# oresat-camera-card-v0.net
KiCad netlist of a schematic drawn in EAGLE
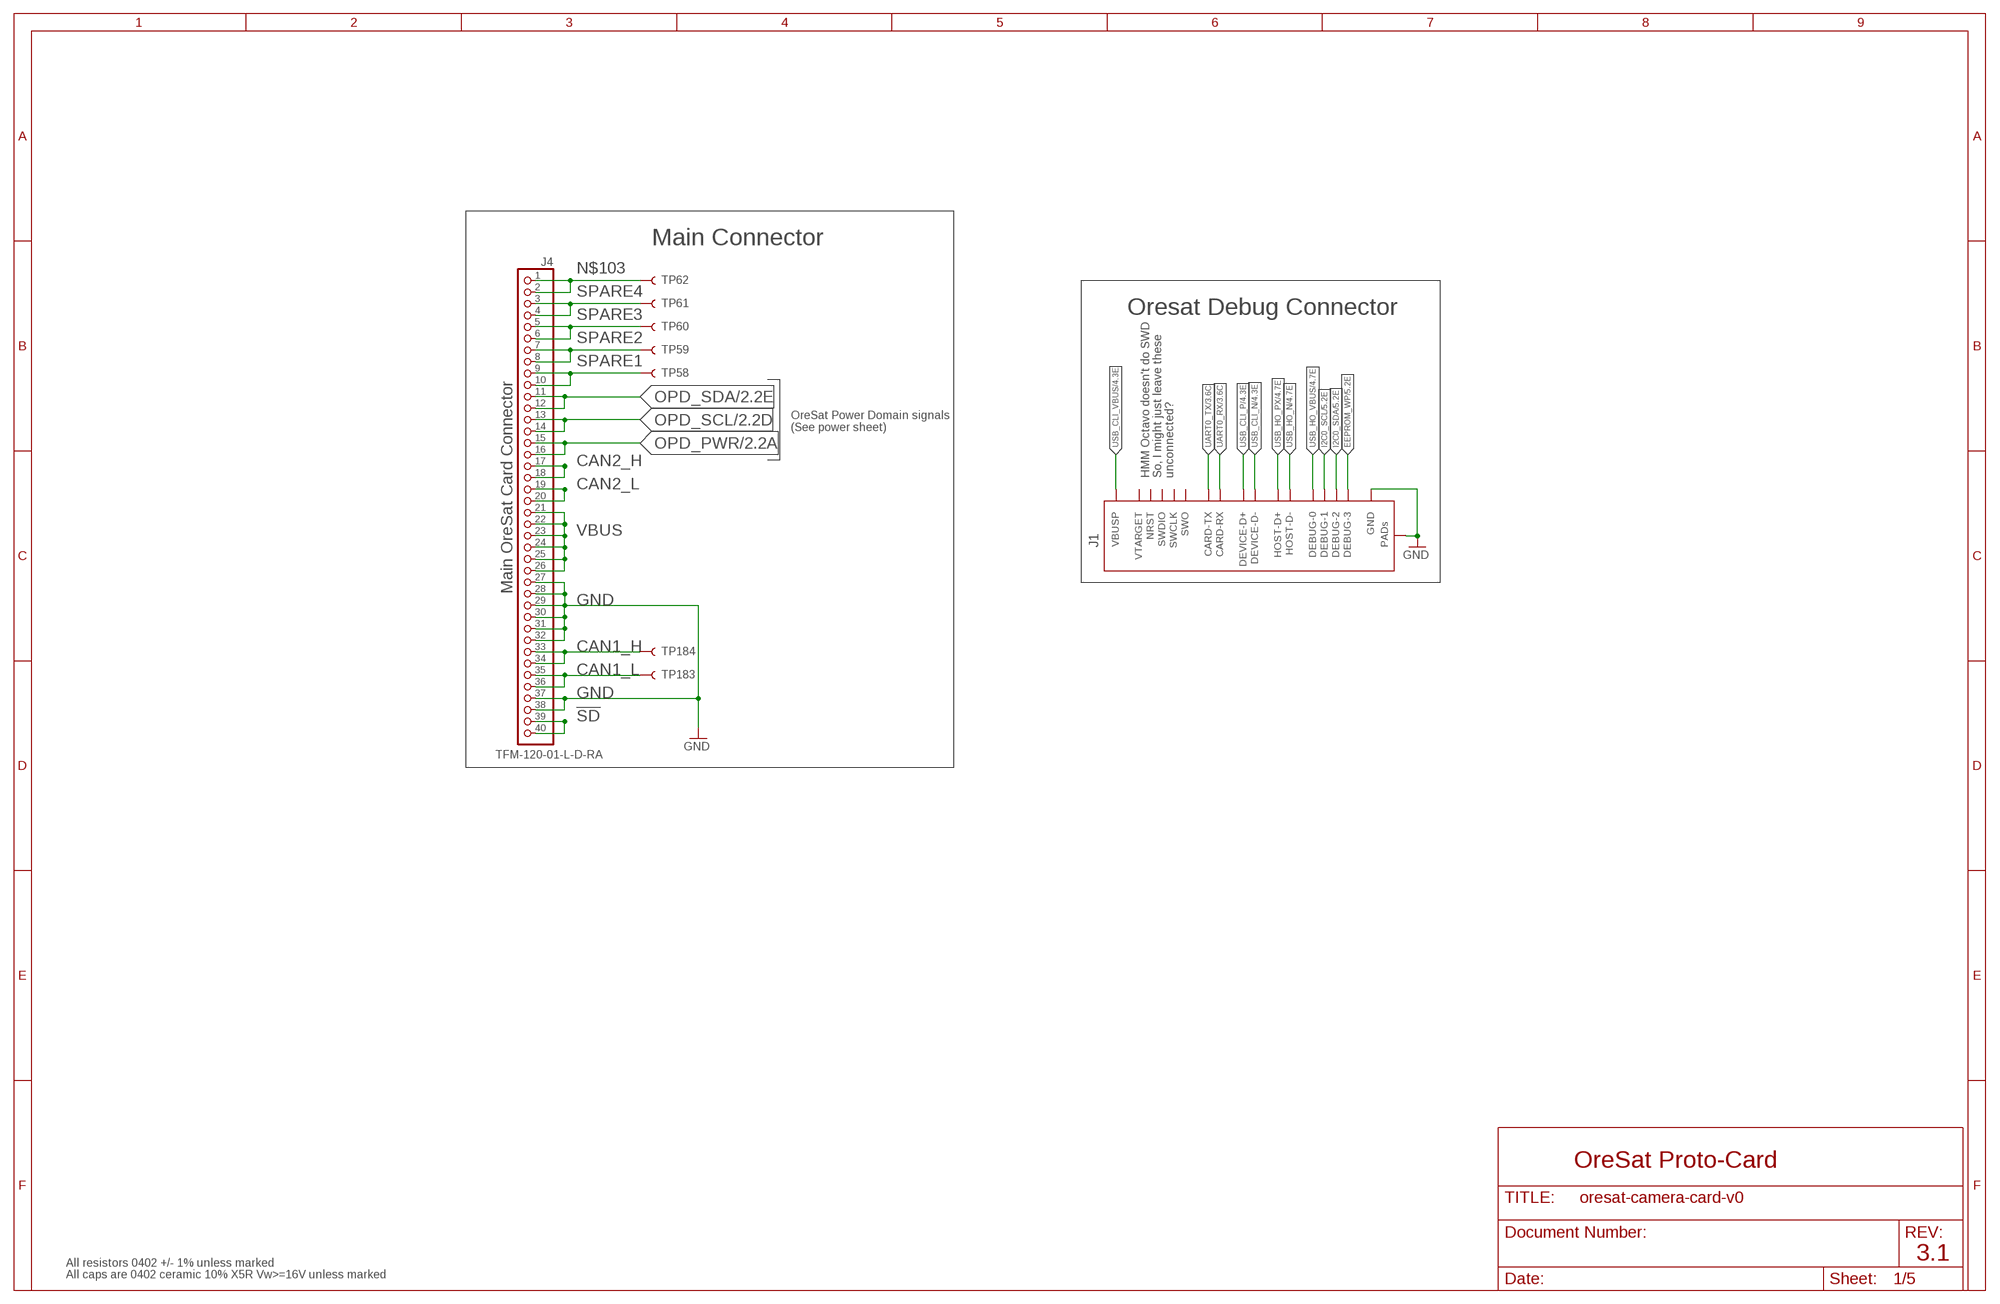
[diagram p0: schematic, sheet 1]
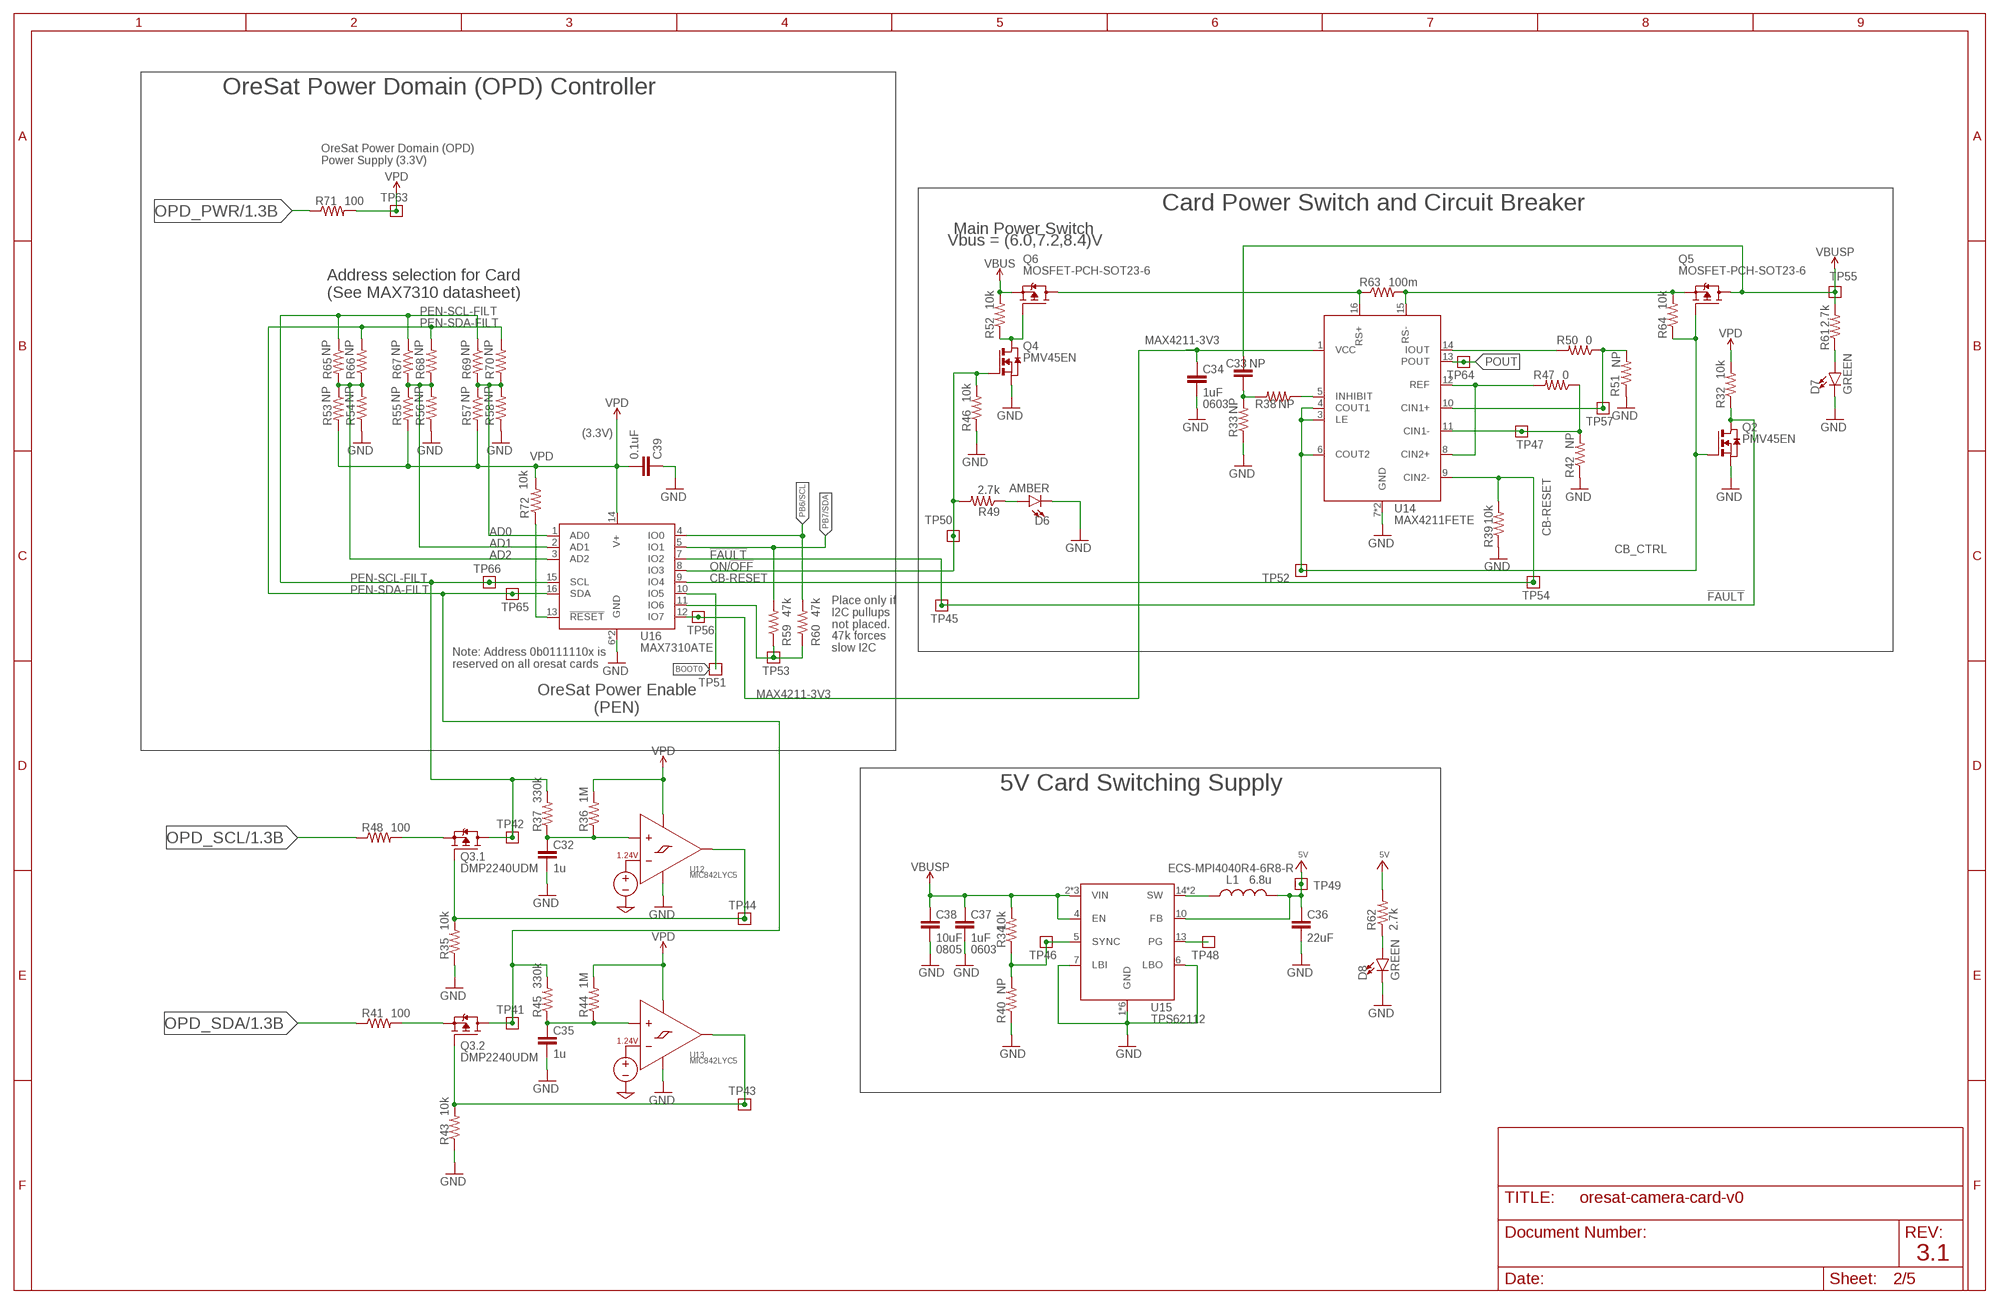
[diagram p1: schematic, sheet 2]
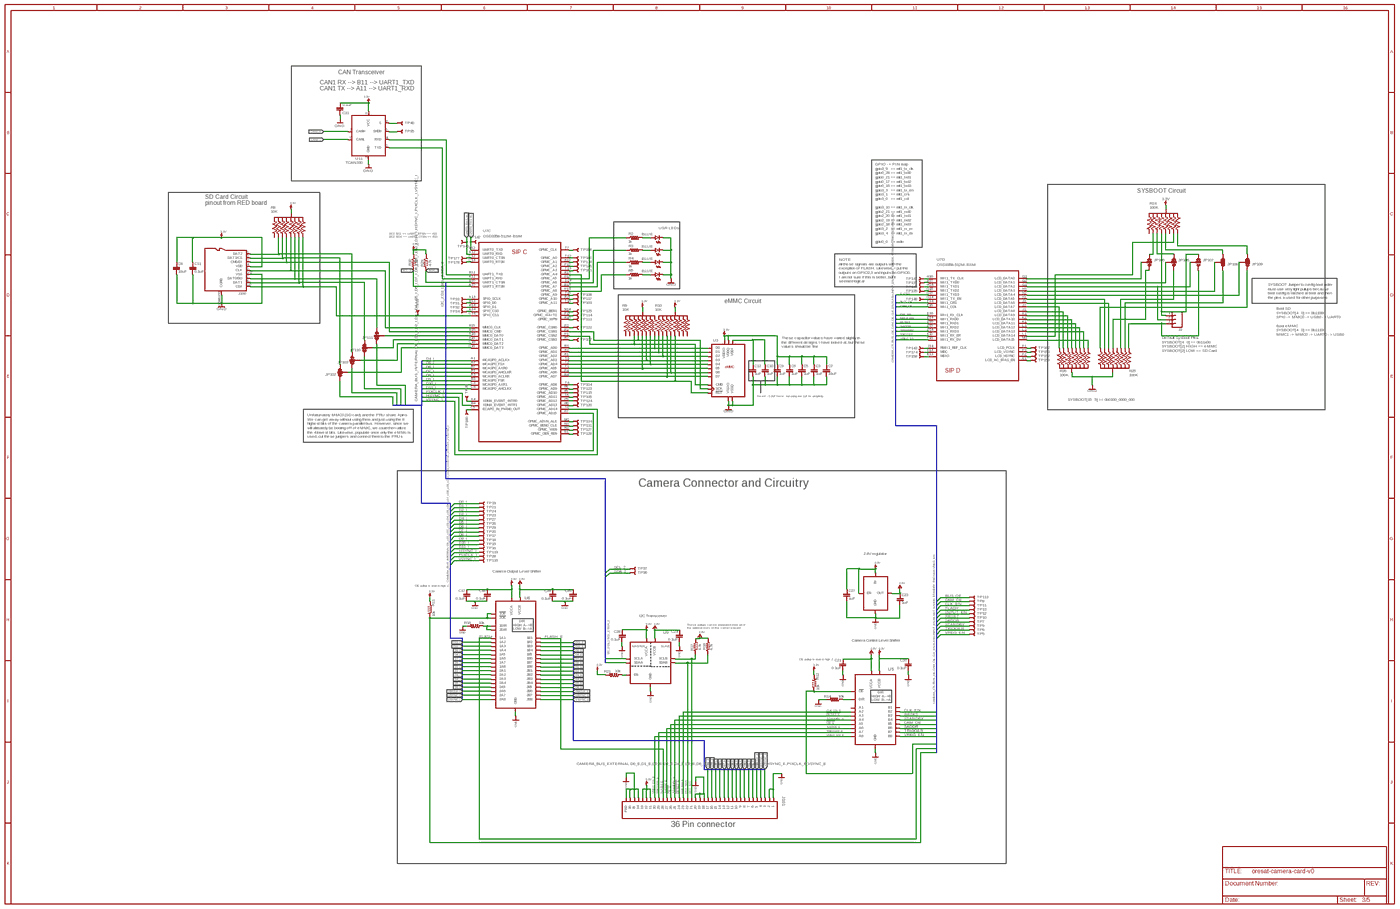
[diagram p2: schematic, sheet 3, overview]
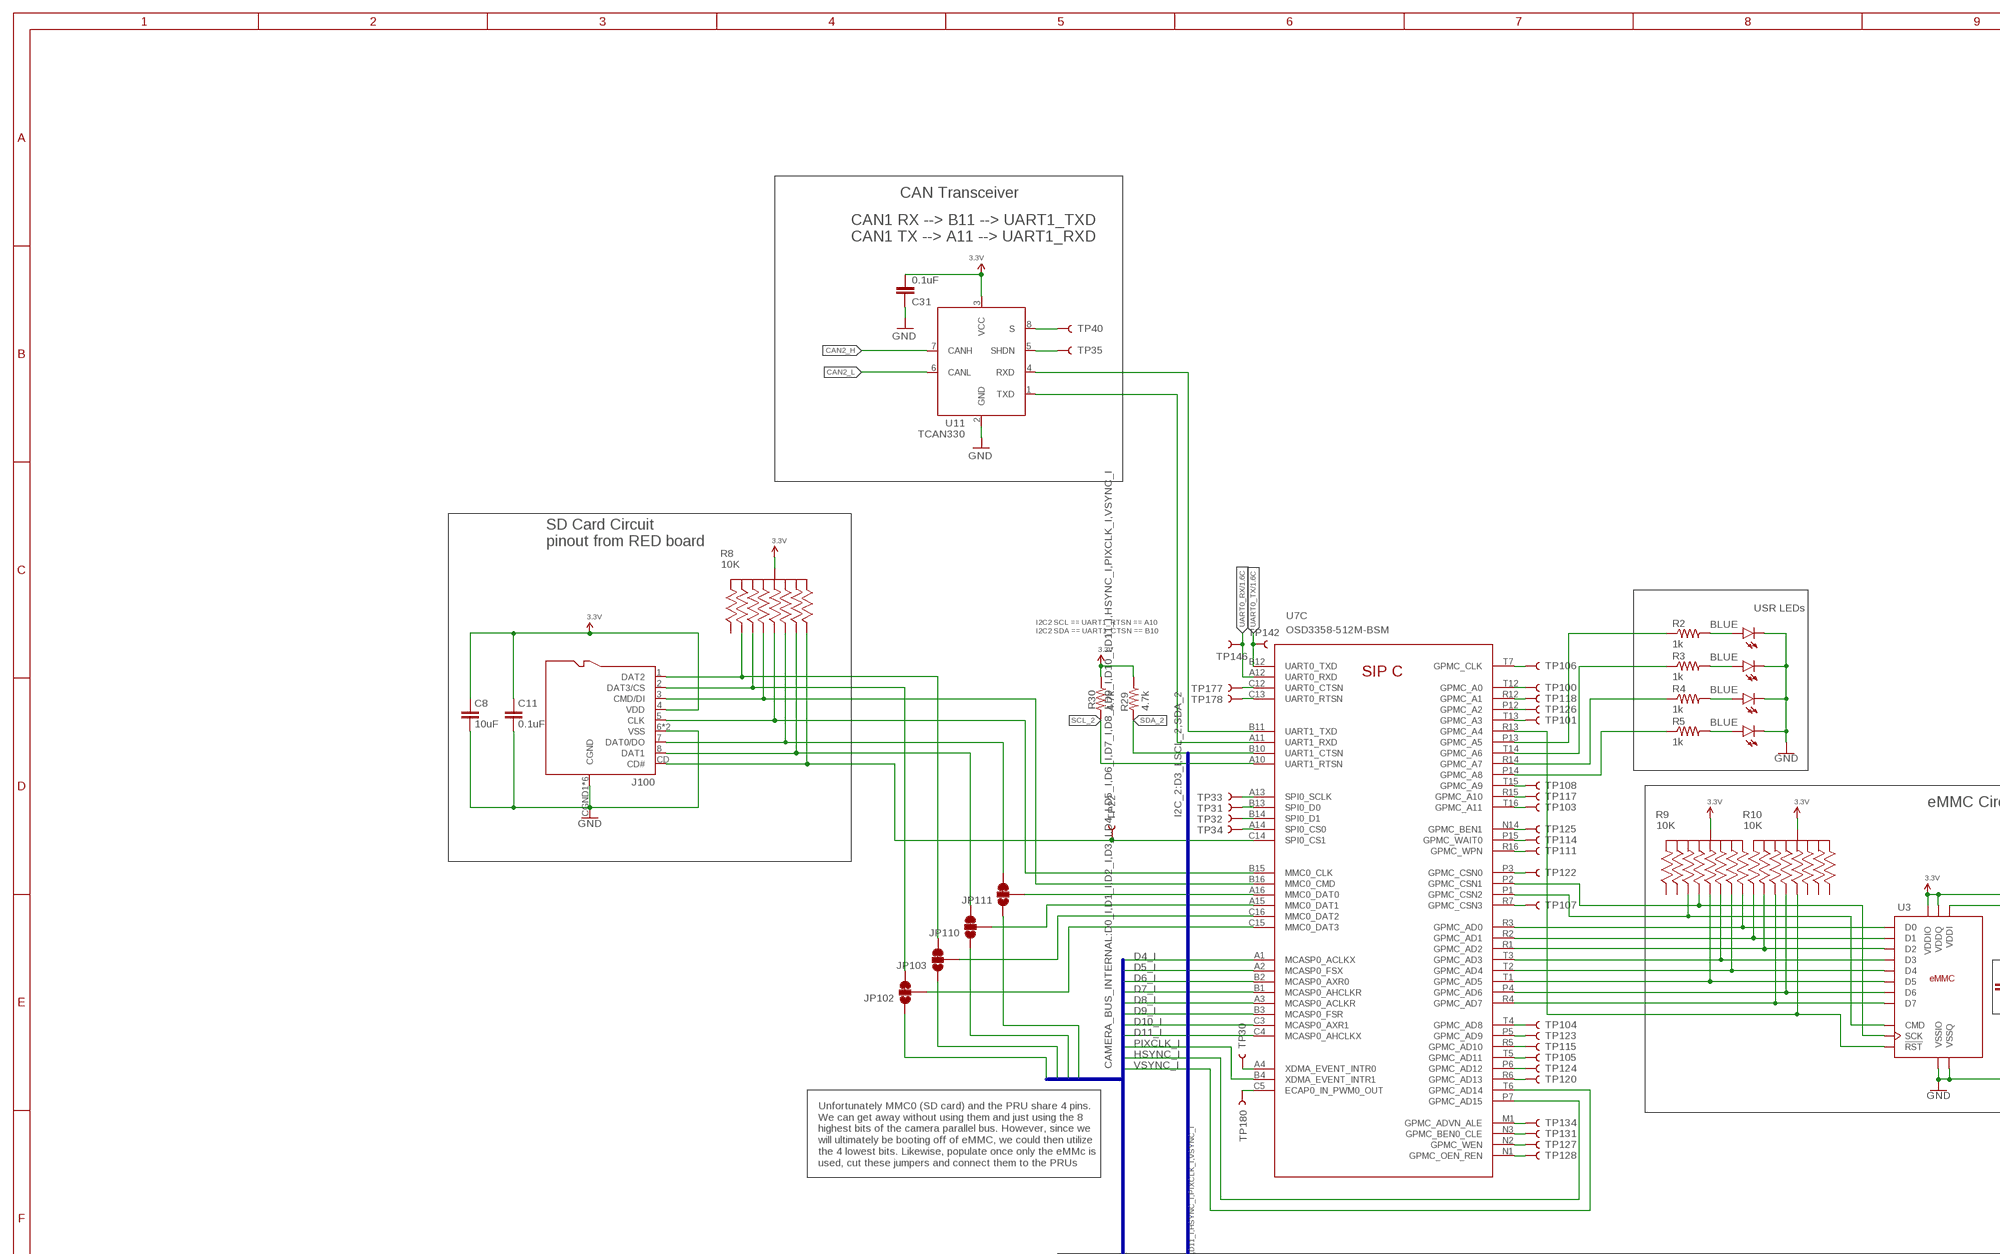
[diagram p3: schematic, sheet 3, part 1 of 4]
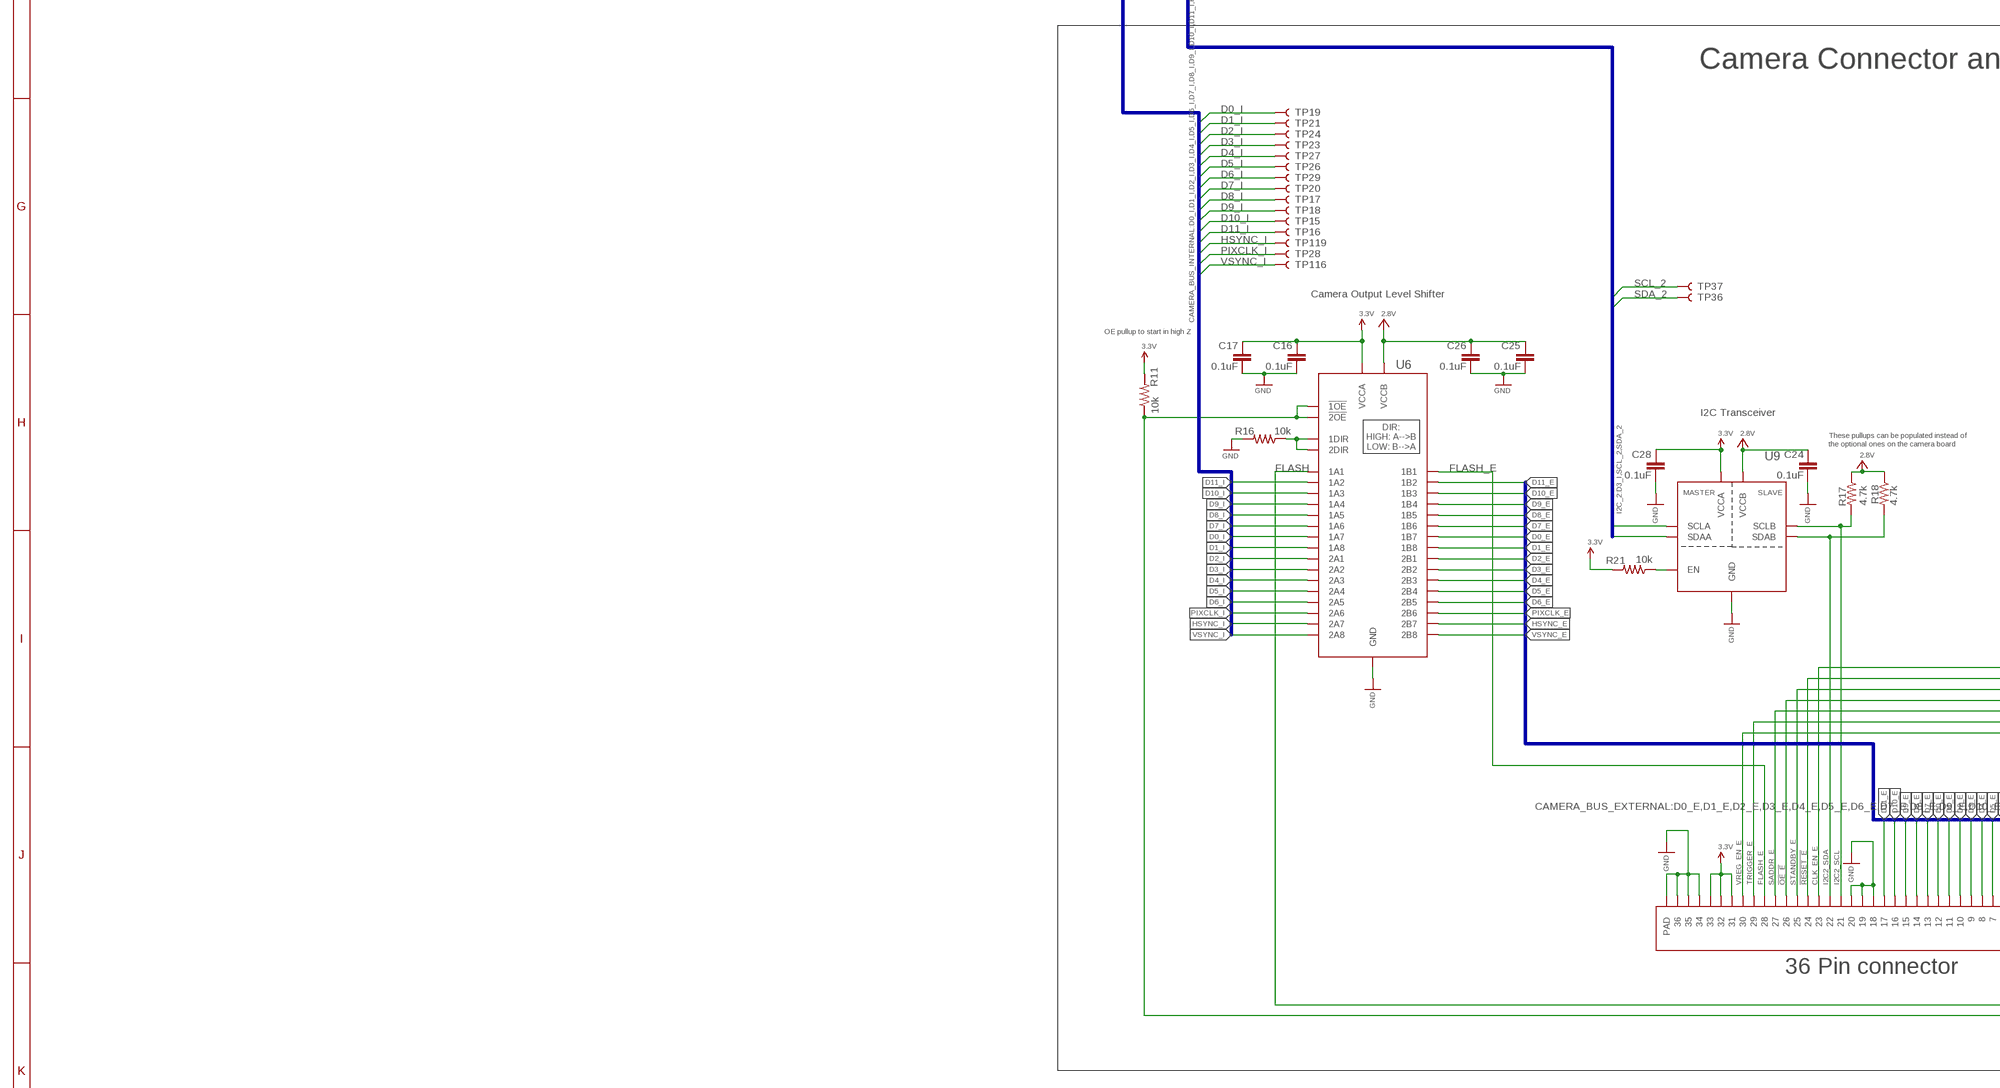
[diagram p4: schematic, sheet 3, part 2 of 4]
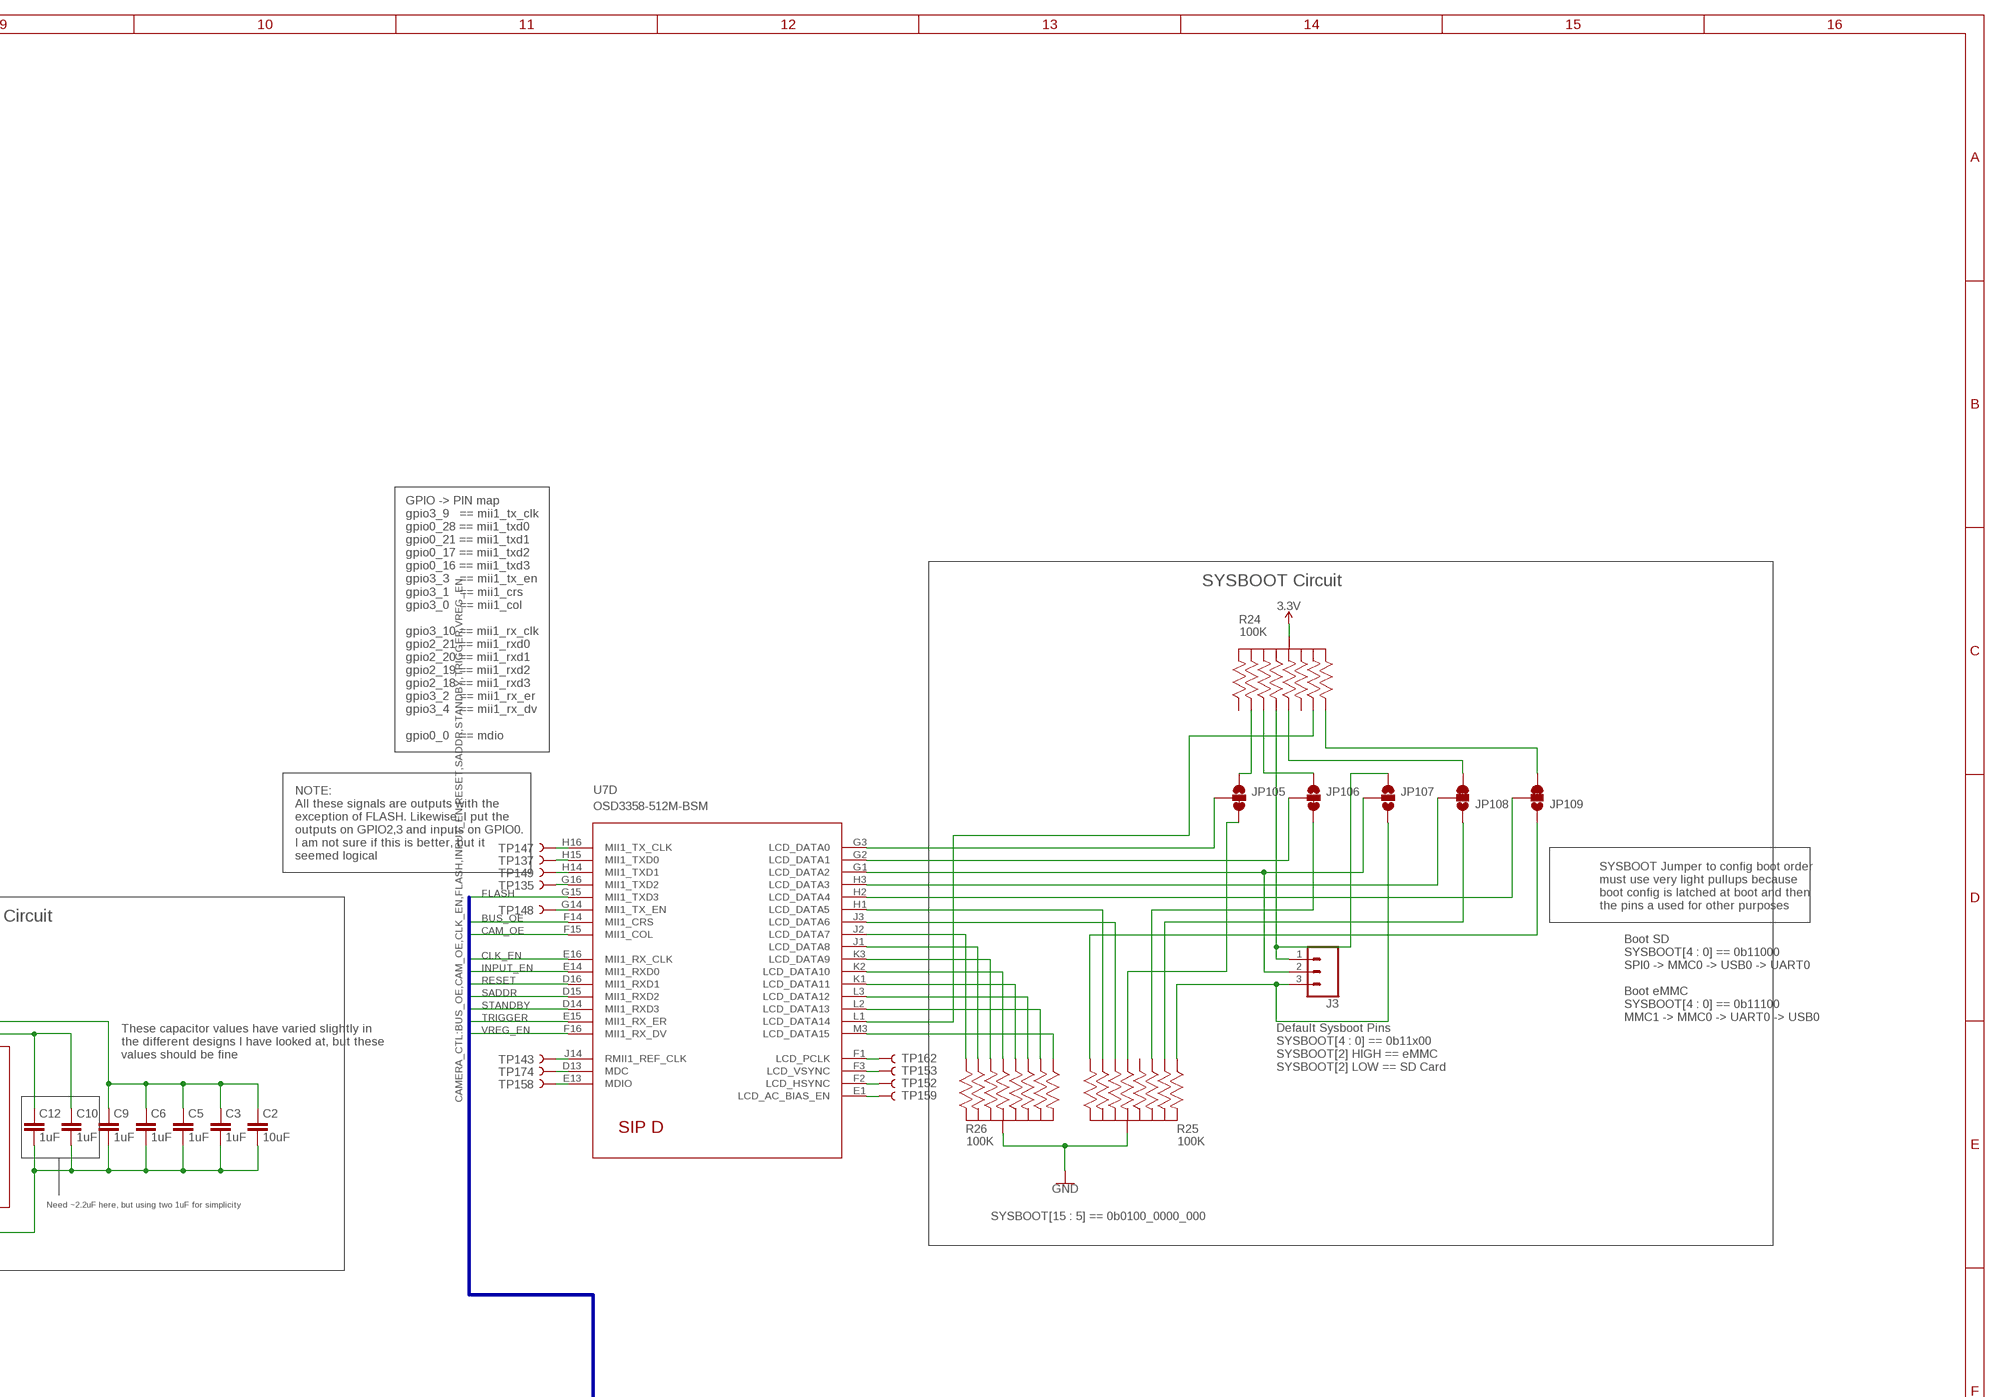
[diagram p5: schematic, sheet 3, part 3 of 4]
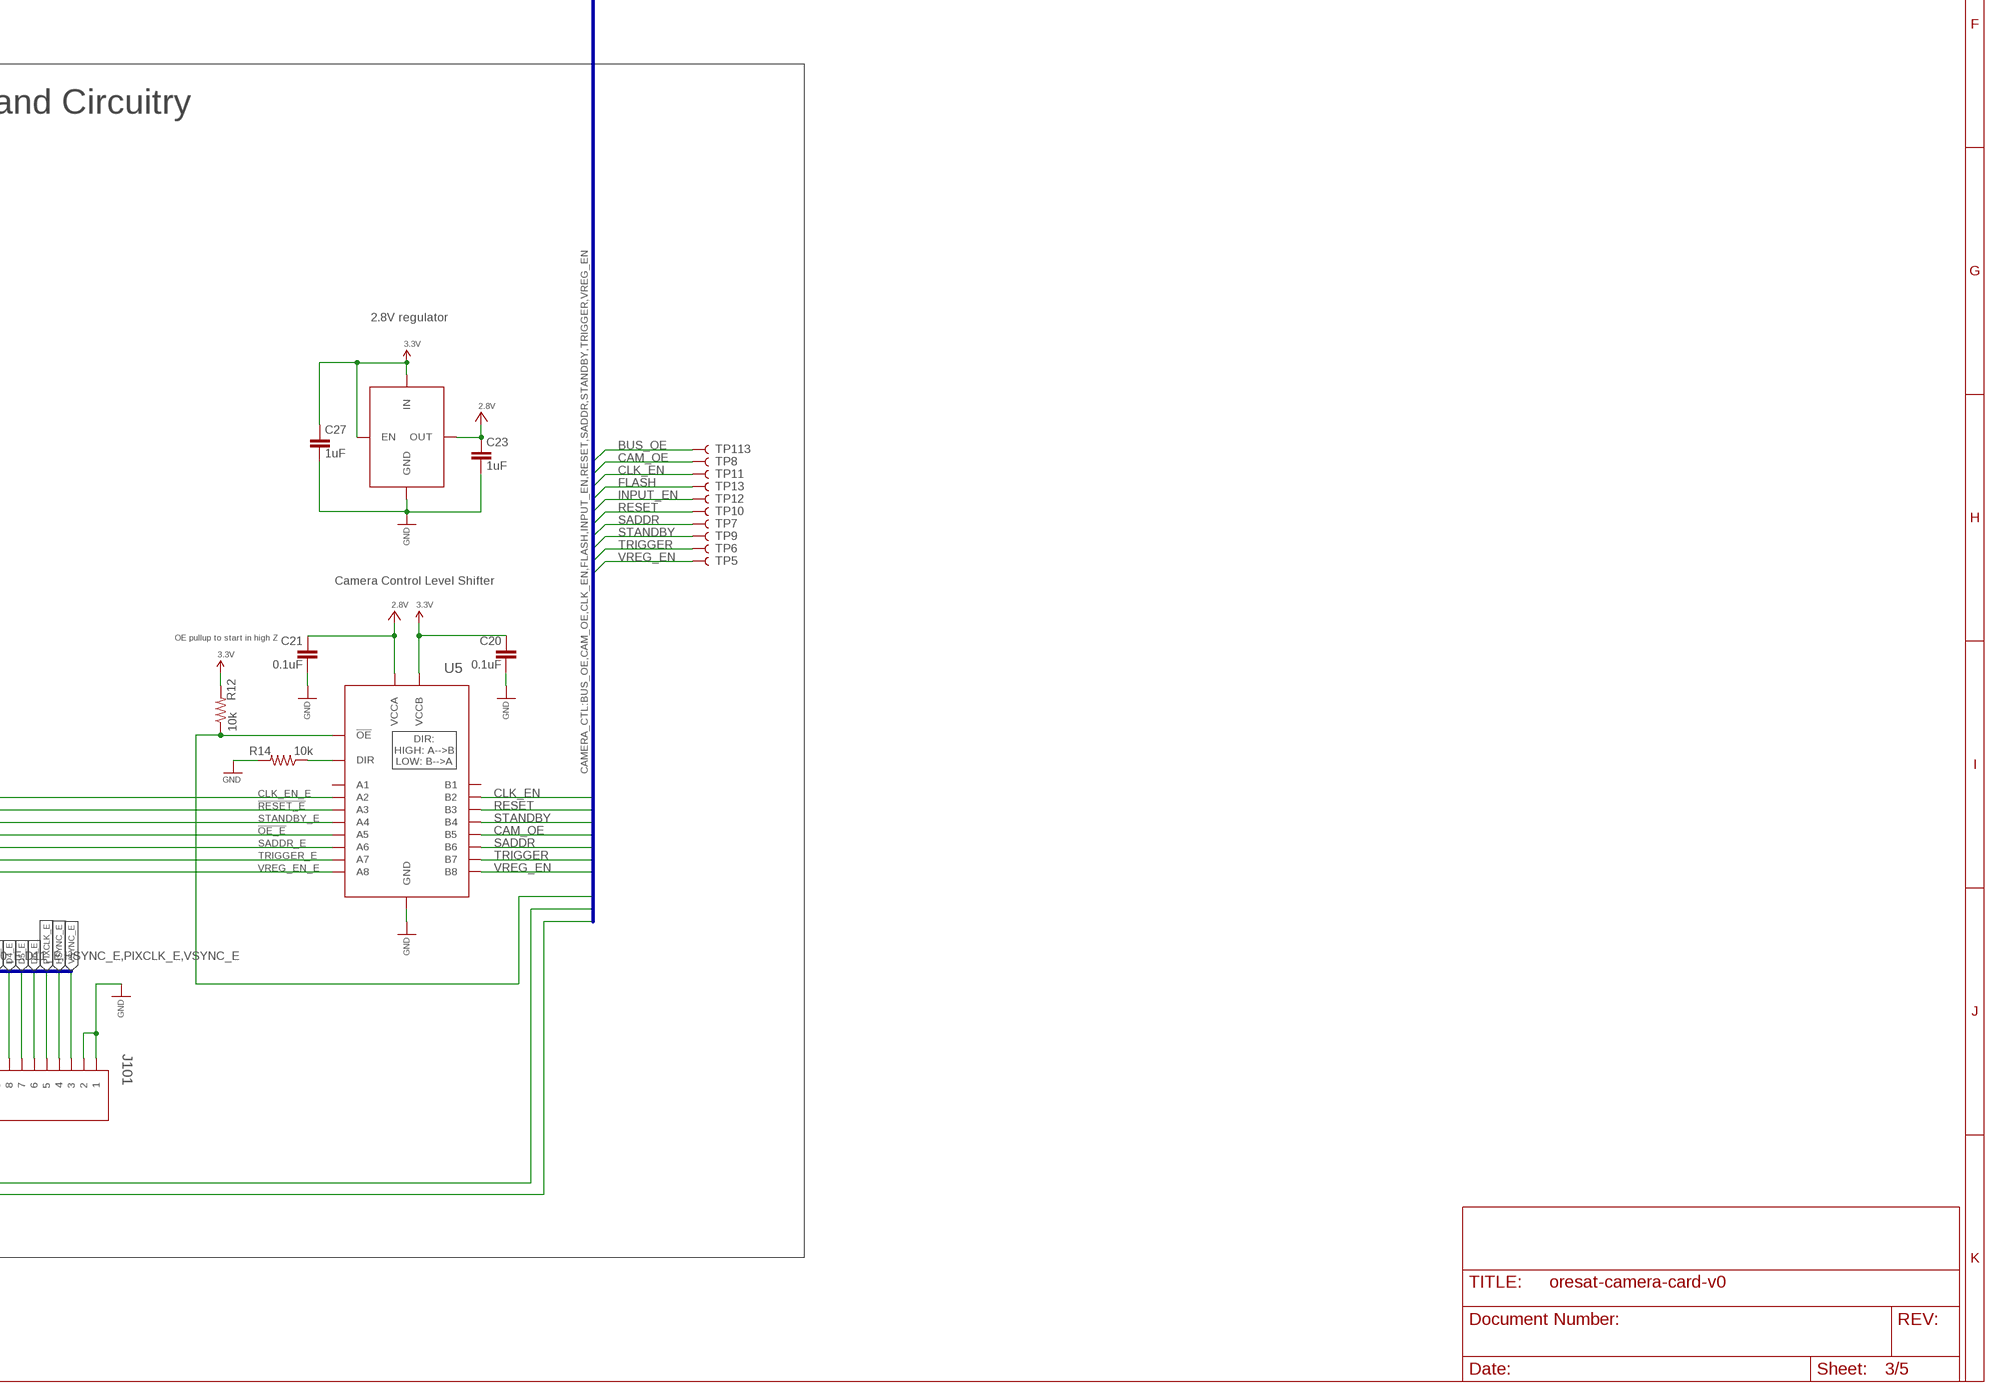
[diagram p6: schematic, sheet 3, part 4 of 4]
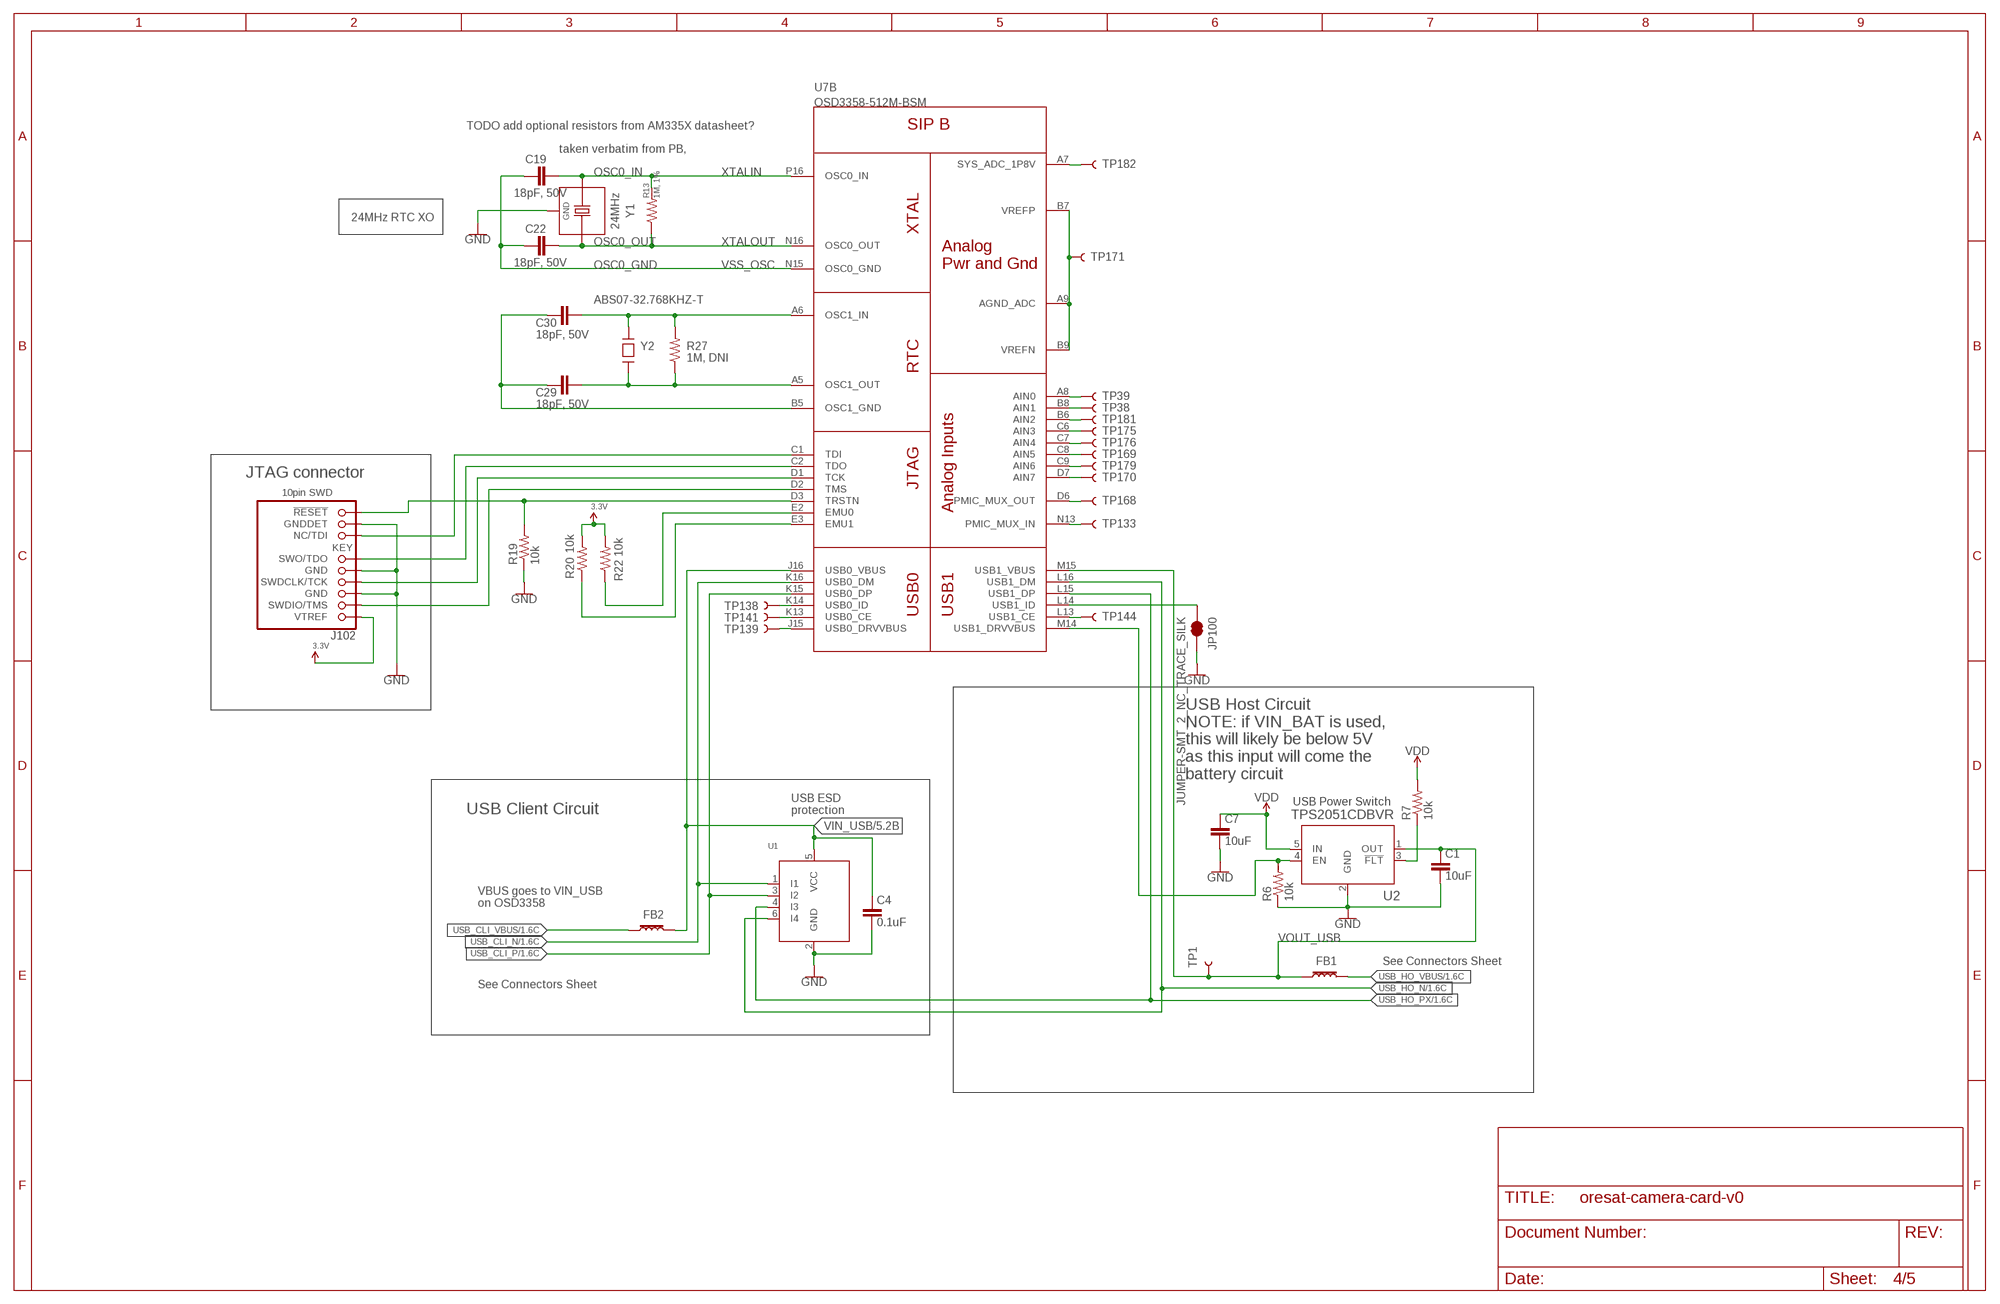
[diagram p7: schematic, sheet 4]
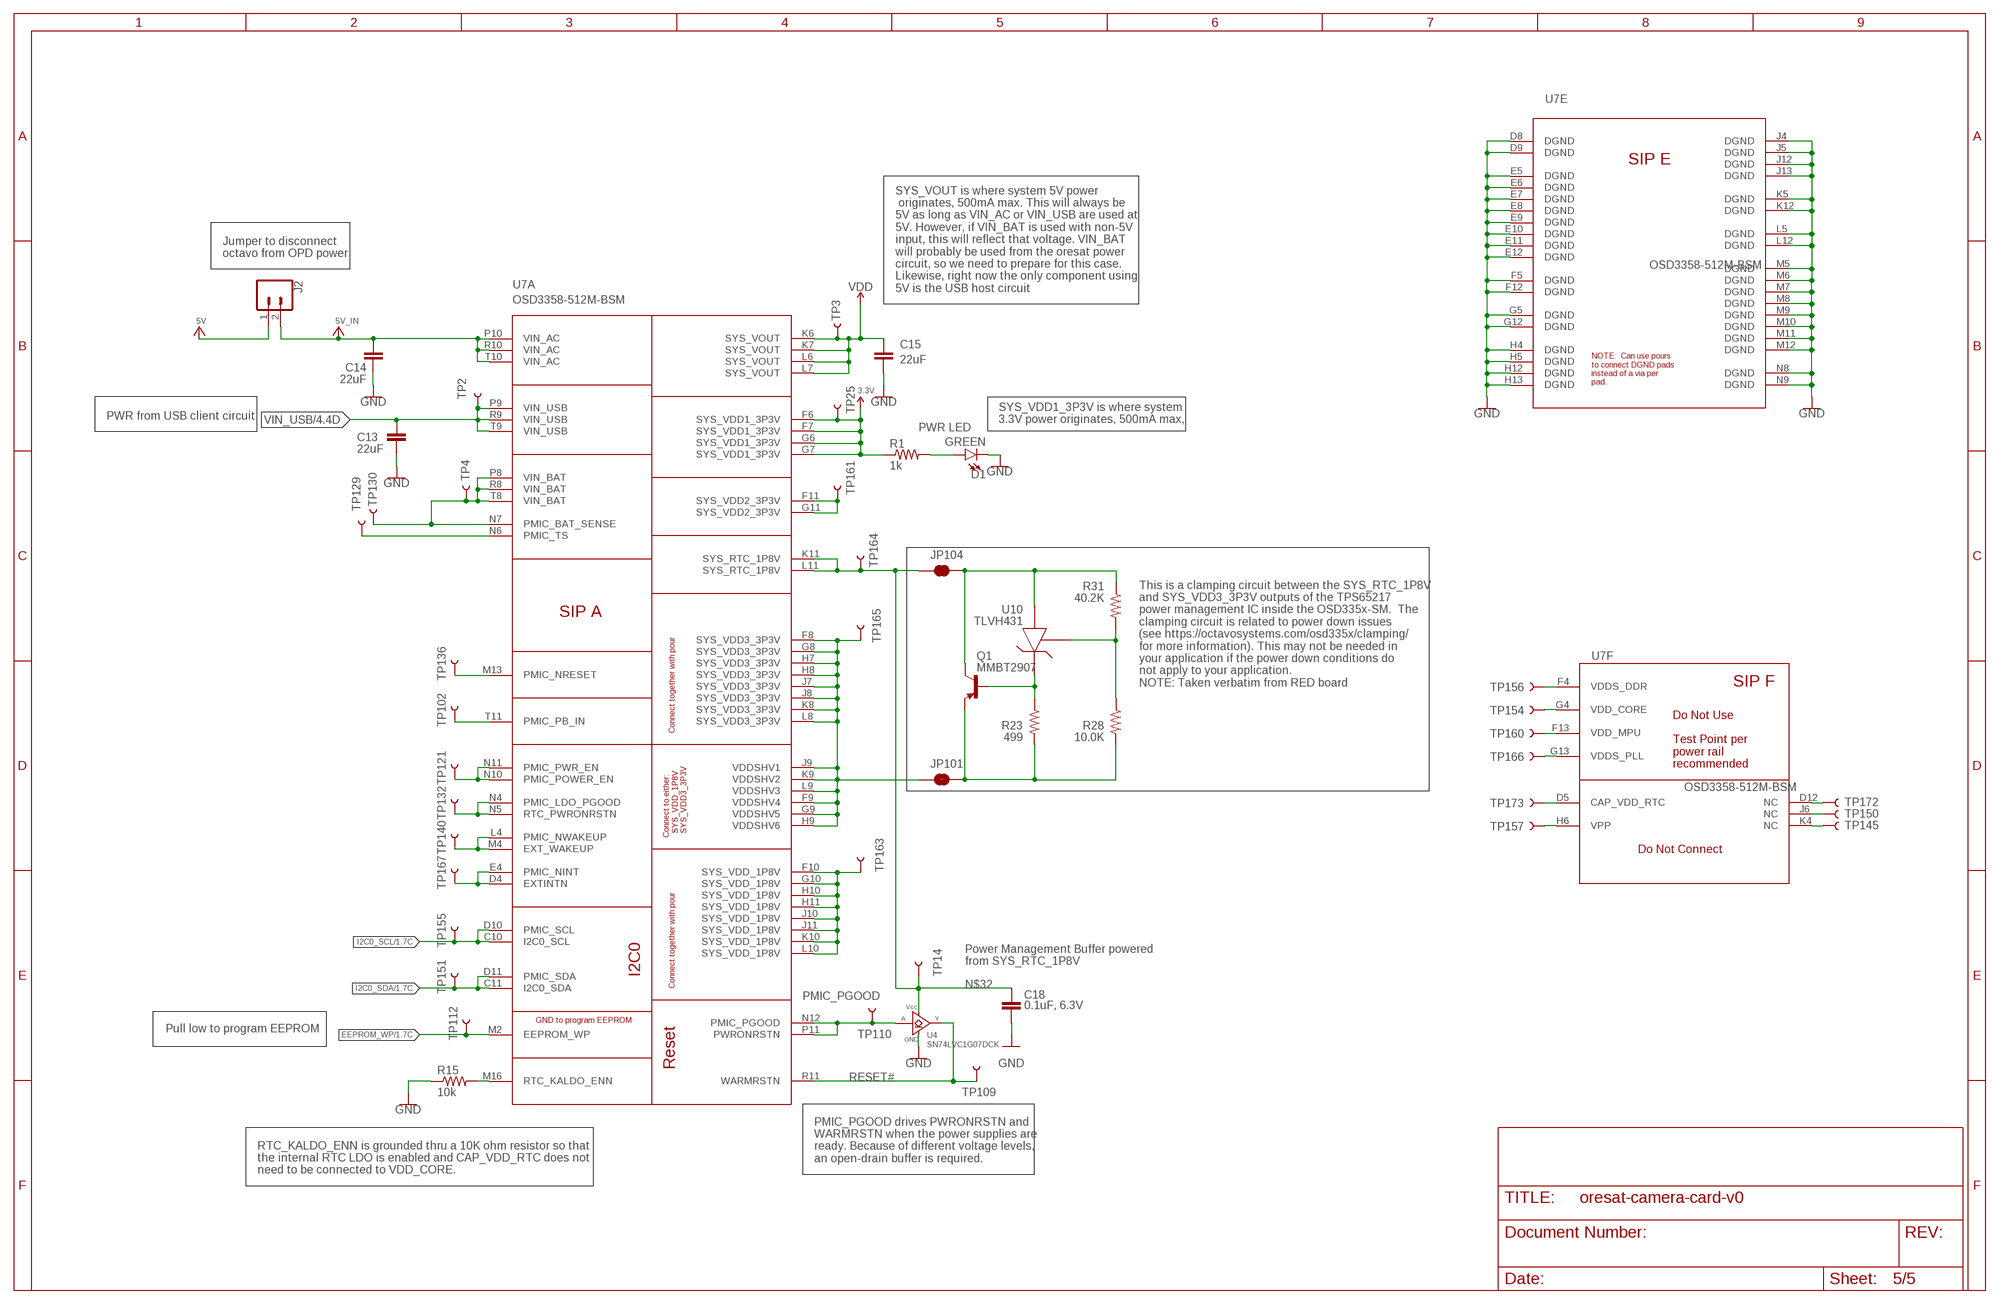
[diagram p8: schematic, sheet 5]

(export (version "E")
  (design (tool "Eeschema 10.0.6"))
  (components
    (comp (ref "C2")
      (value "10uF")
      (footprint "eagle-import:.0805-B")
      (libsource (lib "eagle-import") (part "C-EU0805-B"))
    )
    (comp (ref "C3")
      (value "1uF")
      (footprint "eagle-import:.0603-A")
      (libsource (lib "eagle-import") (part "C-EU0603-A"))
    )
    (comp (ref "C5")
      (value "1uF")
      (footprint "eagle-import:.0603-A")
      (libsource (lib "eagle-import") (part "C-EU0603-A"))
    )
    (comp (ref "C6")
      (value "1uF")
      (footprint "eagle-import:.0603-A")
      (libsource (lib "eagle-import") (part "C-EU0603-A"))
    )
    (comp (ref "C8")
      (value "10uF")
      (footprint "eagle-import:.0805-B")
      (libsource (lib "eagle-import") (part "C-EU0805-B"))
    )
    (comp (ref "C9")
      (value "1uF")
      (footprint "eagle-import:.0603-A")
      (libsource (lib "eagle-import") (part "C-EU0603-A"))
    )
    (comp (ref "C10")
      (value "1uF")
      (footprint "eagle-import:.0603-A")
      (libsource (lib "eagle-import") (part "C-EU0603-A"))
    )
    (comp (ref "C11")
      (value "0.1uF")
      (footprint "eagle-import:.0603-A")
      (libsource (lib "eagle-import") (part "C-EU0603-A"))
    )
    (comp (ref "C12")
      (value "1uF")
      (footprint "eagle-import:.0603-A")
      (libsource (lib "eagle-import") (part "C-EU0603-A"))
    )
    (comp (ref "C16")
      (value "0.1uF")
      (footprint "eagle-import:.0603-A")
      (libsource (lib "eagle-import") (part "C-EU0603-A"))
    )
    (comp (ref "C17")
      (value "0.1uF")
      (footprint "eagle-import:.0603-A")
      (libsource (lib "eagle-import") (part "C-EU0603-A"))
    )
    (comp (ref "C20")
      (value "0.1uF")
      (footprint "eagle-import:.0603-A")
      (libsource (lib "eagle-import") (part "C-EU0603-A"))
    )
    (comp (ref "C21")
      (value "0.1uF")
      (footprint "eagle-import:.0603-A")
      (libsource (lib "eagle-import") (part "C-EU0603-A"))
    )
    (comp (ref "C23")
      (value "1uF")
      (footprint "eagle-import:.0603-A")
      (libsource (lib "eagle-import") (part "C-EU0603-A"))
    )
    (comp (ref "C24")
      (value "0.1uF")
      (footprint "eagle-import:.0603-A")
      (libsource (lib "eagle-import") (part "C-EU0603-A"))
    )
    (comp (ref "C25")
      (value "0.1uF")
      (footprint "eagle-import:.0603-A")
      (libsource (lib "eagle-import") (part "C-EU0603-A"))
    )
    (comp (ref "C26")
      (value "0.1uF")
      (footprint "eagle-import:.0603-A")
      (libsource (lib "eagle-import") (part "C-EU0603-A"))
    )
    (comp (ref "C27")
      (value "1uF")
      (footprint "eagle-import:.0603-A")
      (libsource (lib "eagle-import") (part "C-EU0603-A"))
    )
    (comp (ref "C28")
      (value "0.1uF")
      (footprint "eagle-import:.0603-A")
      (libsource (lib "eagle-import") (part "C-EU0603-A"))
    )
    (comp (ref "C31")
      (value "0.1uF")
      (footprint "eagle-import:.0603-A")
      (fields (field (name "MFR") "Samsung") (field (name "MPN") "CL05B104KO5NNNC"))
      (libsource (lib "eagle-import") (part "C-EU0603-A"))
    )
    (comp (ref "D2")
      (value "BLUE")
      (footprint "eagle-import:LED-0603")
      (libsource (lib "eagle-import") (part "LED-BLUE0603"))
    )
    (comp (ref "D3")
      (value "BLUE")
      (footprint "eagle-import:LED-0603")
      (libsource (lib "eagle-import") (part "LED-BLUE0603"))
    )
    (comp (ref "D4")
      (value "BLUE")
      (footprint "eagle-import:LED-0603")
      (libsource (lib "eagle-import") (part "LED-BLUE0603"))
    )
    (comp (ref "D5")
      (value "BLUE")
      (footprint "eagle-import:LED-0603")
      (libsource (lib "eagle-import") (part "LED-BLUE0603"))
    )
    (comp (ref "J3")
      (value "CONN_03LONGPADS")
      (footprint "eagle-import:1X03_LONGPADS")
      (libsource (lib "eagle-import") (part "CONN_03LONGPADS"))
    )
    (comp (ref "J100")
      (value "DM3BT-DSF-PEJS")
      (footprint "eagle-import:DM3BT-DSF-PEJS")
      (libsource (lib "eagle-import") (part "DM3BT-DSF-PEJS"))
    )
    (comp (ref "J101")
      (value "3-1734592-64-1734592-0")
      (footprint "eagle-import:TE_3-1734592-6")
      (libsource (lib "eagle-import") (part "3-1734592-64-1734592-0"))
    )
    (comp (ref "JP102")
      (value "JUMPER-SMT_3_1-NC_TRACE_SILK")
      (footprint "eagle-import:SMT-JUMPER_3_1-NC_TRACE_SILK")
      (libsource (lib "eagle-import") (part "JUMPER-SMT_3_1-NC_TRACE_SILK"))
    )
    (comp (ref "JP103")
      (value "JUMPER-SMT_3_1-NC_TRACE_SILK")
      (footprint "eagle-import:SMT-JUMPER_3_1-NC_TRACE_SILK")
      (libsource (lib "eagle-import") (part "JUMPER-SMT_3_1-NC_TRACE_SILK"))
    )
    (comp (ref "JP105")
      (value "JUMPER-SMT_3_1-NC_TRACE_SILK")
      (footprint "eagle-import:SMT-JUMPER_3_1-NC_TRACE_SILK")
      (libsource (lib "eagle-import") (part "JUMPER-SMT_3_1-NC_TRACE_SILK"))
    )
    (comp (ref "JP106")
      (value "JUMPER-SMT_3_1-NC_TRACE_SILK")
      (footprint "eagle-import:SMT-JUMPER_3_1-NC_TRACE_SILK")
      (libsource (lib "eagle-import") (part "JUMPER-SMT_3_1-NC_TRACE_SILK"))
    )
    (comp (ref "JP107")
      (value "JUMPER-SMT_3_NO_NO_SILK")
      (footprint "eagle-import:SMT-JUMPER_3_0-NO_TRACE_NO-SILK")
      (libsource (lib "eagle-import") (part "JUMPER-SMT_3_NO_NO_SILK"))
    )
    (comp (ref "JP108")
      (value "JUMPER-SMT_3_1-NC_TRACE_SILK")
      (footprint "eagle-import:SMT-JUMPER_3_1-NC_TRACE_SILK")
      (libsource (lib "eagle-import") (part "JUMPER-SMT_3_1-NC_TRACE_SILK"))
    )
    (comp (ref "JP109")
      (value "JUMPER-SMT_3_1-NC_TRACE_SILK")
      (footprint "eagle-import:SMT-JUMPER_3_1-NC_TRACE_SILK")
      (libsource (lib "eagle-import") (part "JUMPER-SMT_3_1-NC_TRACE_SILK"))
    )
    (comp (ref "JP110")
      (value "JUMPER-SMT_3_1-NC_TRACE_SILK")
      (footprint "eagle-import:SMT-JUMPER_3_1-NC_TRACE_SILK")
      (libsource (lib "eagle-import") (part "JUMPER-SMT_3_1-NC_TRACE_SILK"))
    )
    (comp (ref "JP111")
      (value "JUMPER-SMT_3_1-NC_TRACE_SILK")
      (footprint "eagle-import:SMT-JUMPER_3_1-NC_TRACE_SILK")
      (libsource (lib "eagle-import") (part "JUMPER-SMT_3_1-NC_TRACE_SILK"))
    )
    (comp (ref "R2")
      (value "1k")
      (footprint "eagle-import:.0603-A")
      (libsource (lib "eagle-import") (part "R-US_0603-A"))
    )
    (comp (ref "R3")
      (value "1k")
      (footprint "eagle-import:.0603-A")
      (libsource (lib "eagle-import") (part "R-US_0603-A"))
    )
    (comp (ref "R4")
      (value "1k")
      (footprint "eagle-import:.0603-A")
      (libsource (lib "eagle-import") (part "R-US_0603-A"))
    )
    (comp (ref "R5")
      (value "1k")
      (footprint "eagle-import:.0603-A")
      (libsource (lib "eagle-import") (part "R-US_0603-A"))
    )
    (comp (ref "R8")
      (value "10K")
      (footprint "eagle-import:ARRAY_EXBA-M")
      (fields
        (field (name "MANUFACTURER") "Panasonic Electronic Components")
        (field (name "MANUFACTURER_PART_NUMBER") "EXB-A10P103J")
      )
      (libsource (lib "eagle-import") (part "EXB-A10P391JC_ARRAY_EXBA-M"))
    )
    (comp (ref "R9")
      (value "10K")
      (footprint "eagle-import:ARRAY_EXBA-M")
      (fields
        (field (name "MANUFACTURER") "Panasonic Electronic Components")
        (field (name "MANUFACTURER_PART_NUMBER") "EXB-A10P103J")
      )
      (libsource (lib "eagle-import") (part "EXB-A10P391JC_ARRAY_EXBA-M"))
    )
    (comp (ref "R10")
      (value "10K")
      (footprint "eagle-import:ARRAY_EXBA-M")
      (fields
        (field (name "MANUFACTURER") "Panasonic Electronic Components")
        (field (name "MANUFACTURER_PART_NUMBER") "EXB-A10P103J")
      )
      (libsource (lib "eagle-import") (part "EXB-A10P391JC_ARRAY_EXBA-M"))
    )
    (comp (ref "R11")
      (value "10k")
      (footprint "eagle-import:.0603-A")
      (libsource (lib "eagle-import") (part "R-US_0603-A"))
    )
    (comp (ref "R12")
      (value "10k")
      (footprint "eagle-import:.0603-A")
      (libsource (lib "eagle-import") (part "R-US_0603-A"))
    )
    (comp (ref "R14")
      (value "10k")
      (footprint "eagle-import:.0603-A")
      (libsource (lib "eagle-import") (part "R-US_0603-A"))
    )
    (comp (ref "R16")
      (value "10k")
      (footprint "eagle-import:.0603-A")
      (libsource (lib "eagle-import") (part "R-US_0603-A"))
    )
    (comp (ref "R17")
      (value "4.7k")
      (footprint "eagle-import:.0603-A")
      (libsource (lib "eagle-import") (part "R-US_0603-A"))
    )
    (comp (ref "R18")
      (value "4.7k")
      (footprint "eagle-import:.0603-A")
      (libsource (lib "eagle-import") (part "R-US_0603-A"))
    )
    (comp (ref "R21")
      (value "10k")
      (footprint "eagle-import:.0603-A")
      (libsource (lib "eagle-import") (part "R-US_0603-A"))
    )
    (comp (ref "R24")
      (value "100K")
      (footprint "eagle-import:ARRAY_EXBA-M")
      (fields
        (field (name "MANUFACTURER") "Panasonic Electronic Components")
        (field (name "MANUFACTURER_PART_NUMBER") "EXB-A10P103J")
      )
      (libsource (lib "eagle-import") (part "EXB-A10P391JC_ARRAY_EXBA-M"))
    )
    (comp (ref "R25")
      (value "100K")
      (footprint "eagle-import:ARRAY_EXBA-M")
      (fields
        (field (name "MANUFACTURER") "Panasonic Electronic Components")
        (field (name "MANUFACTURER_PART_NUMBER") "EXB-A10P103J")
      )
      (libsource (lib "eagle-import") (part "EXB-A10P391JC_ARRAY_EXBA-M"))
    )
    (comp (ref "R26")
      (value "100K")
      (footprint "eagle-import:ARRAY_EXBA-M")
      (fields
        (field (name "MANUFACTURER") "Panasonic Electronic Components")
        (field (name "MANUFACTURER_PART_NUMBER") "EXB-A10P103J")
      )
      (libsource (lib "eagle-import") (part "EXB-A10P391JC_ARRAY_EXBA-M"))
    )
    (comp (ref "R29")
      (value "4.7k")
      (footprint "eagle-import:.0603-A")
      (libsource (lib "eagle-import") (part "R-US_0603-A"))
    )
    (comp (ref "R30")
      (value "4.7k")
      (footprint "eagle-import:.0603-A")
      (libsource (lib "eagle-import") (part "R-US_0603-A"))
    )
    (comp (ref "TP5")
      (value "TEST-POINT3X4")
      (footprint "eagle-import:PAD.03X.04")
      (libsource (lib "eagle-import") (part "TEST-POINT3X4"))
    )
    (comp (ref "TP6")
      (value "TEST-POINT3X4")
      (footprint "eagle-import:PAD.03X.04")
      (libsource (lib "eagle-import") (part "TEST-POINT3X4"))
    )
    (comp (ref "TP7")
      (value "TEST-POINT3X4")
      (footprint "eagle-import:PAD.03X.04")
      (libsource (lib "eagle-import") (part "TEST-POINT3X4"))
    )
    (comp (ref "TP8")
      (value "TEST-POINT3X4")
      (footprint "eagle-import:PAD.03X.04")
      (libsource (lib "eagle-import") (part "TEST-POINT3X4"))
    )
    (comp (ref "TP9")
      (value "TEST-POINT3X4")
      (footprint "eagle-import:PAD.03X.04")
      (libsource (lib "eagle-import") (part "TEST-POINT3X4"))
    )
    (comp (ref "TP10")
      (value "TEST-POINT3X4")
      (footprint "eagle-import:PAD.03X.04")
      (libsource (lib "eagle-import") (part "TEST-POINT3X4"))
    )
    (comp (ref "TP11")
      (value "TEST-POINT3X4")
      (footprint "eagle-import:PAD.03X.04")
      (libsource (lib "eagle-import") (part "TEST-POINT3X4"))
    )
    (comp (ref "TP12")
      (value "TEST-POINT3X4")
      (footprint "eagle-import:PAD.03X.04")
      (libsource (lib "eagle-import") (part "TEST-POINT3X4"))
    )
    (comp (ref "TP13")
      (value "TEST-POINT3X4")
      (footprint "eagle-import:PAD.03X.04")
      (libsource (lib "eagle-import") (part "TEST-POINT3X4"))
    )
    (comp (ref "TP15")
      (value "TEST-POINT3X4")
      (footprint "eagle-import:PAD.03X.04")
      (libsource (lib "eagle-import") (part "TEST-POINT3X4"))
    )
    (comp (ref "TP16")
      (value "TEST-POINT3X4")
      (footprint "eagle-import:PAD.03X.04")
      (libsource (lib "eagle-import") (part "TEST-POINT3X4"))
    )
    (comp (ref "TP17")
      (value "TEST-POINT3X4")
      (footprint "eagle-import:PAD.03X.04")
      (libsource (lib "eagle-import") (part "TEST-POINT3X4"))
    )
    (comp (ref "TP18")
      (value "TEST-POINT3X4")
      (footprint "eagle-import:PAD.03X.04")
      (libsource (lib "eagle-import") (part "TEST-POINT3X4"))
    )
    (comp (ref "TP19")
      (value "TEST-POINT3X4")
      (footprint "eagle-import:PAD.03X.04")
      (libsource (lib "eagle-import") (part "TEST-POINT3X4"))
    )
    (comp (ref "TP20")
      (value "TEST-POINT3X4")
      (footprint "eagle-import:PAD.03X.04")
      (libsource (lib "eagle-import") (part "TEST-POINT3X4"))
    )
    (comp (ref "TP21")
      (value "TEST-POINT3X4")
      (footprint "eagle-import:PAD.03X.04")
      (libsource (lib "eagle-import") (part "TEST-POINT3X4"))
    )
    (comp (ref "TP22")
      (value "TEST-POINT3X4")
      (footprint "eagle-import:PAD.03X.04")
      (libsource (lib "eagle-import") (part "TEST-POINT3X4"))
    )
    (comp (ref "TP23")
      (value "TEST-POINT3X4")
      (footprint "eagle-import:PAD.03X.04")
      (libsource (lib "eagle-import") (part "TEST-POINT3X4"))
    )
    (comp (ref "TP24")
      (value "TEST-POINT3X4")
      (footprint "eagle-import:PAD.03X.04")
      (libsource (lib "eagle-import") (part "TEST-POINT3X4"))
    )
    (comp (ref "TP26")
      (value "TEST-POINT3X4")
      (footprint "eagle-import:PAD.03X.04")
      (libsource (lib "eagle-import") (part "TEST-POINT3X4"))
    )
    (comp (ref "TP27")
      (value "TEST-POINT3X4")
      (footprint "eagle-import:PAD.03X.04")
      (libsource (lib "eagle-import") (part "TEST-POINT3X4"))
    )
    (comp (ref "TP28")
      (value "TEST-POINT3X4")
      (footprint "eagle-import:PAD.03X.04")
      (libsource (lib "eagle-import") (part "TEST-POINT3X4"))
    )
    (comp (ref "TP29")
      (value "TEST-POINT3X4")
      (footprint "eagle-import:PAD.03X.04")
      (libsource (lib "eagle-import") (part "TEST-POINT3X4"))
    )
    (comp (ref "TP30")
      (value "TEST-POINT3X4")
      (footprint "eagle-import:PAD.03X.04")
      (libsource (lib "eagle-import") (part "TEST-POINT3X4"))
    )
    (comp (ref "TP31")
      (value "TEST-POINT3X4")
      (footprint "eagle-import:PAD.03X.04")
      (libsource (lib "eagle-import") (part "TEST-POINT3X4"))
    )
    (comp (ref "TP32")
      (value "TEST-POINT3X4")
      (footprint "eagle-import:PAD.03X.04")
      (libsource (lib "eagle-import") (part "TEST-POINT3X4"))
    )
    (comp (ref "TP33")
      (value "TEST-POINT3X4")
      (footprint "eagle-import:PAD.03X.04")
      (libsource (lib "eagle-import") (part "TEST-POINT3X4"))
    )
    (comp (ref "TP34")
      (value "TEST-POINT3X4")
      (footprint "eagle-import:PAD.03X.04")
      (libsource (lib "eagle-import") (part "TEST-POINT3X4"))
    )
    (comp (ref "TP35")
      (value "TEST-POINT3X4")
      (footprint "eagle-import:PAD.03X.04")
      (libsource (lib "eagle-import") (part "TEST-POINT3X4"))
    )
    (comp (ref "TP36")
      (value "TEST-POINT3X4")
      (footprint "eagle-import:PAD.03X.04")
      (libsource (lib "eagle-import") (part "TEST-POINT3X4"))
    )
    (comp (ref "TP37")
      (value "TEST-POINT3X4")
      (footprint "eagle-import:PAD.03X.04")
      (libsource (lib "eagle-import") (part "TEST-POINT3X4"))
    )
    (comp (ref "TP40")
      (value "TEST-POINT3X4")
      (footprint "eagle-import:PAD.03X.04")
      (libsource (lib "eagle-import") (part "TEST-POINT3X4"))
    )
    (comp (ref "TP100")
      (value "TEST-POINT3X4")
      (footprint "eagle-import:PAD.03X.04")
      (libsource (lib "eagle-import") (part "TEST-POINT3X4"))
    )
    (comp (ref "TP101")
      (value "TEST-POINT3X4")
      (footprint "eagle-import:PAD.03X.04")
      (libsource (lib "eagle-import") (part "TEST-POINT3X4"))
    )
    (comp (ref "TP103")
      (value "TEST-POINT3X4")
      (footprint "eagle-import:PAD.03X.04")
      (libsource (lib "eagle-import") (part "TEST-POINT3X4"))
    )
    (comp (ref "TP104")
      (value "TEST-POINT3X4")
      (footprint "eagle-import:PAD.03X.04")
      (libsource (lib "eagle-import") (part "TEST-POINT3X4"))
    )
    (comp (ref "TP105")
      (value "TEST-POINT3X4")
      (footprint "eagle-import:PAD.03X.04")
      (libsource (lib "eagle-import") (part "TEST-POINT3X4"))
    )
    (comp (ref "TP106")
      (value "TEST-POINT3X4")
      (footprint "eagle-import:PAD.03X.04")
      (libsource (lib "eagle-import") (part "TEST-POINT3X4"))
    )
    (comp (ref "TP107")
      (value "TEST-POINT3X4")
      (footprint "eagle-import:PAD.03X.04")
      (libsource (lib "eagle-import") (part "TEST-POINT3X4"))
    )
    (comp (ref "TP108")
      (value "TEST-POINT3X4")
      (footprint "eagle-import:PAD.03X.04")
      (libsource (lib "eagle-import") (part "TEST-POINT3X4"))
    )
    (comp (ref "TP111")
      (value "TEST-POINT3X4")
      (footprint "eagle-import:PAD.03X.04")
      (libsource (lib "eagle-import") (part "TEST-POINT3X4"))
    )
    (comp (ref "TP113")
      (value "TEST-POINT3X4")
      (footprint "eagle-import:PAD.03X.04")
      (libsource (lib "eagle-import") (part "TEST-POINT3X4"))
    )
    (comp (ref "TP114")
      (value "TEST-POINT3X4")
      (footprint "eagle-import:PAD.03X.04")
      (libsource (lib "eagle-import") (part "TEST-POINT3X4"))
    )
    (comp (ref "TP115")
      (value "TEST-POINT3X4")
      (footprint "eagle-import:PAD.03X.04")
      (libsource (lib "eagle-import") (part "TEST-POINT3X4"))
    )
    (comp (ref "TP116")
      (value "TEST-POINT3X4")
      (footprint "eagle-import:PAD.03X.04")
      (libsource (lib "eagle-import") (part "TEST-POINT3X4"))
    )
    (comp (ref "TP117")
      (value "TEST-POINT3X4")
      (footprint "eagle-import:PAD.03X.04")
      (libsource (lib "eagle-import") (part "TEST-POINT3X4"))
    )
    (comp (ref "TP118")
      (value "TEST-POINT3X4")
      (footprint "eagle-import:PAD.03X.04")
      (libsource (lib "eagle-import") (part "TEST-POINT3X4"))
    )
    (comp (ref "TP119")
      (value "TEST-POINT3X4")
      (footprint "eagle-import:PAD.03X.04")
      (libsource (lib "eagle-import") (part "TEST-POINT3X4"))
    )
    (comp (ref "TP120")
      (value "TEST-POINT3X4")
      (footprint "eagle-import:PAD.03X.04")
      (libsource (lib "eagle-import") (part "TEST-POINT3X4"))
    )
    (comp (ref "TP122")
      (value "TEST-POINT3X4")
      (footprint "eagle-import:PAD.03X.04")
      (libsource (lib "eagle-import") (part "TEST-POINT3X4"))
    )
    (comp (ref "TP123")
      (value "TEST-POINT3X4")
      (footprint "eagle-import:PAD.03X.04")
      (libsource (lib "eagle-import") (part "TEST-POINT3X4"))
    )
    (comp (ref "TP124")
      (value "TEST-POINT3X4")
      (footprint "eagle-import:PAD.03X.04")
      (libsource (lib "eagle-import") (part "TEST-POINT3X4"))
    )
    (comp (ref "TP125")
      (value "TEST-POINT3X4")
      (footprint "eagle-import:PAD.03X.04")
      (libsource (lib "eagle-import") (part "TEST-POINT3X4"))
    )
    (comp (ref "TP126")
      (value "TEST-POINT3X4")
      (footprint "eagle-import:PAD.03X.04")
      (libsource (lib "eagle-import") (part "TEST-POINT3X4"))
    )
    (comp (ref "TP127")
      (value "TEST-POINT3X4")
      (footprint "eagle-import:PAD.03X.04")
      (libsource (lib "eagle-import") (part "TEST-POINT3X4"))
    )
    (comp (ref "TP128")
      (value "TEST-POINT3X4")
      (footprint "eagle-import:PAD.03X.04")
      (libsource (lib "eagle-import") (part "TEST-POINT3X4"))
    )
    (comp (ref "TP131")
      (value "TEST-POINT3X4")
      (footprint "eagle-import:PAD.03X.04")
      (libsource (lib "eagle-import") (part "TEST-POINT3X4"))
    )
    (comp (ref "TP134")
      (value "TEST-POINT3X4")
      (footprint "eagle-import:PAD.03X.04")
      (libsource (lib "eagle-import") (part "TEST-POINT3X4"))
    )
    (comp (ref "TP135")
      (value "TEST-POINT3X4")
      (footprint "eagle-import:PAD.03X.04")
      (libsource (lib "eagle-import") (part "TEST-POINT3X4"))
    )
    (comp (ref "TP137")
      (value "TEST-POINT3X4")
      (footprint "eagle-import:PAD.03X.04")
      (libsource (lib "eagle-import") (part "TEST-POINT3X4"))
    )
    (comp (ref "TP142")
      (value "TEST-POINT3X4")
      (footprint "eagle-import:PAD.03X.04")
      (libsource (lib "eagle-import") (part "TEST-POINT3X4"))
    )
    (comp (ref "TP143")
      (value "TEST-POINT3X4")
      (footprint "eagle-import:PAD.03X.04")
      (libsource (lib "eagle-import") (part "TEST-POINT3X4"))
    )
    (comp (ref "TP146")
      (value "TEST-POINT3X4")
      (footprint "eagle-import:PAD.03X.04")
      (libsource (lib "eagle-import") (part "TEST-POINT3X4"))
    )
    (comp (ref "TP147")
      (value "TEST-POINT3X4")
      (footprint "eagle-import:PAD.03X.04")
      (libsource (lib "eagle-import") (part "TEST-POINT3X4"))
    )
    (comp (ref "TP148")
      (value "TEST-POINT3X4")
      (footprint "eagle-import:PAD.03X.04")
      (libsource (lib "eagle-import") (part "TEST-POINT3X4"))
    )
    (comp (ref "TP149")
      (value "TEST-POINT3X4")
      (footprint "eagle-import:PAD.03X.04")
      (libsource (lib "eagle-import") (part "TEST-POINT3X4"))
    )
    (comp (ref "TP152")
      (value "TEST-POINT3X4")
      (footprint "eagle-import:PAD.03X.04")
      (libsource (lib "eagle-import") (part "TEST-POINT3X4"))
    )
    (comp (ref "TP153")
      (value "TEST-POINT3X4")
      (footprint "eagle-import:PAD.03X.04")
      (libsource (lib "eagle-import") (part "TEST-POINT3X4"))
    )
    (comp (ref "TP158")
      (value "TEST-POINT3X4")
      (footprint "eagle-import:PAD.03X.04")
      (libsource (lib "eagle-import") (part "TEST-POINT3X4"))
    )
    (comp (ref "TP159")
      (value "TEST-POINT3X4")
      (footprint "eagle-import:PAD.03X.04")
      (libsource (lib "eagle-import") (part "TEST-POINT3X4"))
    )
    (comp (ref "TP162")
      (value "TEST-POINT3X4")
      (footprint "eagle-import:PAD.03X.04")
      (libsource (lib "eagle-import") (part "TEST-POINT3X4"))
    )
    (comp (ref "TP174")
      (value "TEST-POINT3X4")
      (footprint "eagle-import:PAD.03X.04")
      (libsource (lib "eagle-import") (part "TEST-POINT3X4"))
    )
    (comp (ref "TP177")
      (value "TEST-POINT3X4")
      (footprint "eagle-import:PAD.03X.04")
      (libsource (lib "eagle-import") (part "TEST-POINT3X4"))
    )
    (comp (ref "TP178")
      (value "TEST-POINT3X4")
      (footprint "eagle-import:PAD.03X.04")
      (libsource (lib "eagle-import") (part "TEST-POINT3X4"))
    )
    (comp (ref "TP180")
      (value "TEST-POINT3X4")
      (footprint "eagle-import:PAD.03X.04")
      (libsource (lib "eagle-import") (part "TEST-POINT3X4"))
    )
    (comp (ref "U3")
      (value "EMMC+RESET+5.1-COMPATIBLE-BA")
      (footprint "eagle-import:BGA-153(11.5X13)(EMMC-BA)")
      (libsource (lib "eagle-import") (part "EMMC+RESET+5.1-COMPATIBLE-BA"))
    )
    (comp (ref "U5")
      (value "SN74LVC8T245MPWREPPW24-M")
      (footprint "eagle-import:PW24-M")
      (fields (field (name "MANUFACTURER_PART_NUMBER") "SN74LVC8T245MPWREP"))
      (libsource (lib "eagle-import") (part "SN74LVC8T245MPWREPPW24-M"))
    )
    (comp (ref "U6")
      (value "CLVCH16T245MDGGREP")
      (footprint "eagle-import:DGG48-M")
      (libsource (lib "eagle-import") (part "CLVCH16T245MDGGREP"))
    )
    (comp (ref "U7")
      (value "OSD3358-512M-BSM")
      (footprint "eagle-import:OSD335X-BGA-256")
      (fields (field (name "DIGI-KEY_PART_NUMBER") "1676-1002-ND") (field (name "MF") "Octavo Systems"))
      (libsource (lib "eagle-import") (part "OSD3358-512M-BSM"))
    )
    (comp (ref "U8")
      (value "TLV70028QDDCRQ1")
      (footprint "eagle-import:SOT23-5")
      (libsource (lib "eagle-import") (part "TLV70028QDDCRQ1"))
    )
    (comp (ref "U9")
      (value "TCA9509DGKRDGK8-M")
      (footprint "eagle-import:DGK8-M")
      (fields (field (name "MANUFACTURER_PART_NUMBER") "TCA9509DGKR"))
      (libsource (lib "eagle-import") (part "TCA9509DGKRDGK8-M"))
    )
    (comp (ref "U11")
      (value "TCAN330")
      (footprint "eagle-import:SOT23-8_TI-DCN")
      (fields (field (name "MFR") "Texas Instruments") (field (name "MPN") "TCAN330GDCNT"))
      (libsource (lib "eagle-import") (part "TCAN330"))
    )
    (comp (ref "J1")
      (value "ORESAT-DEBUG-CONNECTOR-CARD")
      (footprint "eagle-import:TE_2-1734592-0")
      (libsource (lib "eagle-import") (part "ORESAT-DEBUG-CONNECTOR-CARD"))
    )
    (comp (ref "J4")
      (value "TFM-120-01-L-D-RA")
      (footprint "eagle-import:J-SAMTEC-TFM-120-X1-XXX-D-RA")
      (fields (field (name "MFR") "Samtec"))
      (libsource (lib "eagle-import") (part "J-SAMTEC-TFM-120-X1-XXX-D-RA"))
    )
    (comp (ref "TP58")
      (value "TEST-POINT3X4")
      (footprint "eagle-import:PAD.03X.04")
      (libsource (lib "eagle-import") (part "TEST-POINT3X4"))
    )
    (comp (ref "TP59")
      (value "TEST-POINT3X4")
      (footprint "eagle-import:PAD.03X.04")
      (libsource (lib "eagle-import") (part "TEST-POINT3X4"))
    )
    (comp (ref "TP60")
      (value "TEST-POINT3X4")
      (footprint "eagle-import:PAD.03X.04")
      (libsource (lib "eagle-import") (part "TEST-POINT3X4"))
    )
    (comp (ref "TP61")
      (value "TEST-POINT3X4")
      (footprint "eagle-import:PAD.03X.04")
      (libsource (lib "eagle-import") (part "TEST-POINT3X4"))
    )
    (comp (ref "TP62")
      (value "TEST-POINT3X4")
      (footprint "eagle-import:PAD.03X.04")
      (libsource (lib "eagle-import") (part "TEST-POINT3X4"))
    )
    (comp (ref "TP183")
      (value "TEST-POINT3X4")
      (footprint "eagle-import:PAD.03X.04")
      (libsource (lib "eagle-import") (part "TEST-POINT3X4"))
    )
    (comp (ref "TP184")
      (value "TEST-POINT3X4")
      (footprint "eagle-import:PAD.03X.04")
      (libsource (lib "eagle-import") (part "TEST-POINT3X4"))
    )
    (comp (ref "C32")
      (value "1u")
      (footprint "eagle-import:.0805-B-NOSILK")
      (libsource (lib "eagle-import") (part "C-EU0805-B-NOSILK"))
    )
    (comp (ref "C33")
      (value "NP")
      (footprint "eagle-import:.0603-A")
      (fields (field (name "MFR") "Samsung") (field (name "MPN") "CL05B104KO5NNNC"))
      (libsource (lib "eagle-import") (part "C-EU0603-A"))
    )
    (comp (ref "C34")
      (value "1uF")
      (footprint "eagle-import:.0603-A")
      (fields (field (name "MFR") "Samsung") (field (name "MPN") "CL05B104KO5NNNC"))
      (libsource (lib "eagle-import") (part "C-EU0603-A"))
    )
    (comp (ref "C35")
      (value "1u")
      (footprint "eagle-import:.0805-B-NOSILK")
      (libsource (lib "eagle-import") (part "C-EU0805-B-NOSILK"))
    )
    (comp (ref "C36")
      (value "22uF")
      (footprint "eagle-import:C1210")
      (libsource (lib "eagle-import") (part "C-EUC1210"))
    )
    (comp (ref "C37")
      (value "1uF")
      (footprint "eagle-import:.0603-A")
      (fields (field (name "MFR") "Samsung") (field (name "MPN") "CL05B104KO5NNNC"))
      (libsource (lib "eagle-import") (part "C-EU0603-A"))
    )
    (comp (ref "C38")
      (value "10uF")
      (footprint "eagle-import:.0805-B")
      (libsource (lib "eagle-import") (part "C-EU0805-B"))
    )
    (comp (ref "C39")
      (value "0.1uF")
      (footprint "eagle-import:.0603-A")
      (fields (field (name "MFR") "Samsung") (field (name "MPN") "CL05B104KO5NNNC"))
      (libsource (lib "eagle-import") (part "C-EU0603-A"))
    )
    (comp (ref "D6")
      (value "AMBER")
      (footprint "eagle-import:LED-0603")
      (libsource (lib "eagle-import") (part "SparkFun-LED_529_LED-GREEN0603"))
    )
    (comp (ref "D7")
      (value "GREEN")
      (footprint "eagle-import:LED-0603")
      (libsource (lib "eagle-import") (part "LED-GREEN0603"))
    )
    (comp (ref "D8")
      (value "GREEN")
      (footprint "eagle-import:LED-0603")
      (libsource (lib "eagle-import") (part "LED-GREEN0603"))
    )
    (comp (ref "L1")
      (value "6.8u")
      (footprint "eagle-import:ECS-MPI4040")
      (fields (field (name "MFR") "ECS") (field (name "MPN") "ECS-MPI4040R4-6R8-R"))
      (libsource (lib "eagle-import") (part "L-ECS-MPI4040"))
    )
    (comp (ref "Q2")
      (value "PMV45EN")
      (footprint "eagle-import:SOT23")
      (libsource (lib "eagle-import") (part "PMV45EN"))
    )
    (comp (ref "Q3")
      (value "DMP2240UDM")
      (footprint "eagle-import:SOT23-6")
      (fields (field (name "MFR") "Diodes Inc") (field (name "MPN") "DMP2240UDM"))
      (libsource (lib "eagle-import") (part "Q-MOSFET-PCH-dual-SOT23-6_MOSFET-PCH-SOT23-6"))
    )
    (comp (ref "Q4")
      (value "PMV45EN")
      (footprint "eagle-import:SOT23")
      (libsource (lib "eagle-import") (part "PMV45EN"))
    )
    (comp (ref "Q5")
      (value "MOSFET-PCH-SOT23-6")
      (footprint "eagle-import:SOT23-6")
      (fields (field (name "MFR") "Diodes Inc") (field (name "MPN") "DMP3050LVT-7"))
      (libsource (lib "eagle-import") (part "MOSFET-PCH-SOT23-6"))
    )
    (comp (ref "Q6")
      (value "MOSFET-PCH-SOT23-6")
      (footprint "eagle-import:SOT23-6")
      (fields (field (name "MFR") "Diodes Inc") (field (name "MPN") "DMP3050LVT-7"))
      (libsource (lib "eagle-import") (part "MOSFET-PCH-SOT23-6"))
    )
    (comp (ref "R32")
      (value "10k")
      (footprint "eagle-import:.0603-A")
      (fields (field (name "MFR") "Samsung") (field (name "MPN") "RC1005F6653CS"))
      (libsource (lib "eagle-import") (part "R-US_0603-A"))
    )
    (comp (ref "R33")
      (value "NP")
      (footprint "eagle-import:.0603-A")
      (fields (field (name "MFR") "Samsung") (field (name "MPN") "RC1005F6653CS"))
      (libsource (lib "eagle-import") (part "R-US_0603-A"))
    )
    (comp (ref "R34")
      (value "10k")
      (footprint "eagle-import:.0603-A")
      (fields (field (name "MFR") "Samsung") (field (name "MPN") "RC1005F6653CS"))
      (libsource (lib "eagle-import") (part "R-US_0603-A"))
    )
    (comp (ref "R35")
      (value "10k")
      (footprint "eagle-import:.0603-A")
      (fields (field (name "MFR") "Samsung") (field (name "MPN") "RC1005F6653CS"))
      (libsource (lib "eagle-import") (part "R-US_0603-A"))
    )
    (comp (ref "R36")
      (value "1M")
      (footprint "eagle-import:.0603-A")
      (fields (field (name "MFR") "Samsung") (field (name "MPN") "RC1005F6653CS"))
      (libsource (lib "eagle-import") (part "R-US_0603-A"))
    )
    (comp (ref "R37")
      (value "330k")
      (footprint "eagle-import:.0603-A")
      (fields (field (name "MFR") "Samsung") (field (name "MPN") "RC1005F6653CS"))
      (libsource (lib "eagle-import") (part "R-US_0603-A"))
    )
    (comp (ref "R38")
      (value "NP")
      (footprint "eagle-import:.0603-A")
      (fields (field (name "MFR") "Samsung") (field (name "MPN") "RC1005F6653CS"))
      (libsource (lib "eagle-import") (part "R-US_0603-A"))
    )
    (comp (ref "R39")
      (value "10k")
      (footprint "eagle-import:.0603-A")
      (fields (field (name "MFR") "Samsung") (field (name "MPN") "RC1005F6653CS"))
      (libsource (lib "eagle-import") (part "R-US_0603-A"))
    )
    (comp (ref "R40")
      (value "NP")
      (footprint "eagle-import:.0603-A")
      (fields (field (name "MFR") "Samsung") (field (name "MPN") "RC1005F6653CS"))
      (libsource (lib "eagle-import") (part "R-US_0603-A"))
    )
    (comp (ref "R41")
      (value "100")
      (footprint "eagle-import:.0603-A")
      (fields (field (name "MFR") "Samsung") (field (name "MPN") "RC1005F6653CS"))
      (libsource (lib "eagle-import") (part "R-US_0603-A"))
    )
    (comp (ref "R42")
      (value "NP")
      (footprint "eagle-import:.0603-A")
      (fields (field (name "MFR") "Samsung") (field (name "MPN") "RC1005F6653CS"))
      (libsource (lib "eagle-import") (part "R-US_0603-A"))
    )
    (comp (ref "R43")
      (value "10k")
      (footprint "eagle-import:.0603-A")
      (fields (field (name "MFR") "Samsung") (field (name "MPN") "RC1005F6653CS"))
      (libsource (lib "eagle-import") (part "R-US_0603-A"))
    )
    (comp (ref "R44")
      (value "1M")
      (footprint "eagle-import:.0603-A")
      (fields (field (name "MFR") "Samsung") (field (name "MPN") "RC1005F6653CS"))
      (libsource (lib "eagle-import") (part "R-US_0603-A"))
    )
    (comp (ref "R45")
      (value "330k")
      (footprint "eagle-import:.0603-A")
      (fields (field (name "MFR") "Samsung") (field (name "MPN") "RC1005F6653CS"))
      (libsource (lib "eagle-import") (part "R-US_0603-A"))
    )
    (comp (ref "R46")
      (value "10k")
      (footprint "eagle-import:.0603-A")
      (fields (field (name "MFR") "Samsung") (field (name "MPN") "RC1005F6653CS"))
      (libsource (lib "eagle-import") (part "R-US_0603-A"))
    )
    (comp (ref "R47")
      (value "0")
      (footprint "eagle-import:.0603-A")
      (fields (field (name "MFR") "Samsung") (field (name "MPN") "RC1005F6653CS"))
      (libsource (lib "eagle-import") (part "R-US_0603-A"))
    )
    (comp (ref "R48")
      (value "100")
      (footprint "eagle-import:.0603-A")
      (fields (field (name "MFR") "Samsung") (field (name "MPN") "RC1005F6653CS"))
      (libsource (lib "eagle-import") (part "R-US_0603-A"))
    )
    (comp (ref "R49")
      (value "2.7k")
      (footprint "eagle-import:.0603-A")
      (fields (field (name "MFR") "Samsung") (field (name "MPN") "RC1005F6653CS"))
      (libsource (lib "eagle-import") (part "R-US_0603-A"))
    )
    (comp (ref "R50")
      (value "0")
      (footprint "eagle-import:.0603-A")
      (fields (field (name "MFR") "Samsung") (field (name "MPN") "RC1005F6653CS"))
      (libsource (lib "eagle-import") (part "R-US_0603-A"))
    )
    (comp (ref "R51")
      (value "NP")
      (footprint "eagle-import:.0603-A")
      (fields (field (name "MFR") "Samsung") (field (name "MPN") "RC1005F6653CS"))
      (libsource (lib "eagle-import") (part "R-US_0603-A"))
    )
    (comp (ref "R52")
      (value "10k")
      (footprint "eagle-import:.0603-A")
      (fields (field (name "MFR") "Samsung") (field (name "MPN") "RC1005F6653CS"))
      (libsource (lib "eagle-import") (part "R-US_0603-A"))
    )
    (comp (ref "R53")
      (value "NP")
      (footprint "eagle-import:.0603-A")
      (fields (field (name "MFR") "Samsung") (field (name "MPN") "RC1005F6653CS"))
      (libsource (lib "eagle-import") (part "R-US_0603-A"))
    )
    (comp (ref "R54")
      (value "NP")
      (footprint "eagle-import:.0603-A")
      (fields (field (name "MFR") "Samsung") (field (name "MPN") "RC1005F6653CS"))
      (libsource (lib "eagle-import") (part "R-US_0603-A"))
    )
    (comp (ref "R55")
      (value "NP")
      (footprint "eagle-import:.0603-A")
      (fields (field (name "MFR") "Samsung") (field (name "MPN") "RC1005F6653CS"))
      (libsource (lib "eagle-import") (part "R-US_0603-A"))
    )
    (comp (ref "R56")
      (value "NP")
      (footprint "eagle-import:.0603-A")
      (fields (field (name "MFR") "Samsung") (field (name "MPN") "RC1005F6653CS"))
      (libsource (lib "eagle-import") (part "R-US_0603-A"))
    )
    (comp (ref "R57")
      (value "NP")
      (footprint "eagle-import:.0603-A")
      (fields (field (name "MFR") "Samsung") (field (name "MPN") "RC1005F6653CS"))
      (libsource (lib "eagle-import") (part "R-US_0603-A"))
    )
    (comp (ref "R58")
      (value "NP")
      (footprint "eagle-import:.0603-A")
      (fields (field (name "MFR") "Samsung") (field (name "MPN") "RC1005F6653CS"))
      (libsource (lib "eagle-import") (part "R-US_0603-A"))
    )
    (comp (ref "R59")
      (value "47k")
      (footprint "eagle-import:.0603-A")
      (fields (field (name "MFR") "Samsung") (field (name "MPN") "RC1005F6653CS"))
      (libsource (lib "eagle-import") (part "R-US_0603-A"))
    )
    (comp (ref "R60")
      (value "47k")
      (footprint "eagle-import:.0603-A")
      (fields (field (name "MFR") "Samsung") (field (name "MPN") "RC1005F6653CS"))
      (libsource (lib "eagle-import") (part "R-US_0603-A"))
    )
    (comp (ref "R61")
      (value "2.7k")
      (footprint "eagle-import:.0603-A")
      (fields (field (name "MFR") "Samsung") (field (name "MPN") "RC1005F6653CS"))
      (libsource (lib "eagle-import") (part "R-US_0603-A"))
    )
    (comp (ref "R62")
      (value "2.7k")
      (footprint "eagle-import:.0603-A")
      (fields (field (name "MFR") "Samsung") (field (name "MPN") "RC1005F6653CS"))
      (libsource (lib "eagle-import") (part "R-US_0603-A"))
    )
    (comp (ref "R63")
      (value "100m")
      (footprint "eagle-import:R1206")
      (libsource (lib "eagle-import") (part "rcl_334_R-US_R1206"))
    )
    (comp (ref "R64")
      (value "10k")
      (footprint "eagle-import:.0603-A")
      (fields (field (name "MFR") "Samsung") (field (name "MPN") "RC1005F6653CS"))
      (libsource (lib "eagle-import") (part "R-US_0603-A"))
    )
    (comp (ref "R65")
      (value "NP")
      (footprint "eagle-import:.0603-A")
      (fields (field (name "MFR") "Samsung") (field (name "MPN") "RC1005F6653CS"))
      (libsource (lib "eagle-import") (part "R-US_0603-A"))
    )
    (comp (ref "R66")
      (value "NP")
      (footprint "eagle-import:.0603-A")
      (fields (field (name "MFR") "Samsung") (field (name "MPN") "RC1005F6653CS"))
      (libsource (lib "eagle-import") (part "R-US_0603-A"))
    )
    (comp (ref "R67")
      (value "NP")
      (footprint "eagle-import:.0603-A")
      (fields (field (name "MFR") "Samsung") (field (name "MPN") "RC1005F6653CS"))
      (libsource (lib "eagle-import") (part "R-US_0603-A"))
    )
    (comp (ref "R68")
      (value "NP")
      (footprint "eagle-import:.0603-A")
      (fields (field (name "MFR") "Samsung") (field (name "MPN") "RC1005F6653CS"))
      (libsource (lib "eagle-import") (part "R-US_0603-A"))
    )
    (comp (ref "R69")
      (value "NP")
      (footprint "eagle-import:.0603-A")
      (fields (field (name "MFR") "Samsung") (field (name "MPN") "RC1005F6653CS"))
      (libsource (lib "eagle-import") (part "R-US_0603-A"))
    )
    (comp (ref "R70")
      (value "NP")
      (footprint "eagle-import:.0603-A")
      (fields (field (name "MFR") "Samsung") (field (name "MPN") "RC1005F6653CS"))
      (libsource (lib "eagle-import") (part "R-US_0603-A"))
    )
    (comp (ref "R71")
      (value "100")
      (footprint "eagle-import:.0603-A")
      (fields (field (name "MFR") "Samsung") (field (name "MPN") "RC1005F6653CS"))
      (libsource (lib "eagle-import") (part "R-US_0603-A"))
    )
    (comp (ref "R72")
      (value "10k")
      (footprint "eagle-import:.0603-A")
      (fields (field (name "MFR") "Samsung") (field (name "MPN") "RC1005F6653CS"))
      (libsource (lib "eagle-import") (part "R-US_0603-A"))
    )
    (comp (ref "TP41")
      (value "TEST-POINT")
      (footprint "eagle-import:2MM-TEST-POINT")
      (libsource (lib "eagle-import") (part "TEST-POINT"))
    )
    (comp (ref "TP42")
      (value "TEST-POINT")
      (footprint "eagle-import:2MM-TEST-POINT")
      (libsource (lib "eagle-import") (part "TEST-POINT"))
    )
    (comp (ref "TP43")
      (value "TEST-POINT")
      (footprint "eagle-import:2MM-TEST-POINT")
      (libsource (lib "eagle-import") (part "TEST-POINT"))
    )
    (comp (ref "TP44")
      (value "TEST-POINT")
      (footprint "eagle-import:2MM-TEST-POINT")
      (libsource (lib "eagle-import") (part "TEST-POINT"))
    )
    (comp (ref "TP45")
      (value "TEST-POINT")
      (footprint "eagle-import:2MM-TEST-POINT")
      (libsource (lib "eagle-import") (part "TEST-POINT"))
    )
    (comp (ref "TP46")
      (value "TEST-POINT")
      (footprint "eagle-import:2MM-TEST-POINT")
      (libsource (lib "eagle-import") (part "TEST-POINT"))
    )
    (comp (ref "TP47")
      (value "TEST-POINT")
      (footprint "eagle-import:2MM-TEST-POINT")
      (libsource (lib "eagle-import") (part "TEST-POINT"))
    )
    (comp (ref "TP48")
      (value "TEST-POINT")
      (footprint "eagle-import:2MM-TEST-POINT")
      (libsource (lib "eagle-import") (part "TEST-POINT"))
    )
    (comp (ref "TP49")
      (value "TEST-POINT")
      (footprint "eagle-import:2MM-TEST-POINT")
      (libsource (lib "eagle-import") (part "TEST-POINT"))
    )
    (comp (ref "TP50")
      (value "TEST-POINT")
      (footprint "eagle-import:2MM-TEST-POINT")
      (libsource (lib "eagle-import") (part "TEST-POINT"))
    )
    (comp (ref "TP51")
      (value "TEST-POINT")
      (footprint "eagle-import:2MM-TEST-POINT")
      (libsource (lib "eagle-import") (part "TEST-POINT"))
    )
    (comp (ref "TP52")
      (value "TEST-POINT")
      (footprint "eagle-import:2MM-TEST-POINT")
      (libsource (lib "eagle-import") (part "TEST-POINT"))
    )
    (comp (ref "TP53")
      (value "TEST-POINT")
      (footprint "eagle-import:2MM-TEST-POINT")
      (libsource (lib "eagle-import") (part "TEST-POINT"))
    )
    (comp (ref "TP54")
      (value "TEST-POINT")
      (footprint "eagle-import:2MM-TEST-POINT")
      (libsource (lib "eagle-import") (part "TEST-POINT"))
    )
    (comp (ref "TP55")
      (value "TEST-POINT")
      (footprint "eagle-import:2MM-TEST-POINT")
      (libsource (lib "eagle-import") (part "TEST-POINT"))
    )
    (comp (ref "TP56")
      (value "TEST-POINT")
      (footprint "eagle-import:2MM-TEST-POINT")
      (libsource (lib "eagle-import") (part "TEST-POINT"))
    )
    (comp (ref "TP57")
      (value "TEST-POINT")
      (footprint "eagle-import:2MM-TEST-POINT")
      (libsource (lib "eagle-import") (part "TEST-POINT"))
    )
    (comp (ref "TP63")
      (value "TEST-POINT")
      (footprint "eagle-import:2MM-TEST-POINT")
      (libsource (lib "eagle-import") (part "TEST-POINT"))
    )
    (comp (ref "TP64")
      (value "TEST-POINT")
      (footprint "eagle-import:2MM-TEST-POINT")
      (libsource (lib "eagle-import") (part "TEST-POINT"))
    )
    (comp (ref "TP65")
      (value "TEST-POINT")
      (footprint "eagle-import:2MM-TEST-POINT")
      (libsource (lib "eagle-import") (part "TEST-POINT"))
    )
    (comp (ref "TP66")
      (value "TEST-POINT")
      (footprint "eagle-import:2MM-TEST-POINT")
      (libsource (lib "eagle-import") (part "TEST-POINT"))
    )
    (comp (ref "U12")
      (value "MIC842LYC5")
      (footprint "eagle-import:SC70-5")
      (libsource (lib "eagle-import") (part "MIC842LYC5"))
    )
    (comp (ref "U13")
      (value "MIC842LYC5")
      (footprint "eagle-import:SC70-5")
      (libsource (lib "eagle-import") (part "MIC842LYC5"))
    )
    (comp (ref "U14")
      (value "MAX4211FETE")
      (footprint "eagle-import:QFN65P400X400X80-17T210")
      (fields (field (name "MFR") "Maxim"))
      (libsource (lib "eagle-import") (part "MAX4211"))
    )
    (comp (ref "U15")
      (value "TPS62112")
      (footprint "eagle-import:S-PVQFN-16")
      (fields (field (name "MFR") "TI") (field (name "MPN") "TPS62111RSA"))
      (libsource (lib "eagle-import") (part "TPS6211X"))
    )
    (comp (ref "U16")
      (value "MAX7310ATE")
      (footprint "eagle-import:QFN65P400X400X80-17T210")
      (fields (field (name "MFR") "Maxim"))
      (libsource (lib "eagle-import") (part "MAX7310"))
    )
    (comp (ref "C13")
      (value "22uF")
      (footprint "eagle-import:C1210")
      (libsource (lib "eagle-import") (part "C-EUC1210"))
    )
    (comp (ref "C14")
      (value "22uF")
      (footprint "eagle-import:C1210")
      (libsource (lib "eagle-import") (part "C-EUC1210"))
    )
    (comp (ref "C15")
      (value "22uF")
      (footprint "eagle-import:C1210")
      (libsource (lib "eagle-import") (part "C-EUC1210"))
    )
    (comp (ref "C18")
      (value "0.1uF, 6.3V")
      (footprint "eagle-import:.0603-A")
      (libsource (lib "eagle-import") (part "C-EU0603-A"))
    )
    (comp (ref "D1")
      (value "GREEN")
      (footprint "eagle-import:LED-0603")
      (libsource (lib "eagle-import") (part "LED-GREEN0603"))
    )
    (comp (ref "J2")
      (value "CONN_02PTH3")
      (footprint "eagle-import:1X02_LONGPADS")
      (libsource (lib "eagle-import") (part "CONN_02PTH3"))
    )
    (comp (ref "JP101")
      (value "JUMPER-SMT_2_NC_TRACE_SILK")
      (footprint "eagle-import:SMT-JUMPER_2_NC_TRACE_SILK")
      (libsource (lib "eagle-import") (part "JUMPER-SMT_2_NC_TRACE_SILK"))
    )
    (comp (ref "JP104")
      (value "JUMPER-SMT_2_NC_TRACE_SILK")
      (footprint "eagle-import:SMT-JUMPER_2_NC_TRACE_SILK")
      (libsource (lib "eagle-import") (part "JUMPER-SMT_2_NC_TRACE_SILK"))
    )
    (comp (ref "Q1")
      (value "MMBT2907")
      (footprint "eagle-import:SOT23-BEC")
      (libsource (lib "eagle-import") (part "MMBT2907SMD"))
    )
    (comp (ref "R1")
      (value "1k")
      (footprint "eagle-import:.0603-A")
      (libsource (lib "eagle-import") (part "R-US_0603-A"))
    )
    (comp (ref "R15")
      (value "10k")
      (footprint "eagle-import:.0603-A")
      (libsource (lib "eagle-import") (part "R-US_0603-A"))
    )
    (comp (ref "R23")
      (value "499")
      (footprint "eagle-import:.0603-A")
      (libsource (lib "eagle-import") (part "R-US_0603-A"))
    )
    (comp (ref "R28")
      (value "10.0K")
      (footprint "eagle-import:.0603-A")
      (libsource (lib "eagle-import") (part "R-US_0603-A"))
    )
    (comp (ref "R31")
      (value "40.2K")
      (footprint "eagle-import:.0603-A")
      (libsource (lib "eagle-import") (part "R-US_0603-A"))
    )
    (comp (ref "TP2")
      (value "TEST-POINT3X4")
      (footprint "eagle-import:PAD.03X.04")
      (libsource (lib "eagle-import") (part "TEST-POINT3X4"))
    )
    (comp (ref "TP3")
      (value "TEST-POINT3X4")
      (footprint "eagle-import:PAD.03X.04")
      (libsource (lib "eagle-import") (part "TEST-POINT3X4"))
    )
    (comp (ref "TP4")
      (value "TEST-POINT3X4")
      (footprint "eagle-import:PAD.03X.04")
      (libsource (lib "eagle-import") (part "TEST-POINT3X4"))
    )
    (comp (ref "TP14")
      (value "TEST-POINT3X4")
      (footprint "eagle-import:PAD.03X.04")
      (libsource (lib "eagle-import") (part "TEST-POINT3X4"))
    )
    (comp (ref "TP25")
      (value "TEST-POINT3X4")
      (footprint "eagle-import:PAD.03X.04")
      (libsource (lib "eagle-import") (part "TEST-POINT3X4"))
    )
    (comp (ref "TP102")
      (value "TEST-POINT3X4")
      (footprint "eagle-import:PAD.03X.04")
      (libsource (lib "eagle-import") (part "TEST-POINT3X4"))
    )
    (comp (ref "TP109")
      (value "TEST-POINT3X4")
      (footprint "eagle-import:PAD.03X.04")
      (libsource (lib "eagle-import") (part "TEST-POINT3X4"))
    )
    (comp (ref "TP110")
      (value "TEST-POINT3X4")
      (footprint "eagle-import:PAD.03X.04")
      (libsource (lib "eagle-import") (part "TEST-POINT3X4"))
    )
    (comp (ref "TP112")
      (value "TEST-POINT3X4")
      (footprint "eagle-import:PAD.03X.04")
      (libsource (lib "eagle-import") (part "TEST-POINT3X4"))
    )
    (comp (ref "TP121")
      (value "TEST-POINT3X4")
      (footprint "eagle-import:PAD.03X.04")
      (libsource (lib "eagle-import") (part "TEST-POINT3X4"))
    )
    (comp (ref "TP129")
      (value "TEST-POINT3X4")
      (footprint "eagle-import:PAD.03X.04")
      (libsource (lib "eagle-import") (part "TEST-POINT3X4"))
    )
    (comp (ref "TP130")
      (value "TEST-POINT3X4")
      (footprint "eagle-import:PAD.03X.04")
      (libsource (lib "eagle-import") (part "TEST-POINT3X4"))
    )
    (comp (ref "TP132")
      (value "TEST-POINT3X4")
      (footprint "eagle-import:PAD.03X.04")
      (libsource (lib "eagle-import") (part "TEST-POINT3X4"))
    )
    (comp (ref "TP136")
      (value "TEST-POINT3X4")
      (footprint "eagle-import:PAD.03X.04")
      (libsource (lib "eagle-import") (part "TEST-POINT3X4"))
    )
    (comp (ref "TP140")
      (value "TEST-POINT3X4")
      (footprint "eagle-import:PAD.03X.04")
      (libsource (lib "eagle-import") (part "TEST-POINT3X4"))
    )
    (comp (ref "TP145")
      (value "TEST-POINT3X4")
      (footprint "eagle-import:PAD.03X.04")
      (libsource (lib "eagle-import") (part "TEST-POINT3X4"))
    )
    (comp (ref "TP150")
      (value "TEST-POINT3X4")
      (footprint "eagle-import:PAD.03X.04")
      (libsource (lib "eagle-import") (part "TEST-POINT3X4"))
    )
    (comp (ref "TP151")
      (value "TEST-POINT3X4")
      (footprint "eagle-import:PAD.03X.04")
      (libsource (lib "eagle-import") (part "TEST-POINT3X4"))
    )
    (comp (ref "TP154")
      (value "TEST-POINT3X4")
      (footprint "eagle-import:PAD.03X.04")
      (libsource (lib "eagle-import") (part "TEST-POINT3X4"))
    )
    (comp (ref "TP155")
      (value "TEST-POINT3X4")
      (footprint "eagle-import:PAD.03X.04")
      (libsource (lib "eagle-import") (part "TEST-POINT3X4"))
    )
    (comp (ref "TP156")
      (value "TEST-POINT3X4")
      (footprint "eagle-import:PAD.03X.04")
      (libsource (lib "eagle-import") (part "TEST-POINT3X4"))
    )
    (comp (ref "TP157")
      (value "TEST-POINT3X4")
      (footprint "eagle-import:PAD.03X.04")
      (libsource (lib "eagle-import") (part "TEST-POINT3X4"))
    )
    (comp (ref "TP160")
      (value "TEST-POINT3X4")
      (footprint "eagle-import:PAD.03X.04")
      (libsource (lib "eagle-import") (part "TEST-POINT3X4"))
    )
    (comp (ref "TP161")
      (value "TEST-POINT3X4")
      (footprint "eagle-import:PAD.03X.04")
      (libsource (lib "eagle-import") (part "TEST-POINT3X4"))
    )
    (comp (ref "TP163")
      (value "TEST-POINT3X4")
      (footprint "eagle-import:PAD.03X.04")
      (libsource (lib "eagle-import") (part "TEST-POINT3X4"))
    )
    (comp (ref "TP164")
      (value "TEST-POINT3X4")
      (footprint "eagle-import:PAD.03X.04")
      (libsource (lib "eagle-import") (part "TEST-POINT3X4"))
    )
    (comp (ref "TP165")
      (value "TEST-POINT3X4")
      (footprint "eagle-import:PAD.03X.04")
      (libsource (lib "eagle-import") (part "TEST-POINT3X4"))
    )
    (comp (ref "TP166")
      (value "TEST-POINT3X4")
      (footprint "eagle-import:PAD.03X.04")
      (libsource (lib "eagle-import") (part "TEST-POINT3X4"))
    )
    (comp (ref "TP167")
      (value "TEST-POINT3X4")
      (footprint "eagle-import:PAD.03X.04")
      (libsource (lib "eagle-import") (part "TEST-POINT3X4"))
    )
    (comp (ref "TP172")
      (value "TEST-POINT3X4")
      (footprint "eagle-import:PAD.03X.04")
      (libsource (lib "eagle-import") (part "TEST-POINT3X4"))
    )
    (comp (ref "TP173")
      (value "TEST-POINT3X4")
      (footprint "eagle-import:PAD.03X.04")
      (libsource (lib "eagle-import") (part "TEST-POINT3X4"))
    )
    (comp (ref "U4")
      (value "SN74LVC1G07DCK")
      (footprint "eagle-import:C70(TI-DCK)")
      (libsource (lib "eagle-import") (part "SN74LVC1G07DCK"))
    )
    (comp (ref "U10")
      (value "TLVH431")
      (footprint "eagle-import:SOT23-3")
      (libsource (lib "eagle-import") (part "TLVH431"))
    )
    (comp (ref "C1")
      (value "10uF")
      (footprint "eagle-import:.0805-B")
      (libsource (lib "eagle-import") (part "C-EU0805-B"))
    )
    (comp (ref "C4")
      (value "0.1uF")
      (footprint "eagle-import:.0603-A")
      (libsource (lib "eagle-import") (part "C-EU0603-A"))
    )
    (comp (ref "C7")
      (value "10uF")
      (footprint "eagle-import:.0805-B")
      (libsource (lib "eagle-import") (part "C-EU0805-B"))
    )
    (comp (ref "C19")
      (value "18pF, 50V")
      (footprint "eagle-import:.0603-A")
      (libsource (lib "eagle-import") (part "C-EU0603-A"))
    )
    (comp (ref "C22")
      (value "18pF, 50V")
      (footprint "eagle-import:.0603-A")
      (libsource (lib "eagle-import") (part "C-EU0603-A"))
    )
    (comp (ref "C29")
      (value "18pF, 50V")
      (footprint "eagle-import:.0603-A")
      (libsource (lib "eagle-import") (part "C-EU0603-A"))
    )
    (comp (ref "C30")
      (value "18pF, 50V")
      (footprint "eagle-import:.0603-A")
      (libsource (lib "eagle-import") (part "C-EU0603-A"))
    )
    (comp (ref "FB1")
      (value "30Ω/1.8A")
      (footprint "eagle-import:0603")
      (fields (field (name "MPN") "BLM18KG300JH1D"))
      (libsource (lib "eagle-import") (part "FERRITE_BEAD-0603"))
    )
    (comp (ref "FB2")
      (value "30Ω/1.8A")
      (footprint "eagle-import:0603")
      (fields (field (name "MPN") "BLM18KG300JH1D"))
      (libsource (lib "eagle-import") (part "FERRITE_BEAD-0603"))
    )
    (comp (ref "J102")
      (value "FTSH-105-XX-X-DV-K")
      (footprint "eagle-import:CON10_2X5_DUK_FTSH")
      (libsource (lib "eagle-import") (part "FTSH-105-XX-X-DV-K"))
    )
    (comp (ref "JP100")
      (value "JUMPER-SMT_2_NC_TRACE_SILK")
      (footprint "eagle-import:SMT-JUMPER_2_NC_TRACE_SILK")
      (libsource (lib "eagle-import") (part "JUMPER-SMT_2_NC_TRACE_SILK"))
    )
    (comp (ref "R6")
      (value "10k")
      (footprint "eagle-import:.0603-A")
      (libsource (lib "eagle-import") (part "R-US_0603-A"))
    )
    (comp (ref "R7")
      (value "10k")
      (footprint "eagle-import:.0603-A")
      (libsource (lib "eagle-import") (part "R-US_0603-A"))
    )
    (comp (ref "R13")
      (value "1M, 1%")
      (footprint "eagle-import:.0603-A")
      (libsource (lib "eagle-import") (part "R-US_0603-A"))
    )
    (comp (ref "R19")
      (value "10k")
      (footprint "eagle-import:.0603-A")
      (libsource (lib "eagle-import") (part "R-US_0603-A"))
    )
    (comp (ref "R20")
      (value "10k")
      (footprint "eagle-import:.0603-A")
      (libsource (lib "eagle-import") (part "R-US_0603-A"))
    )
    (comp (ref "R22")
      (value "10k")
      (footprint "eagle-import:.0603-A")
      (libsource (lib "eagle-import") (part "R-US_0603-A"))
    )
    (comp (ref "R27")
      (value "1M, DNI")
      (footprint "eagle-import:.0603-A")
      (libsource (lib "eagle-import") (part "R-US_0603-A"))
    )
    (comp (ref "TP1")
      (value "TEST-POINT3X4")
      (footprint "eagle-import:PAD.03X.04")
      (libsource (lib "eagle-import") (part "TEST-POINT3X4"))
    )
    (comp (ref "TP38")
      (value "TEST-POINT3X4")
      (footprint "eagle-import:PAD.03X.04")
      (libsource (lib "eagle-import") (part "TEST-POINT3X4"))
    )
    (comp (ref "TP39")
      (value "TEST-POINT3X4")
      (footprint "eagle-import:PAD.03X.04")
      (libsource (lib "eagle-import") (part "TEST-POINT3X4"))
    )
    (comp (ref "TP133")
      (value "TEST-POINT3X4")
      (footprint "eagle-import:PAD.03X.04")
      (libsource (lib "eagle-import") (part "TEST-POINT3X4"))
    )
    (comp (ref "TP138")
      (value "TEST-POINT3X4")
      (footprint "eagle-import:PAD.03X.04")
      (libsource (lib "eagle-import") (part "TEST-POINT3X4"))
    )
    (comp (ref "TP139")
      (value "TEST-POINT3X4")
      (footprint "eagle-import:PAD.03X.04")
      (libsource (lib "eagle-import") (part "TEST-POINT3X4"))
    )
    (comp (ref "TP141")
      (value "TEST-POINT3X4")
      (footprint "eagle-import:PAD.03X.04")
      (libsource (lib "eagle-import") (part "TEST-POINT3X4"))
    )
    (comp (ref "TP144")
      (value "TEST-POINT3X4")
      (footprint "eagle-import:PAD.03X.04")
      (libsource (lib "eagle-import") (part "TEST-POINT3X4"))
    )
    (comp (ref "TP168")
      (value "TEST-POINT3X4")
      (footprint "eagle-import:PAD.03X.04")
      (libsource (lib "eagle-import") (part "TEST-POINT3X4"))
    )
    (comp (ref "TP169")
      (value "TEST-POINT3X4")
      (footprint "eagle-import:PAD.03X.04")
      (libsource (lib "eagle-import") (part "TEST-POINT3X4"))
    )
    (comp (ref "TP170")
      (value "TEST-POINT3X4")
      (footprint "eagle-import:PAD.03X.04")
      (libsource (lib "eagle-import") (part "TEST-POINT3X4"))
    )
    (comp (ref "TP171")
      (value "TEST-POINT3X4")
      (footprint "eagle-import:PAD.03X.04")
      (libsource (lib "eagle-import") (part "TEST-POINT3X4"))
    )
    (comp (ref "TP175")
      (value "TEST-POINT3X4")
      (footprint "eagle-import:PAD.03X.04")
      (libsource (lib "eagle-import") (part "TEST-POINT3X4"))
    )
    (comp (ref "TP176")
      (value "TEST-POINT3X4")
      (footprint "eagle-import:PAD.03X.04")
      (libsource (lib "eagle-import") (part "TEST-POINT3X4"))
    )
    (comp (ref "TP179")
      (value "TEST-POINT3X4")
      (footprint "eagle-import:PAD.03X.04")
      (libsource (lib "eagle-import") (part "TEST-POINT3X4"))
    )
    (comp (ref "TP181")
      (value "TEST-POINT3X4")
      (footprint "eagle-import:PAD.03X.04")
      (libsource (lib "eagle-import") (part "TEST-POINT3X4"))
    )
    (comp (ref "TP182")
      (value "TEST-POINT3X4")
      (footprint "eagle-import:PAD.03X.04")
      (libsource (lib "eagle-import") (part "TEST-POINT3X4"))
    )
    (comp (ref "U1")
      (value "RCLAMP0504FB")
      (footprint "eagle-import:SC70-6")
      (fields (field (name "MPN") "RCLAMP0504FBTCT"))
      (libsource (lib "eagle-import") (part "RCLAMP0504FB"))
    )
    (comp (ref "U2")
      (value "TPS2051CDBVR")
      (footprint "eagle-import:DBV5")
      (libsource (lib "eagle-import") (part "TPS2051CDBVR"))
    )
    (comp (ref "Y1")
      (value "24MHz")
      (footprint "eagle-import:5X3.2-4SMD")
      (fields (field (name "MPN") "ECS-240-12-30BQ-AEN-TR"))
      (libsource (lib "eagle-import") (part "ECS-240-12-30BQ-AEN-TR"))
    )
    (comp (ref "Y2")
      (value "ABS07-32.768KHZ-T")
      (footprint "eagle-import:CRYSTAL_3.2X1.5")
      (fields (field (name "MPN") "ABS07-32.768KHZ-T"))
      (libsource (lib "eagle-import") (part "ABS07-32.768KHZ-T"))
    )
  )
  (nets
    (net (code "7") (name "2.8V") (class "Default")
      (node (ref "C21") (pin "1") (pinfunction "1_1") (pintype "passive"))
      (node (ref "C23") (pin "1") (pinfunction "1_1") (pintype "passive"))
      (node (ref "C24") (pin "1") (pinfunction "1_1") (pintype "passive"))
      (node (ref "C25") (pin "1") (pinfunction "1_1") (pintype "passive"))
      (node (ref "C26") (pin "1") (pinfunction "1_1") (pintype "passive"))
      (node (ref "R17") (pin "1") (pinfunction "1_1") (pintype "passive"))
      (node (ref "R18") (pin "1") (pinfunction "1_1") (pintype "passive"))
      (node (ref "U5") (pin "1") (pinfunction "VCCA_1") (pintype "power_in"))
      (node (ref "U6") (pin "18") (pinfunction "VCCB_18") (pintype "power_in"))
      (node (ref "U6") (pin "7") (pinfunction "VCCB_7") (pintype "power_in"))
      (node (ref "U8") (pin "5") (pinfunction "OUT_5") (pintype "power_in"))
      (node (ref "U9") (pin "8") (pinfunction "VCCB_8") (pintype "power_in"))
    )
    (net (code "8") (name "3.3V") (class "Default")
      (node (ref "C11") (pin "1") (pinfunction "1_1") (pintype "passive"))
      (node (ref "C16") (pin "1") (pinfunction "1_1") (pintype "passive"))
      (node (ref "C17") (pin "1") (pinfunction "1_1") (pintype "passive"))
      (node (ref "C2") (pin "1") (pinfunction "1_1") (pintype "passive"))
      (node (ref "C20") (pin "1") (pinfunction "1_1") (pintype "passive"))
      (node (ref "C27") (pin "1") (pinfunction "1_1") (pintype "passive"))
      (node (ref "C28") (pin "1") (pinfunction "1_1") (pintype "passive"))
      (node (ref "C3") (pin "1") (pinfunction "1_1") (pintype "passive"))
      (node (ref "C31") (pin "2") (pinfunction "2_2") (pintype "passive"))
      (node (ref "C5") (pin "1") (pinfunction "1_1") (pintype "passive"))
      (node (ref "C6") (pin "1") (pinfunction "1_1") (pintype "passive"))
      (node (ref "C8") (pin "1") (pinfunction "1_1") (pintype "passive"))
      (node (ref "C9") (pin "1") (pinfunction "1_1") (pintype "passive"))
      (node (ref "J100") (pin "4") (pinfunction "VDD_4") (pintype "bidirectional"))
      (node (ref "J101") (pin "31") (pinfunction "31_31") (pintype "passive"))
      (node (ref "J101") (pin "32") (pinfunction "32_32") (pintype "passive"))
      (node (ref "J101") (pin "33") (pinfunction "33_33") (pintype "passive"))
      (node (ref "J102") (pin "1") (pinfunction "VTREF_1") (pintype "passive"))
      (node (ref "R1") (pin "1") (pinfunction "1_1") (pintype "passive"))
      (node (ref "R10") (pin "10") (pinfunction "55_10") (pintype "passive"))
      (node (ref "R10") (pin "5") (pinfunction "55_5") (pintype "passive"))
      (node (ref "R11") (pin "2") (pinfunction "2_2") (pintype "passive"))
      (node (ref "R12") (pin "2") (pinfunction "2_2") (pintype "passive"))
      (node (ref "R20") (pin "2") (pinfunction "2_2") (pintype "passive"))
      (node (ref "R21") (pin "2") (pinfunction "2_2") (pintype "passive"))
      (node (ref "R22") (pin "2") (pinfunction "2_2") (pintype "passive"))
      (node (ref "R24") (pin "10") (pinfunction "55_10") (pintype "passive"))
      (node (ref "R24") (pin "5") (pinfunction "55_5") (pintype "passive"))
      (node (ref "R29") (pin "1") (pinfunction "1_1") (pintype "passive"))
      (node (ref "R30") (pin "1") (pinfunction "1_1") (pintype "passive"))
      (node (ref "R8") (pin "10") (pinfunction "55_10") (pintype "passive"))
      (node (ref "R8") (pin "5") (pinfunction "55_5") (pintype "passive"))
      (node (ref "R9") (pin "10") (pinfunction "55_10") (pintype "passive"))
      (node (ref "R9") (pin "5") (pinfunction "55_5") (pintype "passive"))
      (node (ref "TP25") (pin "P$1") (pinfunction "1_P$1") (pintype "bidirectional"))
      (node (ref "U11") (pin "3") (pinfunction "VCC_3") (pintype "power_in"))
      (node (ref "U3") (pin "C6") (pinfunction "VDDQ_C6") (pintype "power_in"))
      (node (ref "U3") (pin "E6") (pinfunction "VDDIO_E6") (pintype "power_in"))
      (node (ref "U3") (pin "F5") (pinfunction "VDDIO_F5") (pintype "power_in"))
      (node (ref "U3") (pin "J10") (pinfunction "VDDIO_J10") (pintype "power_in"))
      (node (ref "U3") (pin "K9") (pinfunction "VDDIO_K9") (pintype "power_in"))
      (node (ref "U3") (pin "M4") (pinfunction "VDDQ_M4") (pintype "power_in"))
      (node (ref "U3") (pin "N4") (pinfunction "VDDQ_N4") (pintype "power_in"))
      (node (ref "U3") (pin "P3") (pinfunction "VDDQ_P3") (pintype "power_in"))
      (node (ref "U3") (pin "P5") (pinfunction "VDDQ_P5") (pintype "power_in"))
      (node (ref "U5") (pin "23") (pinfunction "VCCB_23") (pintype "power_in"))
      (node (ref "U5") (pin "24") (pinfunction "VCCB_24") (pintype "power_in"))
      (node (ref "U6") (pin "31") (pinfunction "VCCA_31") (pintype "power_in"))
      (node (ref "U6") (pin "42") (pinfunction "VCCA_42") (pintype "power_in"))
      (node (ref "U7") (pin "F6") (pinfunction "SYS_VDD1_3P3V_F6") (pintype "power_in"))
      (node (ref "U7") (pin "F7") (pinfunction "SYS_VDD1_3P3V_F7") (pintype "power_in"))
      (node (ref "U7") (pin "G6") (pinfunction "SYS_VDD1_3P3V_G6") (pintype "power_in"))
      (node (ref "U7") (pin "G7") (pinfunction "SYS_VDD1_3P3V_G7") (pintype "power_in"))
      (node (ref "U8") (pin "1") (pinfunction "IN_1") (pintype "power_in"))
      (node (ref "U8") (pin "3") (pinfunction "EN_3") (pintype "input"))
      (node (ref "U9") (pin "1") (pinfunction "VCCA_1") (pintype "power_in"))
    )
    (net (code "9") (name "5V") (class "Default")
      (node (ref "C36") (pin "1") (pinfunction "1_1") (pintype "passive"))
      (node (ref "J2") (pin "1") (pinfunction "1_1") (pintype "passive"))
      (node (ref "L1") (pin "2") (pinfunction "2_2") (pintype "passive"))
      (node (ref "R62") (pin "2") (pinfunction "2_2") (pintype "passive"))
      (node (ref "TP49") (pin "1") (pinfunction "1_1") (pintype "passive"))
      (node (ref "U15") (pin "10") (pinfunction "FB_10") (pintype "input"))
    )
    (net (code "10") (name "5V_IN") (class "Default")
      (node (ref "C14") (pin "1") (pinfunction "1_1") (pintype "passive"))
      (node (ref "J2") (pin "2") (pinfunction "2_2") (pintype "passive"))
      (node (ref "U7") (pin "P10") (pinfunction "VIN_AC_P10") (pintype "power_in"))
      (node (ref "U7") (pin "R10") (pinfunction "VIN_AC_R10") (pintype "power_in"))
      (node (ref "U7") (pin "T10") (pinfunction "VIN_AC_T10") (pintype "power_in"))
    )
    (net (code "11") (name "AD0") (class "Default")
      (node (ref "R57") (pin "1") (pinfunction "1_1") (pintype "passive"))
      (node (ref "R58") (pin "2") (pinfunction "2_2") (pintype "passive"))
      (node (ref "R69") (pin "2") (pinfunction "2_2") (pintype "passive"))
      (node (ref "R70") (pin "1") (pinfunction "1_1") (pintype "passive"))
      (node (ref "U16") (pin "1") (pinfunction "AD0_1") (pintype "input"))
    )
    (net (code "12") (name "AD1") (class "Default")
      (node (ref "R55") (pin "1") (pinfunction "1_1") (pintype "passive"))
      (node (ref "R56") (pin "2") (pinfunction "2_2") (pintype "passive"))
      (node (ref "R67") (pin "2") (pinfunction "2_2") (pintype "passive"))
      (node (ref "R68") (pin "1") (pinfunction "1_1") (pintype "passive"))
      (node (ref "U16") (pin "2") (pinfunction "AD1_2") (pintype "input"))
    )
    (net (code "13") (name "AD2") (class "Default")
      (node (ref "R53") (pin "1") (pinfunction "1_1") (pintype "passive"))
      (node (ref "R54") (pin "2") (pinfunction "2_2") (pintype "passive"))
      (node (ref "R65") (pin "2") (pinfunction "2_2") (pintype "passive"))
      (node (ref "R66") (pin "1") (pinfunction "1_1") (pintype "passive"))
      (node (ref "U16") (pin "3") (pinfunction "AD2_3") (pintype "input"))
    )
    (net (code "14") (name "BOOT0") (class "Default")
      (node (ref "TP51") (pin "1") (pinfunction "1_1") (pintype "passive"))
      (node (ref "U16") (pin "10") (pinfunction "IO5_10") (pintype "bidirectional"))
    )
    (net (code "15") (name "BUS_OE") (class "Default")
      (node (ref "R11") (pin "1") (pinfunction "1_1") (pintype "passive"))
      (node (ref "TP113") (pin "P$1") (pinfunction "1_P$1") (pintype "bidirectional"))
      (node (ref "U6") (pin "25") (pinfunction "~{2OE}_25") (pintype "input"))
      (node (ref "U6") (pin "48") (pinfunction "~{1OE}_48") (pintype "input"))
      (node (ref "U7") (pin "F14") (pinfunction "MII1_CRS_F14") (pintype "bidirectional"))
    )
    (net (code "16") (name "CAM_OE") (class "Default")
      (node (ref "TP8") (pin "P$1") (pinfunction "1_P$1") (pintype "bidirectional"))
      (node (ref "U5") (pin "17") (pinfunction "B5_17") (pintype "bidirectional"))
      (node (ref "U7") (pin "F15") (pinfunction "MII1_COL_F15") (pintype "bidirectional"))
    )
    (net (code "17") (name "CAN1_H") (class "Default")
      (node (ref "J4") (pin "33") (pinfunction "33_33") (pintype "passive"))
      (node (ref "J4") (pin "34") (pinfunction "34_34") (pintype "passive"))
      (node (ref "TP184") (pin "P$1") (pinfunction "1_P$1") (pintype "bidirectional"))
    )
    (net (code "18") (name "CAN1_L") (class "Default")
      (node (ref "J4") (pin "35") (pinfunction "35_35") (pintype "passive"))
      (node (ref "J4") (pin "36") (pinfunction "36_36") (pintype "passive"))
      (node (ref "TP183") (pin "P$1") (pinfunction "1_P$1") (pintype "bidirectional"))
    )
    (net (code "19") (name "CAN2_H") (class "Default")
      (node (ref "J4") (pin "17") (pinfunction "17_17") (pintype "passive"))
      (node (ref "J4") (pin "18") (pinfunction "18_18") (pintype "passive"))
      (node (ref "U11") (pin "7") (pinfunction "CANH_7") (pintype "bidirectional"))
    )
    (net (code "20") (name "CAN2_L") (class "Default")
      (node (ref "J4") (pin "19") (pinfunction "19_19") (pintype "passive"))
      (node (ref "J4") (pin "20") (pinfunction "20_20") (pintype "passive"))
      (node (ref "U11") (pin "6") (pinfunction "CANL_6") (pintype "bidirectional"))
    )
    (net (code "21") (name "CB-RESET") (class "Default")
      (node (ref "R39") (pin "2") (pinfunction "2_2") (pintype "passive"))
      (node (ref "TP54") (pin "1") (pinfunction "1_1") (pintype "passive"))
      (node (ref "U14") (pin "9") (pinfunction "CIN2-_9") (pintype "input"))
      (node (ref "U16") (pin "9") (pinfunction "IO4_9") (pintype "bidirectional"))
    )
    (net (code "22") (name "CB_CTRL") (class "Default")
      (node (ref "Q2") (pin "1") (pinfunction "G_1") (pintype "passive"))
      (node (ref "Q5") (pin "3") (pinfunction "G_3") (pintype "passive"))
      (node (ref "R64") (pin "1") (pinfunction "1_1") (pintype "passive"))
      (node (ref "TP52") (pin "1") (pinfunction "1_1") (pintype "passive"))
      (node (ref "U14") (pin "3") (pinfunction "LE_3") (pintype "input"))
      (node (ref "U14") (pin "4") (pinfunction "COUT1_4") (pintype "open_collector"))
      (node (ref "U14") (pin "6") (pinfunction "COUT2_6") (pintype "open_collector"))
    )
    (net (code "23") (name "CLK_EN") (class "Default")
      (node (ref "TP11") (pin "P$1") (pinfunction "1_P$1") (pintype "bidirectional"))
      (node (ref "U5") (pin "20") (pinfunction "B2_20") (pintype "bidirectional"))
      (node (ref "U7") (pin "E16") (pinfunction "MII1_RX_CLK_E16") (pintype "bidirectional"))
    )
    (net (code "24") (name "CLK_EN_E") (class "Default")
      (node (ref "J101") (pin "23") (pinfunction "23_23") (pintype "passive"))
      (node (ref "U5") (pin "4") (pinfunction "A2_4") (pintype "bidirectional"))
    )
    (net (code "25") (name "D0_E") (class "Default")
      (node (ref "J101") (pin "12") (pinfunction "12_12") (pintype "passive"))
      (node (ref "U6") (pin "11") (pinfunction "1B7_11") (pintype "bidirectional"))
    )
    (net (code "26") (name "D0_I") (class "Default")
      (node (ref "JP102") (pin "1") (pinfunction "1_1") (pintype "passive"))
      (node (ref "TP19") (pin "P$1") (pinfunction "1_P$1") (pintype "bidirectional"))
      (node (ref "U6") (pin "38") (pinfunction "1A7_38") (pintype "bidirectional"))
    )
    (net (code "27") (name "D1_E") (class "Default")
      (node (ref "J101") (pin "11") (pinfunction "11_11") (pintype "passive"))
      (node (ref "U6") (pin "12") (pinfunction "1B8_12") (pintype "bidirectional"))
    )
    (net (code "28") (name "D1_I") (class "Default")
      (node (ref "JP103") (pin "1") (pinfunction "1_1") (pintype "passive"))
      (node (ref "TP21") (pin "P$1") (pinfunction "1_P$1") (pintype "bidirectional"))
      (node (ref "U6") (pin "37") (pinfunction "1A8_37") (pintype "bidirectional"))
    )
    (net (code "29") (name "D2_E") (class "Default")
      (node (ref "J101") (pin "10") (pinfunction "10_10") (pintype "passive"))
      (node (ref "U6") (pin "13") (pinfunction "2B1_13") (pintype "bidirectional"))
    )
    (net (code "30") (name "D2_I") (class "Default")
      (node (ref "JP110") (pin "1") (pinfunction "1_1") (pintype "passive"))
      (node (ref "TP24") (pin "P$1") (pinfunction "1_P$1") (pintype "bidirectional"))
      (node (ref "U6") (pin "36") (pinfunction "2A1_36") (pintype "bidirectional"))
    )
    (net (code "31") (name "D3_E") (class "Default")
      (node (ref "J101") (pin "9") (pinfunction "9_9") (pintype "passive"))
      (node (ref "U6") (pin "14") (pinfunction "2B2_14") (pintype "bidirectional"))
    )
    (net (code "32") (name "D3_I") (class "Default")
      (node (ref "JP111") (pin "1") (pinfunction "1_1") (pintype "passive"))
      (node (ref "TP23") (pin "P$1") (pinfunction "1_P$1") (pintype "bidirectional"))
      (node (ref "U6") (pin "35") (pinfunction "2A2_35") (pintype "bidirectional"))
    )
    (net (code "33") (name "D4_E") (class "Default")
      (node (ref "J101") (pin "8") (pinfunction "8_8") (pintype "passive"))
      (node (ref "U6") (pin "16") (pinfunction "2B3_16") (pintype "bidirectional"))
    )
    (net (code "34") (name "D4_I") (class "Default")
      (node (ref "TP27") (pin "P$1") (pinfunction "1_P$1") (pintype "bidirectional"))
      (node (ref "U6") (pin "33") (pinfunction "2A3_33") (pintype "bidirectional"))
      (node (ref "U7") (pin "A1") (pinfunction "MCASP0_ACLKX_A1") (pintype "bidirectional"))
    )
    (net (code "35") (name "D5_E") (class "Default")
      (node (ref "J101") (pin "7") (pinfunction "7_7") (pintype "passive"))
      (node (ref "U6") (pin "17") (pinfunction "2B4_17") (pintype "bidirectional"))
    )
    (net (code "36") (name "D5_I") (class "Default")
      (node (ref "TP26") (pin "P$1") (pinfunction "1_P$1") (pintype "bidirectional"))
      (node (ref "U6") (pin "32") (pinfunction "2A4_32") (pintype "bidirectional"))
      (node (ref "U7") (pin "A2") (pinfunction "MCASP0_FSX_A2") (pintype "bidirectional"))
    )
    (net (code "37") (name "D6_E") (class "Default")
      (node (ref "J101") (pin "6") (pinfunction "6_6") (pintype "passive"))
      (node (ref "U6") (pin "19") (pinfunction "2B5_19") (pintype "bidirectional"))
    )
    (net (code "38") (name "D6_I") (class "Default")
      (node (ref "TP29") (pin "P$1") (pinfunction "1_P$1") (pintype "bidirectional"))
      (node (ref "U6") (pin "30") (pinfunction "2A5_30") (pintype "bidirectional"))
      (node (ref "U7") (pin "B2") (pinfunction "MCASP0_AXR0_B2") (pintype "bidirectional"))
    )
    (net (code "39") (name "D7_E") (class "Default")
      (node (ref "J101") (pin "13") (pinfunction "13_13") (pintype "passive"))
      (node (ref "U6") (pin "9") (pinfunction "1B6_9") (pintype "bidirectional"))
    )
    (net (code "40") (name "D7_I") (class "Default")
      (node (ref "TP20") (pin "P$1") (pinfunction "1_P$1") (pintype "bidirectional"))
      (node (ref "U6") (pin "40") (pinfunction "1A6_40") (pintype "bidirectional"))
      (node (ref "U7") (pin "B1") (pinfunction "MCASP0_AHCLKR_B1") (pintype "bidirectional"))
    )
    (net (code "41") (name "D8_E") (class "Default")
      (node (ref "J101") (pin "14") (pinfunction "14_14") (pintype "passive"))
      (node (ref "U6") (pin "8") (pinfunction "1B5_8") (pintype "bidirectional"))
    )
    (net (code "42") (name "D8_I") (class "Default")
      (node (ref "TP17") (pin "P$1") (pinfunction "1_P$1") (pintype "bidirectional"))
      (node (ref "U6") (pin "41") (pinfunction "1A5_41") (pintype "bidirectional"))
      (node (ref "U7") (pin "A3") (pinfunction "MCASP0_ACLKR_A3") (pintype "bidirectional"))
    )
    (net (code "43") (name "D9_E") (class "Default")
      (node (ref "J101") (pin "15") (pinfunction "15_15") (pintype "passive"))
      (node (ref "U6") (pin "6") (pinfunction "1B4_6") (pintype "bidirectional"))
    )
    (net (code "44") (name "D9_I") (class "Default")
      (node (ref "TP18") (pin "P$1") (pinfunction "1_P$1") (pintype "bidirectional"))
      (node (ref "U6") (pin "43") (pinfunction "1A4_43") (pintype "bidirectional"))
      (node (ref "U7") (pin "B3") (pinfunction "MCASP0_FSR_B3") (pintype "bidirectional"))
    )
    (net (code "45") (name "D10_E") (class "Default")
      (node (ref "J101") (pin "16") (pinfunction "16_16") (pintype "passive"))
      (node (ref "U6") (pin "5") (pinfunction "1B3_5") (pintype "bidirectional"))
    )
    (net (code "46") (name "D10_I") (class "Default")
      (node (ref "TP15") (pin "P$1") (pinfunction "1_P$1") (pintype "bidirectional"))
      (node (ref "U6") (pin "44") (pinfunction "1A3_44") (pintype "bidirectional"))
      (node (ref "U7") (pin "C3") (pinfunction "MCASP0_AXR1_C3") (pintype "bidirectional"))
    )
    (net (code "47") (name "D11_E") (class "Default")
      (node (ref "J101") (pin "17") (pinfunction "17_17") (pintype "passive"))
      (node (ref "U6") (pin "3") (pinfunction "1B2_3") (pintype "bidirectional"))
    )
    (net (code "48") (name "D11_I") (class "Default")
      (node (ref "TP16") (pin "P$1") (pinfunction "1_P$1") (pintype "bidirectional"))
      (node (ref "U6") (pin "46") (pinfunction "1A2_46") (pintype "bidirectional"))
      (node (ref "U7") (pin "C4") (pinfunction "MCASP0_AHCLKX_C4") (pintype "bidirectional"))
    )
    (net (code "49") (name "EEPROM_WP") (class "Default")
      (node (ref "J1") (pin "20") (pinfunction "DEBUG-3_20") (pintype "passive"))
      (node (ref "TP112") (pin "P$1") (pinfunction "1_P$1") (pintype "bidirectional"))
      (node (ref "U7") (pin "M2") (pinfunction "EEPROM_WP_M2") (pintype "bidirectional"))
    )
    (net (code "50") (name "FLASH") (class "Default")
      (node (ref "TP13") (pin "P$1") (pinfunction "1_P$1") (pintype "bidirectional"))
      (node (ref "U6") (pin "47") (pinfunction "1A1_47") (pintype "bidirectional"))
      (node (ref "U7") (pin "G15") (pinfunction "MII1_TXD3_G15") (pintype "bidirectional"))
    )
    (net (code "51") (name "FLASH_E") (class "Default")
      (node (ref "J101") (pin "28") (pinfunction "28_28") (pintype "passive"))
      (node (ref "U6") (pin "2") (pinfunction "1B1_2") (pintype "bidirectional"))
    )
    (net (code "52") (name "GND") (class "Default")
      (node (ref "C1") (pin "2") (pinfunction "2_2") (pintype "passive"))
      (node (ref "C10") (pin "2") (pinfunction "2_2") (pintype "passive"))
      (node (ref "C11") (pin "2") (pinfunction "2_2") (pintype "passive"))
      (node (ref "C12") (pin "2") (pinfunction "2_2") (pintype "passive"))
      (node (ref "C13") (pin "2") (pinfunction "2_2") (pintype "passive"))
      (node (ref "C14") (pin "2") (pinfunction "2_2") (pintype "passive"))
      (node (ref "C15") (pin "2") (pinfunction "2_2") (pintype "passive"))
      (node (ref "C16") (pin "2") (pinfunction "2_2") (pintype "passive"))
      (node (ref "C17") (pin "2") (pinfunction "2_2") (pintype "passive"))
      (node (ref "C18") (pin "2") (pinfunction "2_2") (pintype "passive"))
      (node (ref "C2") (pin "2") (pinfunction "2_2") (pintype "passive"))
      (node (ref "C20") (pin "2") (pinfunction "2_2") (pintype "passive"))
      (node (ref "C21") (pin "2") (pinfunction "2_2") (pintype "passive"))
      (node (ref "C23") (pin "2") (pinfunction "2_2") (pintype "passive"))
      (node (ref "C24") (pin "2") (pinfunction "2_2") (pintype "passive"))
      (node (ref "C25") (pin "2") (pinfunction "2_2") (pintype "passive"))
      (node (ref "C26") (pin "2") (pinfunction "2_2") (pintype "passive"))
      (node (ref "C27") (pin "2") (pinfunction "2_2") (pintype "passive"))
      (node (ref "C28") (pin "2") (pinfunction "2_2") (pintype "passive"))
      (node (ref "C3") (pin "2") (pinfunction "2_2") (pintype "passive"))
      (node (ref "C31") (pin "1") (pinfunction "1_1") (pintype "passive"))
      (node (ref "C32") (pin "2") (pinfunction "2_2") (pintype "passive"))
      (node (ref "C34") (pin "2") (pinfunction "2_2") (pintype "passive"))
      (node (ref "C35") (pin "2") (pinfunction "2_2") (pintype "passive"))
      (node (ref "C36") (pin "2") (pinfunction "2_2") (pintype "passive"))
      (node (ref "C37") (pin "2") (pinfunction "2_2") (pintype "passive"))
      (node (ref "C38") (pin "2") (pinfunction "2_2") (pintype "passive"))
      (node (ref "C39") (pin "1") (pinfunction "1_1") (pintype "passive"))
      (node (ref "C4") (pin "2") (pinfunction "2_2") (pintype "passive"))
      (node (ref "C5") (pin "2") (pinfunction "2_2") (pintype "passive"))
      (node (ref "C6") (pin "2") (pinfunction "2_2") (pintype "passive"))
      (node (ref "C7") (pin "2") (pinfunction "2_2") (pintype "passive"))
      (node (ref "C8") (pin "2") (pinfunction "2_2") (pintype "passive"))
      (node (ref "C9") (pin "2") (pinfunction "2_2") (pintype "passive"))
      (node (ref "D1") (pin "C") (pinfunction "C_C") (pintype "passive"))
      (node (ref "D2") (pin "C") (pinfunction "C_C") (pintype "passive"))
      (node (ref "D3") (pin "C") (pinfunction "C_C") (pintype "passive"))
      (node (ref "D4") (pin "C") (pinfunction "C_C") (pintype "passive"))
      (node (ref "D5") (pin "C") (pinfunction "C_C") (pintype "passive"))
      (node (ref "D6") (pin "C") (pinfunction "C_C") (pintype "passive"))
      (node (ref "D7") (pin "C") (pinfunction "C_C") (pintype "passive"))
      (node (ref "D8") (pin "C") (pinfunction "C_C") (pintype "passive"))
      (node (ref "J1") (pin "3") (pinfunction "GND_3") (pintype "passive"))
      (node (ref "J1") (pin "6") (pinfunction "GND_6") (pintype "passive"))
      (node (ref "J1") (pin "9") (pinfunction "GND_9") (pintype "passive"))
      (node (ref "J1") (pin "PAD1") (pinfunction "PAD_PAD1") (pintype "bidirectional"))
      (node (ref "J1") (pin "PAD2") (pinfunction "PAD_PAD2") (pintype "bidirectional"))
      (node (ref "J100") (pin "6") (pinfunction "VSS_6") (pintype "bidirectional"))
      (node (ref "J100") (pin "CGND1") (pinfunction "CGND_CGND1") (pintype "bidirectional"))
      (node (ref "J100") (pin "CGND2") (pinfunction "CGND_CGND2") (pintype "bidirectional"))
      (node (ref "J100") (pin "CGND3") (pinfunction "CGND_CGND3") (pintype "bidirectional"))
      (node (ref "J100") (pin "CGND4") (pinfunction "CGND_CGND4") (pintype "bidirectional"))
      (node (ref "J100") (pin "CGND5") (pinfunction "CGND_CGND5") (pintype "bidirectional"))
      (node (ref "J100") (pin "CGND6") (pinfunction "CGND_CGND6") (pintype "bidirectional"))
      (node (ref "J100") (pin "GND") (pinfunction "VSS_GND") (pintype "bidirectional"))
      (node (ref "J101") (pin "1") (pinfunction "1_1") (pintype "passive"))
      (node (ref "J101") (pin "18") (pinfunction "18_18") (pintype "passive"))
      (node (ref "J101") (pin "19") (pinfunction "19_19") (pintype "passive"))
      (node (ref "J101") (pin "2") (pinfunction "2_2") (pintype "passive"))
      (node (ref "J101") (pin "20") (pinfunction "20_20") (pintype "passive"))
      (node (ref "J101") (pin "34") (pinfunction "34_34") (pintype "passive"))
      (node (ref "J101") (pin "35") (pinfunction "35_35") (pintype "passive"))
      (node (ref "J101") (pin "36") (pinfunction "36_36") (pintype "passive"))
      (node (ref "J101") (pin "S1") (pinfunction "PAD_S1") (pintype "bidirectional"))
      (node (ref "J101") (pin "S2") (pinfunction "PAD_S2") (pintype "bidirectional"))
      (node (ref "J102") (pin "3") (pinfunction "GND_3") (pintype "passive"))
      (node (ref "J102") (pin "5") (pinfunction "GND_5") (pintype "passive"))
      (node (ref "J102") (pin "9") (pinfunction "GNDDET_9") (pintype "passive"))
      (node (ref "J4") (pin "27") (pinfunction "27_27") (pintype "passive"))
      (node (ref "J4") (pin "28") (pinfunction "28_28") (pintype "passive"))
      (node (ref "J4") (pin "29") (pinfunction "29_29") (pintype "passive"))
      (node (ref "J4") (pin "30") (pinfunction "30_30") (pintype "passive"))
      (node (ref "J4") (pin "31") (pinfunction "31_31") (pintype "passive"))
      (node (ref "J4") (pin "32") (pinfunction "32_32") (pintype "passive"))
      (node (ref "J4") (pin "37") (pinfunction "37_37") (pintype "passive"))
      (node (ref "J4") (pin "38") (pinfunction "38_38") (pintype "passive"))
      (node (ref "JP100") (pin "2") (pinfunction "2_2") (pintype "passive"))
      (node (ref "Q2") (pin "2") (pinfunction "S_2") (pintype "passive"))
      (node (ref "Q4") (pin "2") (pinfunction "S_2") (pintype "passive"))
      (node (ref "R14") (pin "2") (pinfunction "2_2") (pintype "passive"))
      (node (ref "R15") (pin "1") (pinfunction "1_1") (pintype "passive"))
      (node (ref "R16") (pin "2") (pinfunction "2_2") (pintype "passive"))
      (node (ref "R19") (pin "1") (pinfunction "1_1") (pintype "passive"))
      (node (ref "R25") (pin "10") (pinfunction "55_10") (pintype "passive"))
      (node (ref "R25") (pin "5") (pinfunction "55_5") (pintype "passive"))
      (node (ref "R26") (pin "10") (pinfunction "55_10") (pintype "passive"))
      (node (ref "R26") (pin "5") (pinfunction "55_5") (pintype "passive"))
      (node (ref "R33") (pin "1") (pinfunction "1_1") (pintype "passive"))
      (node (ref "R35") (pin "1") (pinfunction "1_1") (pintype "passive"))
      (node (ref "R39") (pin "1") (pinfunction "1_1") (pintype "passive"))
      (node (ref "R40") (pin "1") (pinfunction "1_1") (pintype "passive"))
      (node (ref "R42") (pin "1") (pinfunction "1_1") (pintype "passive"))
      (node (ref "R43") (pin "1") (pinfunction "1_1") (pintype "passive"))
      (node (ref "R46") (pin "1") (pinfunction "1_1") (pintype "passive"))
      (node (ref "R51") (pin "1") (pinfunction "1_1") (pintype "passive"))
      (node (ref "R54") (pin "1") (pinfunction "1_1") (pintype "passive"))
      (node (ref "R56") (pin "1") (pinfunction "1_1") (pintype "passive"))
      (node (ref "R58") (pin "1") (pinfunction "1_1") (pintype "passive"))
      (node (ref "R6") (pin "1") (pinfunction "1_1") (pintype "passive"))
      (node (ref "U1") (pin "2") (pinfunction "GND_2") (pintype "power_in"))
      (node (ref "U11") (pin "2") (pinfunction "GND_2") (pintype "power_in"))
      (node (ref "U12") (pin "2") (pinfunction "GND_2") (pintype "power_in"))
      (node (ref "U13") (pin "2") (pinfunction "GND_2") (pintype "power_in"))
      (node (ref "U14") (pin "7") (pinfunction "GND_7") (pintype "power_in"))
      (node (ref "U14") (pin "EPAD") (pinfunction "GND_EPAD") (pintype "power_in"))
      (node (ref "U15") (pin "1") (pinfunction "GND_1") (pintype "power_in"))
      (node (ref "U15") (pin "11") (pinfunction "GND_11") (pintype "power_in"))
      (node (ref "U15") (pin "12") (pinfunction "GND_12") (pintype "power_in"))
      (node (ref "U15") (pin "16") (pinfunction "GND_16") (pintype "power_in"))
      (node (ref "U15") (pin "6") (pinfunction "LBO_6") (pintype "open_collector"))
      (node (ref "U15") (pin "7") (pinfunction "LBI_7") (pintype "input"))
      (node (ref "U15") (pin "9") (pinfunction "GND_9") (pintype "power_in"))
      (node (ref "U15") (pin "PAD") (pinfunction "GND_PAD") (pintype "power_in"))
      (node (ref "U16") (pin "6") (pinfunction "GND_6") (pintype "power_in"))
      (node (ref "U16") (pin "EPAD") (pinfunction "GND_EPAD") (pintype "power_in"))
      (node (ref "U2") (pin "2") (pinfunction "GND_2") (pintype "power_in"))
      (node (ref "U3") (pin "C4") (pinfunction "VSSQ_C4") (pintype "power_in"))
      (node (ref "U3") (pin "E7") (pinfunction "VSSIO_E7") (pintype "power_in"))
      (node (ref "U3") (pin "G5") (pinfunction "VSSIO_G5") (pintype "power_in"))
      (node (ref "U3") (pin "H10") (pinfunction "VSSIO_H10") (pintype "power_in"))
      (node (ref "U3") (pin "J5") (pinfunction "VSSIO_J5") (pintype "power_in"))
      (node (ref "U3") (pin "K8") (pinfunction "VSSIO_K8") (pintype "power_in"))
      (node (ref "U3") (pin "N2") (pinfunction "VSSQ_N2") (pintype "power_in"))
      (node (ref "U3") (pin "N5") (pinfunction "VSSQ_N5") (pintype "power_in"))
      (node (ref "U3") (pin "P4") (pinfunction "VSSQ_P4") (pintype "power_in"))
      (node (ref "U3") (pin "P6") (pinfunction "VSSQ_P6") (pintype "power_in"))
      (node (ref "U4") (pin "3") (pinfunction "GND_3") (pintype "bidirectional"))
      (node (ref "U5") (pin "11") (pinfunction "GND_11") (pintype "power_in"))
      (node (ref "U5") (pin "12") (pinfunction "GND_12") (pintype "power_in"))
      (node (ref "U5") (pin "13") (pinfunction "GND_13") (pintype "power_in"))
      (node (ref "U6") (pin "10") (pinfunction "GND_10") (pintype "power_in"))
      (node (ref "U6") (pin "15") (pinfunction "GND_15") (pintype "power_in"))
      (node (ref "U6") (pin "21") (pinfunction "GND_21") (pintype "power_in"))
      (node (ref "U6") (pin "28") (pinfunction "GND_28") (pintype "power_in"))
      (node (ref "U6") (pin "34") (pinfunction "GND_34") (pintype "power_in"))
      (node (ref "U6") (pin "39") (pinfunction "GND_39") (pintype "power_in"))
      (node (ref "U6") (pin "4") (pinfunction "GND_4") (pintype "power_in"))
      (node (ref "U6") (pin "45") (pinfunction "GND_45") (pintype "power_in"))
      (node (ref "U7") (pin "D8") (pinfunction "DGND_D8") (pintype "bidirectional"))
      (node (ref "U7") (pin "D9") (pinfunction "DGND_D9") (pintype "bidirectional"))
      (node (ref "U7") (pin "E10") (pinfunction "DGND_E10") (pintype "bidirectional"))
      (node (ref "U7") (pin "E11") (pinfunction "DGND_E11") (pintype "bidirectional"))
      (node (ref "U7") (pin "E12") (pinfunction "DGND_E12") (pintype "bidirectional"))
      (node (ref "U7") (pin "E5") (pinfunction "DGND_E5") (pintype "bidirectional"))
      (node (ref "U7") (pin "E6") (pinfunction "DGND_E6") (pintype "bidirectional"))
      (node (ref "U7") (pin "E7") (pinfunction "DGND_E7") (pintype "bidirectional"))
      (node (ref "U7") (pin "E8") (pinfunction "DGND_E8") (pintype "bidirectional"))
      (node (ref "U7") (pin "E9") (pinfunction "DGND_E9") (pintype "bidirectional"))
      (node (ref "U7") (pin "F12") (pinfunction "DGND_F12") (pintype "bidirectional"))
      (node (ref "U7") (pin "F5") (pinfunction "DGND_F5") (pintype "bidirectional"))
      (node (ref "U7") (pin "G12") (pinfunction "DGND_G12") (pintype "bidirectional"))
      (node (ref "U7") (pin "G5") (pinfunction "DGND_G5") (pintype "bidirectional"))
      (node (ref "U7") (pin "H12") (pinfunction "DGND_H12") (pintype "bidirectional"))
      (node (ref "U7") (pin "H13") (pinfunction "DGND_H13") (pintype "bidirectional"))
      (node (ref "U7") (pin "H4") (pinfunction "DGND_H4") (pintype "bidirectional"))
      (node (ref "U7") (pin "H5") (pinfunction "DGND_H5") (pintype "bidirectional"))
      (node (ref "U7") (pin "J12") (pinfunction "DGND_J12") (pintype "bidirectional"))
      (node (ref "U7") (pin "J13") (pinfunction "DGND_J13") (pintype "bidirectional"))
      (node (ref "U7") (pin "J4") (pinfunction "DGND_J4") (pintype "bidirectional"))
      (node (ref "U7") (pin "J5") (pinfunction "DGND_J5") (pintype "bidirectional"))
      (node (ref "U7") (pin "K12") (pinfunction "DGND_K12") (pintype "bidirectional"))
      (node (ref "U7") (pin "K5") (pinfunction "DGND_K5") (pintype "bidirectional"))
      (node (ref "U7") (pin "L12") (pinfunction "DGND_L12") (pintype "bidirectional"))
      (node (ref "U7") (pin "L5") (pinfunction "DGND_L5") (pintype "bidirectional"))
      (node (ref "U7") (pin "M10") (pinfunction "DGND_M10") (pintype "bidirectional"))
      (node (ref "U7") (pin "M11") (pinfunction "DGND_M11") (pintype "bidirectional"))
      (node (ref "U7") (pin "M12") (pinfunction "DGND_M12") (pintype "bidirectional"))
      (node (ref "U7") (pin "M5") (pinfunction "DGND_M5") (pintype "bidirectional"))
      (node (ref "U7") (pin "M6") (pinfunction "DGND_M6") (pintype "bidirectional"))
      (node (ref "U7") (pin "M7") (pinfunction "DGND_M7") (pintype "bidirectional"))
      (node (ref "U7") (pin "M8") (pinfunction "DGND_M8") (pintype "bidirectional"))
      (node (ref "U7") (pin "M9") (pinfunction "DGND_M9") (pintype "bidirectional"))
      (node (ref "U7") (pin "N8") (pinfunction "DGND_N8") (pintype "bidirectional"))
      (node (ref "U7") (pin "N9") (pinfunction "DGND_N9") (pintype "bidirectional"))
      (node (ref "U8") (pin "2") (pinfunction "GND_2") (pintype "power_in"))
      (node (ref "U9") (pin "4") (pinfunction "GND_4") (pintype "power_in"))
      (node (ref "Y1") (pin "2") (pinfunction "GND_2") (pintype "power_in"))
      (node (ref "Y1") (pin "4") (pinfunction "GND_4") (pintype "power_in"))
    )
    (net (code "53") (name "HSYNC_E") (class "Default")
      (node (ref "J101") (pin "4") (pinfunction "4_4") (pintype "passive"))
      (node (ref "U6") (pin "22") (pinfunction "2B7_22") (pintype "bidirectional"))
    )
    (net (code "54") (name "HSYNC_I") (class "Default")
      (node (ref "TP119") (pin "P$1") (pinfunction "1_P$1") (pintype "bidirectional"))
      (node (ref "U6") (pin "27") (pinfunction "2A7_27") (pintype "bidirectional"))
      (node (ref "U7") (pin "P7") (pinfunction "GPMC_AD15_P7") (pintype "bidirectional"))
    )
    (net (code "55") (name "I2C0_SCL") (class "Default")
      (node (ref "J1") (pin "18") (pinfunction "DEBUG-1_18") (pintype "passive"))
      (node (ref "TP155") (pin "P$1") (pinfunction "1_P$1") (pintype "bidirectional"))
      (node (ref "U7") (pin "C10") (pinfunction "I2C0_SCL_C10") (pintype "bidirectional"))
      (node (ref "U7") (pin "D10") (pinfunction "PMIC_SCL_D10") (pintype "bidirectional"))
    )
    (net (code "56") (name "I2C0_SDA") (class "Default")
      (node (ref "J1") (pin "19") (pinfunction "DEBUG-2_19") (pintype "passive"))
      (node (ref "TP151") (pin "P$1") (pinfunction "1_P$1") (pintype "bidirectional"))
      (node (ref "U7") (pin "C11") (pinfunction "I2C0_SDA_C11") (pintype "bidirectional"))
      (node (ref "U7") (pin "D11") (pinfunction "PMIC_SDA_D11") (pintype "bidirectional"))
    )
    (net (code "57") (name "I2C2_SCL") (class "Default")
      (node (ref "J101") (pin "21") (pinfunction "21_21") (pintype "passive"))
      (node (ref "R17") (pin "2") (pinfunction "2_2") (pintype "passive"))
      (node (ref "U9") (pin "7") (pinfunction "SCLB_7") (pintype "bidirectional"))
    )
    (net (code "58") (name "I2C2_SDA") (class "Default")
      (node (ref "J101") (pin "22") (pinfunction "22_22") (pintype "passive"))
      (node (ref "R18") (pin "2") (pinfunction "2_2") (pintype "passive"))
      (node (ref "U9") (pin "6") (pinfunction "SDAB_6") (pintype "bidirectional"))
    )
    (net (code "59") (name "INPUT_EN") (class "Default")
      (node (ref "R12") (pin "1") (pinfunction "1_1") (pintype "passive"))
      (node (ref "TP12") (pin "P$1") (pinfunction "1_P$1") (pintype "bidirectional"))
      (node (ref "U5") (pin "22") (pinfunction "~{OE}_22") (pintype "input"))
      (node (ref "U7") (pin "E14") (pinfunction "MII1_RXD0_E14") (pintype "bidirectional"))
    )
    (net (code "60") (name "MAX4211-3V3") (class "Default")
      (node (ref "C34") (pin "1") (pinfunction "1_1") (pintype "passive"))
      (node (ref "TP56") (pin "1") (pinfunction "1_1") (pintype "passive"))
      (node (ref "U14") (pin "1") (pinfunction "VCC_1") (pintype "power_in"))
      (node (ref "U16") (pin "12") (pinfunction "IO7_12") (pintype "bidirectional"))
    )
    (net (code "61") (name "N$32") (class "Default")
      (node (ref "C18") (pin "1") (pinfunction "1_1") (pintype "passive"))
      (node (ref "JP104") (pin "1") (pinfunction "1_1") (pintype "passive"))
      (node (ref "TP14") (pin "P$1") (pinfunction "1_P$1") (pintype "bidirectional"))
      (node (ref "TP164") (pin "P$1") (pinfunction "1_P$1") (pintype "bidirectional"))
      (node (ref "U4") (pin "5") (pinfunction "VCC_5") (pintype "bidirectional"))
      (node (ref "U7") (pin "K11") (pinfunction "SYS_RTC_1P8V_K11") (pintype "power_in"))
      (node (ref "U7") (pin "L11") (pinfunction "SYS_RTC_1P8V_L11") (pintype "power_in"))
    )
    (net (code "62") (name "N$103") (class "Default")
      (node (ref "J4") (pin "1") (pinfunction "1_1") (pintype "passive"))
      (node (ref "J4") (pin "2") (pinfunction "2_2") (pintype "passive"))
      (node (ref "TP62") (pin "P$1") (pinfunction "1_P$1") (pintype "bidirectional"))
    )
    (net (code "63") (name "Net-(C33-Pad1)") (class "Default")
      (node (ref "C33") (pin "1") (pinfunction "1_1") (pintype "passive"))
      (node (ref "R33") (pin "2") (pinfunction "2_2") (pintype "passive"))
      (node (ref "R38") (pin "2") (pinfunction "2_2") (pintype "passive"))
    )
    (net (code "64") (name "Net-(D1-PadA)") (class "Default")
      (node (ref "D1") (pin "A") (pinfunction "A_A") (pintype "passive"))
      (node (ref "R1") (pin "2") (pinfunction "2_2") (pintype "passive"))
    )
    (net (code "65") (name "Net-(D2-PadA)") (class "Default")
      (node (ref "D2") (pin "A") (pinfunction "A_A") (pintype "passive"))
      (node (ref "R2") (pin "2") (pinfunction "2_2") (pintype "passive"))
    )
    (net (code "66") (name "Net-(D3-PadA)") (class "Default")
      (node (ref "D3") (pin "A") (pinfunction "A_A") (pintype "passive"))
      (node (ref "R3") (pin "2") (pinfunction "2_2") (pintype "passive"))
    )
    (net (code "67") (name "Net-(D4-PadA)") (class "Default")
      (node (ref "D4") (pin "A") (pinfunction "A_A") (pintype "passive"))
      (node (ref "R4") (pin "2") (pinfunction "2_2") (pintype "passive"))
    )
    (net (code "68") (name "Net-(D5-PadA)") (class "Default")
      (node (ref "D5") (pin "A") (pinfunction "A_A") (pintype "passive"))
      (node (ref "R5") (pin "2") (pinfunction "2_2") (pintype "passive"))
    )
    (net (code "69") (name "Net-(D6-PadA)") (class "Default")
      (node (ref "D6") (pin "A") (pinfunction "A_A") (pintype "passive"))
      (node (ref "R49") (pin "1") (pinfunction "1_1") (pintype "passive"))
    )
    (net (code "70") (name "Net-(D7-PadA)") (class "Default")
      (node (ref "D7") (pin "A") (pinfunction "A_A") (pintype "passive"))
      (node (ref "R61") (pin "1") (pinfunction "1_1") (pintype "passive"))
    )
    (net (code "71") (name "Net-(D8-PadA)") (class "Default")
      (node (ref "D8") (pin "A") (pinfunction "A_A") (pintype "passive"))
      (node (ref "R62") (pin "1") (pinfunction "1_1") (pintype "passive"))
    )
    (net (code "72") (name "Net-(J100-CD#)") (class "Default")
      (node (ref "J100") (pin "CD") (pinfunction "CD#_CD") (pintype "bidirectional"))
      (node (ref "R8") (pin "6") (pinfunction "66_6") (pintype "passive"))
      (node (ref "TP22") (pin "P$1") (pinfunction "1_P$1") (pintype "bidirectional"))
      (node (ref "U7") (pin "C14") (pinfunction "SPI0_CS1_C14") (pintype "bidirectional"))
    )
    (net (code "73") (name "Net-(J100-CLK)") (class "Default")
      (node (ref "J100") (pin "5") (pinfunction "CLK_5") (pintype "bidirectional"))
      (node (ref "R8") (pin "3") (pinfunction "33_3") (pintype "passive"))
      (node (ref "U7") (pin "B15") (pinfunction "MMC0_CLK_B15") (pintype "bidirectional"))
    )
    (net (code "74") (name "Net-(J100-CMD{slash}DI)") (class "Default")
      (node (ref "J100") (pin "3") (pinfunction "CMD/DI_3") (pintype "bidirectional"))
      (node (ref "R8") (pin "8") (pinfunction "88_8") (pintype "passive"))
      (node (ref "U7") (pin "B16") (pinfunction "MMC0_CMD_B16") (pintype "bidirectional"))
    )
    (net (code "75") (name "Net-(J100-DAT0{slash}DO)") (class "Default")
      (node (ref "J100") (pin "7") (pinfunction "DAT0/DO_7") (pintype "bidirectional"))
      (node (ref "JP111") (pin "3") (pinfunction "3_3") (pintype "passive"))
      (node (ref "R8") (pin "7") (pinfunction "77_7") (pintype "passive"))
    )
    (net (code "76") (name "Net-(J100-DAT1)") (class "Default")
      (node (ref "J100") (pin "8") (pinfunction "DAT1_8") (pintype "bidirectional"))
      (node (ref "JP110") (pin "3") (pinfunction "3_3") (pintype "passive"))
      (node (ref "R8") (pin "4") (pinfunction "44_4") (pintype "passive"))
    )
    (net (code "77") (name "Net-(J100-DAT2)") (class "Default")
      (node (ref "J100") (pin "1") (pinfunction "DAT2_1") (pintype "bidirectional"))
      (node (ref "JP103") (pin "3") (pinfunction "3_3") (pintype "passive"))
      (node (ref "R8") (pin "9") (pinfunction "99_9") (pintype "passive"))
    )
    (net (code "78") (name "Net-(J100-DAT3{slash}CS)") (class "Default")
      (node (ref "J100") (pin "2") (pinfunction "DAT3/CS_2") (pintype "bidirectional"))
      (node (ref "JP102") (pin "3") (pinfunction "3_3") (pintype "passive"))
      (node (ref "R8") (pin "2") (pinfunction "22_2") (pintype "passive"))
    )
    (net (code "79") (name "Net-(J102-NC{slash}TDI)") (class "Default")
      (node (ref "J102") (pin "8") (pinfunction "NC/TDI_8") (pintype "passive"))
      (node (ref "U7") (pin "C1") (pinfunction "TDI_C1") (pintype "bidirectional"))
    )
    (net (code "80") (name "Net-(J102-SWDCLK{slash}TCK)") (class "Default")
      (node (ref "J102") (pin "4") (pinfunction "SWDCLK/TCK_4") (pintype "passive"))
      (node (ref "U7") (pin "D1") (pinfunction "TCK_D1") (pintype "bidirectional"))
    )
    (net (code "81") (name "Net-(J102-SWDIO{slash}TMS)") (class "Default")
      (node (ref "J102") (pin "2") (pinfunction "SWDIO/TMS_2") (pintype "passive"))
      (node (ref "U7") (pin "D2") (pinfunction "TMS_D2") (pintype "bidirectional"))
    )
    (net (code "82") (name "Net-(J102-SWO{slash}TDO)") (class "Default")
      (node (ref "J102") (pin "6") (pinfunction "SWO/TDO_6") (pintype "passive"))
      (node (ref "U7") (pin "C2") (pinfunction "TDO_C2") (pintype "bidirectional"))
    )
    (net (code "83") (name "Net-(J102-~{RESET})") (class "Default")
      (node (ref "J102") (pin "10") (pinfunction "~{RESET}_10") (pintype "passive"))
      (node (ref "R19") (pin "2") (pinfunction "2_2") (pintype "passive"))
      (node (ref "U7") (pin "D3") (pinfunction "TRSTN_D3") (pintype "bidirectional"))
    )
    (net (code "84") (name "Net-(JP101-Pad2)") (class "Default")
      (node (ref "JP101") (pin "2") (pinfunction "2_2") (pintype "passive"))
      (node (ref "Q1") (pin "E") (pinfunction "E_E") (pintype "passive"))
      (node (ref "R23") (pin "2") (pinfunction "2_2") (pintype "passive"))
      (node (ref "R28") (pin "2") (pinfunction "2_2") (pintype "passive"))
    )
    (net (code "85") (name "Net-(L1-Pad1)") (class "Default")
      (node (ref "L1") (pin "1") (pinfunction "1_1") (pintype "passive"))
      (node (ref "U15") (pin "14") (pinfunction "SW_14") (pintype "output"))
      (node (ref "U15") (pin "15") (pinfunction "SW_15") (pintype "output"))
    )
    (net (code "86") (name "Net-(Q3A-G)") (class "Default")
      (node (ref "Q3") (pin "1") (pinfunction "G_1") (pintype "passive"))
      (node (ref "R35") (pin "2") (pinfunction "2_2") (pintype "passive"))
      (node (ref "TP44") (pin "1") (pinfunction "1_1") (pintype "passive"))
      (node (ref "U12") (pin "4") (pinfunction "OUT_4") (pintype "output"))
    )
    (net (code "87") (name "Net-(Q3A-S)") (class "Default")
      (node (ref "Q3") (pin "5") (pinfunction "S_5") (pintype "passive"))
      (node (ref "R48") (pin "2") (pinfunction "2_2") (pintype "passive"))
    )
    (net (code "88") (name "Net-(Q3B-G)") (class "Default")
      (node (ref "Q3") (pin "3") (pinfunction "G_3") (pintype "passive"))
      (node (ref "R43") (pin "2") (pinfunction "2_2") (pintype "passive"))
      (node (ref "TP43") (pin "1") (pinfunction "1_1") (pintype "passive"))
      (node (ref "U13") (pin "4") (pinfunction "OUT_4") (pintype "output"))
    )
    (net (code "89") (name "Net-(Q3B-S)") (class "Default")
      (node (ref "Q3") (pin "2") (pinfunction "S_2") (pintype "passive"))
      (node (ref "R41") (pin "2") (pinfunction "2_2") (pintype "passive"))
    )
    (net (code "90") (name "Net-(Q4-D)") (class "Default")
      (node (ref "Q4") (pin "3") (pinfunction "D_3") (pintype "passive"))
      (node (ref "Q6") (pin "3") (pinfunction "G_3") (pintype "passive"))
      (node (ref "R52") (pin "1") (pinfunction "1_1") (pintype "passive"))
    )
    (net (code "91") (name "Net-(Q5-S)") (class "Default")
      (node (ref "Q5") (pin "4") (pinfunction "S_4") (pintype "passive"))
      (node (ref "R63") (pin "2") (pinfunction "2_2") (pintype "passive"))
      (node (ref "R64") (pin "2") (pinfunction "2_2") (pintype "passive"))
      (node (ref "U14") (pin "15") (pinfunction "RS-_15") (pintype "passive"))
    )
    (net (code "92") (name "Net-(R9-22)") (class "Default")
      (node (ref "R9") (pin "2") (pinfunction "22_2") (pintype "passive"))
      (node (ref "U3") (pin "M5") (pinfunction "CMD_M5") (pintype "input"))
      (node (ref "U7") (pin "P1") (pinfunction "GPMC_CSN2_P1") (pintype "bidirectional"))
    )
    (net (code "93") (name "Net-(R9-33)") (class "Default")
      (node (ref "R9") (pin "3") (pinfunction "33_3") (pintype "passive"))
      (node (ref "U3") (pin "B4") (pinfunction "D5_B4") (pintype "input"))
      (node (ref "U7") (pin "T1") (pinfunction "GPMC_AD5_T1") (pintype "bidirectional"))
    )
    (net (code "94") (name "Net-(R9-44)") (class "Default")
      (node (ref "R9") (pin "4") (pinfunction "44_4") (pintype "passive"))
      (node (ref "U3") (pin "B3") (pinfunction "D4_B3") (pintype "input"))
      (node (ref "U7") (pin "T2") (pinfunction "GPMC_AD4_T2") (pintype "bidirectional"))
    )
    (net (code "95") (name "Net-(R9-66)") (class "Default")
      (node (ref "R9") (pin "6") (pinfunction "66_6") (pintype "passive"))
      (node (ref "U3") (pin "A3") (pinfunction "D0_A3") (pintype "input"))
      (node (ref "U7") (pin "R3") (pinfunction "GPMC_AD0_R3") (pintype "bidirectional"))
    )
    (net (code "96") (name "Net-(R9-77)") (class "Default")
      (node (ref "R9") (pin "7") (pinfunction "77_7") (pintype "passive"))
      (node (ref "U3") (pin "B2") (pinfunction "D3_B2") (pintype "input"))
      (node (ref "U7") (pin "T3") (pinfunction "GPMC_AD3_T3") (pintype "bidirectional"))
    )
    (net (code "97") (name "Net-(R9-88)") (class "Default")
      (node (ref "R9") (pin "8") (pinfunction "88_8") (pintype "passive"))
      (node (ref "U3") (pin "M6") (pinfunction "SCK_M6") (pintype "input"))
      (node (ref "U7") (pin "P2") (pinfunction "GPMC_CSN1_P2") (pintype "bidirectional"))
    )
    (net (code "98") (name "Net-(R10-11)") (class "Default")
      (node (ref "R10") (pin "1") (pinfunction "11_1") (pintype "passive"))
      (node (ref "U3") (pin "A4") (pinfunction "D1_A4") (pintype "input"))
      (node (ref "U7") (pin "R2") (pinfunction "GPMC_AD1_R2") (pintype "bidirectional"))
    )
    (net (code "99") (name "Net-(R10-22)") (class "Default")
      (node (ref "R10") (pin "2") (pinfunction "22_2") (pintype "passive"))
      (node (ref "U3") (pin "B6") (pinfunction "D7_B6") (pintype "input"))
      (node (ref "U7") (pin "R4") (pinfunction "GPMC_AD7_R4") (pintype "bidirectional"))
    )
    (net (code "100") (name "Net-(R10-33)") (class "Default")
      (node (ref "R10") (pin "3") (pinfunction "33_3") (pintype "passive"))
      (node (ref "U3") (pin "K5") (pinfunction "~{RST}_K5") (pintype "input"))
      (node (ref "U7") (pin "R13") (pinfunction "GPMC_A4_R13") (pintype "bidirectional"))
    )
    (net (code "101") (name "Net-(R10-88)") (class "Default")
      (node (ref "R10") (pin "8") (pinfunction "88_8") (pintype "passive"))
      (node (ref "U3") (pin "B5") (pinfunction "D6_B5") (pintype "bidirectional"))
      (node (ref "U7") (pin "P4") (pinfunction "GPMC_AD6_P4") (pintype "bidirectional"))
    )
    (net (code "102") (name "Net-(R10-99)") (class "Default")
      (node (ref "R10") (pin "9") (pinfunction "99_9") (pintype "passive"))
      (node (ref "U3") (pin "A5") (pinfunction "D2_A5") (pintype "input"))
      (node (ref "U7") (pin "R1") (pinfunction "GPMC_AD2_R1") (pintype "bidirectional"))
    )
    (net (code "103") (name "Net-(R24-22)") (class "Default")
      (node (ref "JP106") (pin "1") (pinfunction "1_1") (pintype "passive"))
      (node (ref "R24") (pin "2") (pinfunction "22_2") (pintype "passive"))
    )
    (net (code "104") (name "Net-(R24-33)") (class "Default")
      (node (ref "JP108") (pin "3") (pinfunction "3_3") (pintype "passive"))
      (node (ref "R24") (pin "3") (pinfunction "33_3") (pintype "passive"))
    )
    (net (code "105") (name "Net-(R24-44)") (class "Default")
      (node (ref "R24") (pin "4") (pinfunction "44_4") (pintype "passive"))
      (node (ref "U7") (pin "L1") (pinfunction "LCD_DATA14_L1") (pintype "bidirectional"))
    )
    (net (code "106") (name "Net-(R24-66)") (class "Default")
      (node (ref "JP109") (pin "3") (pinfunction "3_3") (pintype "passive"))
      (node (ref "R24") (pin "6") (pinfunction "66_6") (pintype "passive"))
    )
    (net (code "107") (name "Net-(R24-88)") (class "Default")
      (node (ref "J3") (pin "1") (pinfunction "1_1") (pintype "passive"))
      (node (ref "JP107") (pin "1") (pinfunction "1_1") (pintype "passive"))
      (node (ref "R24") (pin "8") (pinfunction "88_8") (pintype "passive"))
    )
    (net (code "108") (name "Net-(R24-99)") (class "Default")
      (node (ref "JP105") (pin "1") (pinfunction "1_1") (pintype "passive"))
      (node (ref "R24") (pin "9") (pinfunction "99_9") (pintype "passive"))
    )
    (net (code "109") (name "Net-(R25-11)") (class "Default")
      (node (ref "J3") (pin "3") (pinfunction "3_3") (pintype "passive"))
      (node (ref "JP107") (pin "3") (pinfunction "3_3") (pintype "passive"))
      (node (ref "R25") (pin "1") (pinfunction "11_1") (pintype "passive"))
    )
    (net (code "110") (name "Net-(R25-22)") (class "Default")
      (node (ref "JP106") (pin "3") (pinfunction "3_3") (pintype "passive"))
      (node (ref "R25") (pin "2") (pinfunction "22_2") (pintype "passive"))
    )
    (net (code "111") (name "Net-(R25-33)") (class "Default")
      (node (ref "JP105") (pin "3") (pinfunction "3_3") (pintype "passive"))
      (node (ref "R25") (pin "3") (pinfunction "33_3") (pintype "passive"))
    )
    (net (code "112") (name "Net-(R25-44)") (class "Default")
      (node (ref "R25") (pin "4") (pinfunction "44_4") (pintype "passive"))
      (node (ref "U7") (pin "H1") (pinfunction "LCD_DATA5_H1") (pintype "bidirectional"))
    )
    (net (code "113") (name "Net-(R25-66)") (class "Default")
      (node (ref "JP109") (pin "1") (pinfunction "1_1") (pintype "passive"))
      (node (ref "R25") (pin "6") (pinfunction "66_6") (pintype "passive"))
    )
    (net (code "114") (name "Net-(R25-77)") (class "Default")
      (node (ref "R25") (pin "7") (pinfunction "77_7") (pintype "passive"))
      (node (ref "U7") (pin "J3") (pinfunction "LCD_DATA6_J3") (pintype "bidirectional"))
    )
    (net (code "115") (name "Net-(R25-99)") (class "Default")
      (node (ref "JP108") (pin "1") (pinfunction "1_1") (pintype "passive"))
      (node (ref "R25") (pin "9") (pinfunction "99_9") (pintype "passive"))
    )
    (net (code "116") (name "Net-(R26-11)") (class "Default")
      (node (ref "R26") (pin "1") (pinfunction "11_1") (pintype "passive"))
      (node (ref "U7") (pin "M3") (pinfunction "LCD_DATA15_M3") (pintype "bidirectional"))
    )
    (net (code "117") (name "Net-(R26-22)") (class "Default")
      (node (ref "R26") (pin "2") (pinfunction "22_2") (pintype "passive"))
      (node (ref "U7") (pin "L3") (pinfunction "LCD_DATA12_L3") (pintype "bidirectional"))
    )
    (net (code "118") (name "Net-(R26-33)") (class "Default")
      (node (ref "R26") (pin "3") (pinfunction "33_3") (pintype "passive"))
      (node (ref "U7") (pin "K2") (pinfunction "LCD_DATA10_K2") (pintype "bidirectional"))
    )
    (net (code "119") (name "Net-(R26-44)") (class "Default")
      (node (ref "R26") (pin "4") (pinfunction "44_4") (pintype "passive"))
      (node (ref "U7") (pin "J1") (pinfunction "LCD_DATA8_J1") (pintype "bidirectional"))
    )
    (net (code "120") (name "Net-(R26-66)") (class "Default")
      (node (ref "R26") (pin "6") (pinfunction "66_6") (pintype "passive"))
      (node (ref "U7") (pin "J2") (pinfunction "LCD_DATA7_J2") (pintype "bidirectional"))
    )
    (net (code "121") (name "Net-(R26-77)") (class "Default")
      (node (ref "R26") (pin "7") (pinfunction "77_7") (pintype "passive"))
      (node (ref "U7") (pin "K3") (pinfunction "LCD_DATA9_K3") (pintype "bidirectional"))
    )
    (net (code "122") (name "Net-(R26-88)") (class "Default")
      (node (ref "R26") (pin "8") (pinfunction "88_8") (pintype "passive"))
      (node (ref "U7") (pin "K1") (pinfunction "LCD_DATA11_K1") (pintype "bidirectional"))
    )
    (net (code "123") (name "Net-(R26-99)") (class "Default")
      (node (ref "R26") (pin "9") (pinfunction "99_9") (pintype "passive"))
      (node (ref "U7") (pin "L2") (pinfunction "LCD_DATA13_L2") (pintype "bidirectional"))
    )
    (net (code "124") (name "Net-(TP30-1)") (class "Default")
      (node (ref "TP30") (pin "P$1") (pinfunction "1_P$1") (pintype "bidirectional"))
      (node (ref "U7") (pin "A4") (pinfunction "XDMA_EVENT_INTR0_A4") (pintype "bidirectional"))
    )
    (net (code "125") (name "Net-(TP31-1)") (class "Default")
      (node (ref "TP31") (pin "P$1") (pinfunction "1_P$1") (pintype "bidirectional"))
      (node (ref "U7") (pin "B13") (pinfunction "SPI0_D0_B13") (pintype "bidirectional"))
    )
    (net (code "126") (name "Net-(TP32-1)") (class "Default")
      (node (ref "TP32") (pin "P$1") (pinfunction "1_P$1") (pintype "bidirectional"))
      (node (ref "U7") (pin "B14") (pinfunction "SPI0_D1_B14") (pintype "bidirectional"))
    )
    (net (code "127") (name "Net-(TP33-1)") (class "Default")
      (node (ref "TP33") (pin "P$1") (pinfunction "1_P$1") (pintype "bidirectional"))
      (node (ref "U7") (pin "A13") (pinfunction "SPI0_SCLK_A13") (pintype "bidirectional"))
    )
    (net (code "128") (name "Net-(TP34-1)") (class "Default")
      (node (ref "TP34") (pin "P$1") (pinfunction "1_P$1") (pintype "bidirectional"))
      (node (ref "U7") (pin "A14") (pinfunction "SPI0_CS0_A14") (pintype "bidirectional"))
    )
    (net (code "129") (name "Net-(TP35-1)") (class "Default")
      (node (ref "TP35") (pin "P$1") (pinfunction "1_P$1") (pintype "bidirectional"))
      (node (ref "U11") (pin "5") (pinfunction "SHDN_5") (pintype "input"))
    )
    (net (code "130") (name "Net-(TP38-1)") (class "Default")
      (node (ref "TP38") (pin "P$1") (pinfunction "1_P$1") (pintype "bidirectional"))
      (node (ref "U7") (pin "B8") (pinfunction "AIN1_B8") (pintype "bidirectional"))
    )
    (net (code "131") (name "Net-(TP39-1)") (class "Default")
      (node (ref "TP39") (pin "P$1") (pinfunction "1_P$1") (pintype "bidirectional"))
      (node (ref "U7") (pin "A8") (pinfunction "AIN0_A8") (pintype "bidirectional"))
    )
    (net (code "132") (name "Net-(TP40-1)") (class "Default")
      (node (ref "TP40") (pin "P$1") (pinfunction "1_P$1") (pintype "bidirectional"))
      (node (ref "U11") (pin "8") (pinfunction "S_8") (pintype "input"))
    )
    (net (code "133") (name "Net-(TP100-1)") (class "Default")
      (node (ref "TP100") (pin "P$1") (pinfunction "1_P$1") (pintype "bidirectional"))
      (node (ref "U7") (pin "T12") (pinfunction "GPMC_A0_T12") (pintype "bidirectional"))
    )
    (net (code "134") (name "Net-(TP101-1)") (class "Default")
      (node (ref "TP101") (pin "P$1") (pinfunction "1_P$1") (pintype "bidirectional"))
      (node (ref "U7") (pin "T13") (pinfunction "GPMC_A3_T13") (pintype "bidirectional"))
    )
    (net (code "135") (name "Net-(TP102-1)") (class "Default")
      (node (ref "TP102") (pin "P$1") (pinfunction "1_P$1") (pintype "bidirectional"))
      (node (ref "U7") (pin "T11") (pinfunction "PMIC_PB_IN_T11") (pintype "bidirectional"))
    )
    (net (code "136") (name "Net-(TP103-1)") (class "Default")
      (node (ref "TP103") (pin "P$1") (pinfunction "1_P$1") (pintype "bidirectional"))
      (node (ref "U7") (pin "T16") (pinfunction "GPMC_A11_T16") (pintype "bidirectional"))
    )
    (net (code "137") (name "Net-(TP104-1)") (class "Default")
      (node (ref "TP104") (pin "P$1") (pinfunction "1_P$1") (pintype "bidirectional"))
      (node (ref "U7") (pin "T4") (pinfunction "GPMC_AD8_T4") (pintype "bidirectional"))
    )
    (net (code "138") (name "Net-(TP105-1)") (class "Default")
      (node (ref "TP105") (pin "P$1") (pinfunction "1_P$1") (pintype "bidirectional"))
      (node (ref "U7") (pin "T5") (pinfunction "GPMC_AD11_T5") (pintype "bidirectional"))
    )
    (net (code "139") (name "Net-(TP106-1)") (class "Default")
      (node (ref "TP106") (pin "P$1") (pinfunction "1_P$1") (pintype "bidirectional"))
      (node (ref "U7") (pin "T7") (pinfunction "GPMC_CLK_T7") (pintype "bidirectional"))
    )
    (net (code "140") (name "Net-(TP107-1)") (class "Default")
      (node (ref "TP107") (pin "P$1") (pinfunction "1_P$1") (pintype "bidirectional"))
      (node (ref "U7") (pin "R7") (pinfunction "GPMC_CSN3_R7") (pintype "bidirectional"))
    )
    (net (code "141") (name "Net-(TP108-1)") (class "Default")
      (node (ref "TP108") (pin "P$1") (pinfunction "1_P$1") (pintype "bidirectional"))
      (node (ref "U7") (pin "T15") (pinfunction "GPMC_A9_T15") (pintype "bidirectional"))
    )
    (net (code "142") (name "Net-(TP111-1)") (class "Default")
      (node (ref "TP111") (pin "P$1") (pinfunction "1_P$1") (pintype "bidirectional"))
      (node (ref "U7") (pin "R16") (pinfunction "GPMC_WPN_R16") (pintype "bidirectional"))
    )
    (net (code "143") (name "Net-(TP114-1)") (class "Default")
      (node (ref "TP114") (pin "P$1") (pinfunction "1_P$1") (pintype "bidirectional"))
      (node (ref "U7") (pin "P15") (pinfunction "GPMC_WAIT0_P15") (pintype "bidirectional"))
    )
    (net (code "144") (name "Net-(TP115-1)") (class "Default")
      (node (ref "TP115") (pin "P$1") (pinfunction "1_P$1") (pintype "bidirectional"))
      (node (ref "U7") (pin "R5") (pinfunction "GPMC_AD10_R5") (pintype "bidirectional"))
    )
    (net (code "145") (name "Net-(TP117-1)") (class "Default")
      (node (ref "TP117") (pin "P$1") (pinfunction "1_P$1") (pintype "bidirectional"))
      (node (ref "U7") (pin "R15") (pinfunction "GPMC_A10_R15") (pintype "bidirectional"))
    )
    (net (code "146") (name "Net-(TP118-1)") (class "Default")
      (node (ref "TP118") (pin "P$1") (pinfunction "1_P$1") (pintype "bidirectional"))
      (node (ref "U7") (pin "R12") (pinfunction "GPMC_A1_R12") (pintype "bidirectional"))
    )
    (net (code "147") (name "Net-(TP120-1)") (class "Default")
      (node (ref "TP120") (pin "P$1") (pinfunction "1_P$1") (pintype "bidirectional"))
      (node (ref "U7") (pin "R6") (pinfunction "GPMC_AD13_R6") (pintype "bidirectional"))
    )
    (net (code "148") (name "Net-(TP121-1)") (class "Default")
      (node (ref "TP121") (pin "P$1") (pinfunction "1_P$1") (pintype "bidirectional"))
      (node (ref "U7") (pin "N10") (pinfunction "PMIC_POWER_EN_N10") (pintype "output"))
      (node (ref "U7") (pin "N11") (pinfunction "PMIC_PWR_EN_N11") (pintype "input"))
    )
    (net (code "149") (name "Net-(TP122-1)") (class "Default")
      (node (ref "TP122") (pin "P$1") (pinfunction "1_P$1") (pintype "bidirectional"))
      (node (ref "U7") (pin "P3") (pinfunction "GPMC_CSN0_P3") (pintype "bidirectional"))
    )
    (net (code "150") (name "Net-(TP123-1)") (class "Default")
      (node (ref "TP123") (pin "P$1") (pinfunction "1_P$1") (pintype "bidirectional"))
      (node (ref "U7") (pin "P5") (pinfunction "GPMC_AD9_P5") (pintype "bidirectional"))
    )
    (net (code "151") (name "Net-(TP124-1)") (class "Default")
      (node (ref "TP124") (pin "P$1") (pinfunction "1_P$1") (pintype "bidirectional"))
      (node (ref "U7") (pin "P6") (pinfunction "GPMC_AD12_P6") (pintype "bidirectional"))
    )
    (net (code "152") (name "Net-(TP125-1)") (class "Default")
      (node (ref "TP125") (pin "P$1") (pinfunction "1_P$1") (pintype "bidirectional"))
      (node (ref "U7") (pin "N14") (pinfunction "GPMC_BEN1_N14") (pintype "bidirectional"))
    )
    (net (code "153") (name "Net-(TP126-1)") (class "Default")
      (node (ref "TP126") (pin "P$1") (pinfunction "1_P$1") (pintype "bidirectional"))
      (node (ref "U7") (pin "P12") (pinfunction "GPMC_A2_P12") (pintype "bidirectional"))
    )
    (net (code "154") (name "Net-(TP127-1)") (class "Default")
      (node (ref "TP127") (pin "P$1") (pinfunction "1_P$1") (pintype "bidirectional"))
      (node (ref "U7") (pin "N2") (pinfunction "GPMC_WEN_N2") (pintype "bidirectional"))
    )
    (net (code "155") (name "Net-(TP128-1)") (class "Default")
      (node (ref "TP128") (pin "P$1") (pinfunction "1_P$1") (pintype "bidirectional"))
      (node (ref "U7") (pin "N1") (pinfunction "GPMC_OEN_REN_N1") (pintype "bidirectional"))
    )
    (net (code "156") (name "Net-(TP129-1)") (class "Default")
      (node (ref "TP129") (pin "P$1") (pinfunction "1_P$1") (pintype "bidirectional"))
      (node (ref "U7") (pin "N6") (pinfunction "PMIC_TS_N6") (pintype "bidirectional"))
    )
    (net (code "157") (name "Net-(TP130-1)") (class "Default")
      (node (ref "TP130") (pin "P$1") (pinfunction "1_P$1") (pintype "bidirectional"))
      (node (ref "TP4") (pin "P$1") (pinfunction "1_P$1") (pintype "bidirectional"))
      (node (ref "U7") (pin "N7") (pinfunction "PMIC_BAT_SENSE_N7") (pintype "bidirectional"))
      (node (ref "U7") (pin "P8") (pinfunction "VIN_BAT_P8") (pintype "power_in"))
      (node (ref "U7") (pin "R8") (pinfunction "VIN_BAT_R8") (pintype "power_in"))
      (node (ref "U7") (pin "T8") (pinfunction "VIN_BAT_T8") (pintype "power_in"))
    )
    (net (code "158") (name "Net-(TP131-1)") (class "Default")
      (node (ref "TP131") (pin "P$1") (pinfunction "1_P$1") (pintype "bidirectional"))
      (node (ref "U7") (pin "N3") (pinfunction "GPMC_BEN0_CLE_N3") (pintype "bidirectional"))
    )
    (net (code "159") (name "Net-(TP132-1)") (class "Default")
      (node (ref "TP132") (pin "P$1") (pinfunction "1_P$1") (pintype "bidirectional"))
      (node (ref "U7") (pin "N4") (pinfunction "PMIC_LDO_PGOOD_N4") (pintype "output"))
      (node (ref "U7") (pin "N5") (pinfunction "RTC_PWRONRSTN_N5") (pintype "bidirectional"))
    )
    (net (code "160") (name "Net-(TP133-1)") (class "Default")
      (node (ref "TP133") (pin "P$1") (pinfunction "1_P$1") (pintype "bidirectional"))
      (node (ref "U7") (pin "N13") (pinfunction "PMIC_MUX_IN_N13") (pintype "bidirectional"))
    )
    (net (code "161") (name "Net-(TP134-1)") (class "Default")
      (node (ref "TP134") (pin "P$1") (pinfunction "1_P$1") (pintype "bidirectional"))
      (node (ref "U7") (pin "M1") (pinfunction "GPMC_ADVN_ALE_M1") (pintype "bidirectional"))
    )
    (net (code "162") (name "Net-(TP135-1)") (class "Default")
      (node (ref "TP135") (pin "P$1") (pinfunction "1_P$1") (pintype "bidirectional"))
      (node (ref "U7") (pin "G16") (pinfunction "MII1_TXD2_G16") (pintype "bidirectional"))
    )
    (net (code "163") (name "Net-(TP136-1)") (class "Default")
      (node (ref "TP136") (pin "P$1") (pinfunction "1_P$1") (pintype "bidirectional"))
      (node (ref "U7") (pin "M13") (pinfunction "PMIC_NRESET_M13") (pintype "bidirectional"))
    )
    (net (code "164") (name "Net-(TP137-1)") (class "Default")
      (node (ref "TP137") (pin "P$1") (pinfunction "1_P$1") (pintype "bidirectional"))
      (node (ref "U7") (pin "H15") (pinfunction "MII1_TXD0_H15") (pintype "bidirectional"))
    )
    (net (code "165") (name "Net-(TP138-1)") (class "Default")
      (node (ref "TP138") (pin "P$1") (pinfunction "1_P$1") (pintype "bidirectional"))
      (node (ref "U7") (pin "K14") (pinfunction "USB0_ID_K14") (pintype "bidirectional"))
    )
    (net (code "166") (name "Net-(TP139-1)") (class "Default")
      (node (ref "TP139") (pin "P$1") (pinfunction "1_P$1") (pintype "bidirectional"))
      (node (ref "U7") (pin "J15") (pinfunction "USB0_DRVVBUS_J15") (pintype "bidirectional"))
    )
    (net (code "167") (name "Net-(TP140-1)") (class "Default")
      (node (ref "TP140") (pin "P$1") (pinfunction "1_P$1") (pintype "bidirectional"))
      (node (ref "U7") (pin "L4") (pinfunction "PMIC_NWAKEUP_L4") (pintype "output"))
      (node (ref "U7") (pin "M4") (pinfunction "EXT_WAKEUP_M4") (pintype "bidirectional"))
    )
    (net (code "168") (name "Net-(TP141-1)") (class "Default")
      (node (ref "TP141") (pin "P$1") (pinfunction "1_P$1") (pintype "bidirectional"))
      (node (ref "U7") (pin "K13") (pinfunction "USB0_CE_K13") (pintype "bidirectional"))
    )
    (net (code "169") (name "Net-(TP143-1)") (class "Default")
      (node (ref "TP143") (pin "P$1") (pinfunction "1_P$1") (pintype "bidirectional"))
      (node (ref "U7") (pin "J14") (pinfunction "RMII1_REF_CLK_J14") (pintype "bidirectional"))
    )
    (net (code "170") (name "Net-(TP144-1)") (class "Default")
      (node (ref "TP144") (pin "P$1") (pinfunction "1_P$1") (pintype "bidirectional"))
      (node (ref "U7") (pin "L13") (pinfunction "USB1_CE_L13") (pintype "bidirectional"))
    )
    (net (code "171") (name "Net-(TP145-1)") (class "Default")
      (node (ref "TP145") (pin "P$1") (pinfunction "1_P$1") (pintype "bidirectional"))
      (node (ref "U7") (pin "K4") (pinfunction "NC_K4") (pintype "bidirectional"))
    )
    (net (code "172") (name "Net-(TP147-1)") (class "Default")
      (node (ref "TP147") (pin "P$1") (pinfunction "1_P$1") (pintype "bidirectional"))
      (node (ref "U7") (pin "H16") (pinfunction "MII1_TX_CLK_H16") (pintype "bidirectional"))
    )
    (net (code "173") (name "Net-(TP148-1)") (class "Default")
      (node (ref "TP148") (pin "P$1") (pinfunction "1_P$1") (pintype "bidirectional"))
      (node (ref "U7") (pin "G14") (pinfunction "MII1_TX_EN_G14") (pintype "bidirectional"))
    )
    (net (code "174") (name "Net-(TP149-1)") (class "Default")
      (node (ref "TP149") (pin "P$1") (pinfunction "1_P$1") (pintype "bidirectional"))
      (node (ref "U7") (pin "H14") (pinfunction "MII1_TXD1_H14") (pintype "bidirectional"))
    )
    (net (code "175") (name "Net-(TP150-1)") (class "Default")
      (node (ref "TP150") (pin "P$1") (pinfunction "1_P$1") (pintype "bidirectional"))
      (node (ref "U7") (pin "J6") (pinfunction "NC_J6") (pintype "bidirectional"))
    )
    (net (code "176") (name "Net-(TP152-1)") (class "Default")
      (node (ref "TP152") (pin "P$1") (pinfunction "1_P$1") (pintype "bidirectional"))
      (node (ref "U7") (pin "F2") (pinfunction "LCD_HSYNC_F2") (pintype "bidirectional"))
    )
    (net (code "177") (name "Net-(TP153-1)") (class "Default")
      (node (ref "TP153") (pin "P$1") (pinfunction "1_P$1") (pintype "bidirectional"))
      (node (ref "U7") (pin "F3") (pinfunction "LCD_VSYNC_F3") (pintype "bidirectional"))
    )
    (net (code "178") (name "Net-(TP154-1)") (class "Default")
      (node (ref "TP154") (pin "P$1") (pinfunction "1_P$1") (pintype "bidirectional"))
      (node (ref "U7") (pin "G4") (pinfunction "VDD_CORE_G4") (pintype "bidirectional"))
    )
    (net (code "179") (name "Net-(TP156-1)") (class "Default")
      (node (ref "TP156") (pin "P$1") (pinfunction "1_P$1") (pintype "bidirectional"))
      (node (ref "U7") (pin "F4") (pinfunction "VDDS_DDR_F4") (pintype "bidirectional"))
    )
    (net (code "180") (name "Net-(TP157-1)") (class "Default")
      (node (ref "TP157") (pin "P$1") (pinfunction "1_P$1") (pintype "bidirectional"))
      (node (ref "U7") (pin "H6") (pinfunction "VPP_H6") (pintype "bidirectional"))
    )
    (net (code "181") (name "Net-(TP158-1)") (class "Default")
      (node (ref "TP158") (pin "P$1") (pinfunction "1_P$1") (pintype "bidirectional"))
      (node (ref "U7") (pin "E13") (pinfunction "MDIO_E13") (pintype "bidirectional"))
    )
    (net (code "182") (name "Net-(TP159-1)") (class "Default")
      (node (ref "TP159") (pin "P$1") (pinfunction "1_P$1") (pintype "bidirectional"))
      (node (ref "U7") (pin "E1") (pinfunction "LCD_AC_BIAS_EN_E1") (pintype "bidirectional"))
    )
    (net (code "183") (name "Net-(TP160-1)") (class "Default")
      (node (ref "TP160") (pin "P$1") (pinfunction "1_P$1") (pintype "bidirectional"))
      (node (ref "U7") (pin "F13") (pinfunction "VDD_MPU_F13") (pintype "bidirectional"))
    )
    (net (code "184") (name "Net-(TP161-1)") (class "Default")
      (node (ref "TP161") (pin "P$1") (pinfunction "1_P$1") (pintype "bidirectional"))
      (node (ref "U7") (pin "F11") (pinfunction "SYS_VDD2_3P3V_F11") (pintype "power_in"))
      (node (ref "U7") (pin "G11") (pinfunction "SYS_VDD2_3P3V_G11") (pintype "power_in"))
    )
    (net (code "185") (name "Net-(TP162-1)") (class "Default")
      (node (ref "TP162") (pin "P$1") (pinfunction "1_P$1") (pintype "bidirectional"))
      (node (ref "U7") (pin "F1") (pinfunction "LCD_PCLK_F1") (pintype "bidirectional"))
    )
    (net (code "186") (name "Net-(TP163-1)") (class "Default")
      (node (ref "TP163") (pin "P$1") (pinfunction "1_P$1") (pintype "bidirectional"))
      (node (ref "U7") (pin "F10") (pinfunction "SYS_VDD_1P8V_F10") (pintype "power_in"))
      (node (ref "U7") (pin "G10") (pinfunction "SYS_VDD_1P8V_G10") (pintype "power_in"))
      (node (ref "U7") (pin "H10") (pinfunction "SYS_VDD_1P8V_H10") (pintype "power_in"))
      (node (ref "U7") (pin "H11") (pinfunction "SYS_VDD_1P8V_H11") (pintype "power_in"))
      (node (ref "U7") (pin "J10") (pinfunction "SYS_VDD_1P8V_J10") (pintype "power_in"))
      (node (ref "U7") (pin "J11") (pinfunction "SYS_VDD_1P8V_J11") (pintype "power_in"))
      (node (ref "U7") (pin "K10") (pinfunction "SYS_VDD_1P8V_K10") (pintype "power_in"))
      (node (ref "U7") (pin "L10") (pinfunction "SYS_VDD_1P8V_L10") (pintype "power_in"))
    )
    (net (code "187") (name "Net-(TP165-1)") (class "Default")
      (node (ref "JP101") (pin "1") (pinfunction "1_1") (pintype "passive"))
      (node (ref "TP165") (pin "P$1") (pinfunction "1_P$1") (pintype "bidirectional"))
      (node (ref "U7") (pin "F8") (pinfunction "SYS_VDD3_3P3V_F8") (pintype "power_in"))
      (node (ref "U7") (pin "F9") (pinfunction "VDDSHV4_F9") (pintype "power_in"))
      (node (ref "U7") (pin "G8") (pinfunction "SYS_VDD3_3P3V_G8") (pintype "power_in"))
      (node (ref "U7") (pin "G9") (pinfunction "VDDSHV5_G9") (pintype "power_in"))
      (node (ref "U7") (pin "H7") (pinfunction "SYS_VDD3_3P3V_H7") (pintype "power_in"))
      (node (ref "U7") (pin "H8") (pinfunction "SYS_VDD3_3P3V_H8") (pintype "power_in"))
      (node (ref "U7") (pin "H9") (pinfunction "VDDSHV6_H9") (pintype "power_in"))
      (node (ref "U7") (pin "J7") (pinfunction "SYS_VDD3_3P3V_J7") (pintype "power_in"))
      (node (ref "U7") (pin "J8") (pinfunction "SYS_VDD3_3P3V_J8") (pintype "power_in"))
      (node (ref "U7") (pin "J9") (pinfunction "VDDSHV1_J9") (pintype "power_in"))
      (node (ref "U7") (pin "K8") (pinfunction "SYS_VDD3_3P3V_K8") (pintype "power_in"))
      (node (ref "U7") (pin "K9") (pinfunction "VDDSHV2_K9") (pintype "power_in"))
      (node (ref "U7") (pin "L8") (pinfunction "SYS_VDD3_3P3V_L8") (pintype "power_in"))
      (node (ref "U7") (pin "L9") (pinfunction "VDDSHV3_L9") (pintype "power_in"))
    )
    (net (code "188") (name "Net-(TP166-1)") (class "Default")
      (node (ref "TP166") (pin "P$1") (pinfunction "1_P$1") (pintype "bidirectional"))
      (node (ref "U7") (pin "G13") (pinfunction "VDDS_PLL_G13") (pintype "bidirectional"))
    )
    (net (code "189") (name "Net-(TP167-1)") (class "Default")
      (node (ref "TP167") (pin "P$1") (pinfunction "1_P$1") (pintype "bidirectional"))
      (node (ref "U7") (pin "D4") (pinfunction "EXTINTN_D4") (pintype "bidirectional"))
      (node (ref "U7") (pin "E4") (pinfunction "PMIC_NINT_E4") (pintype "output"))
    )
    (net (code "190") (name "Net-(TP168-1)") (class "Default")
      (node (ref "TP168") (pin "P$1") (pinfunction "1_P$1") (pintype "bidirectional"))
      (node (ref "U7") (pin "D6") (pinfunction "PMIC_MUX_OUT_D6") (pintype "bidirectional"))
    )
    (net (code "191") (name "Net-(TP169-1)") (class "Default")
      (node (ref "TP169") (pin "P$1") (pinfunction "1_P$1") (pintype "bidirectional"))
      (node (ref "U7") (pin "C8") (pinfunction "AIN5_C8") (pintype "bidirectional"))
    )
    (net (code "192") (name "Net-(TP170-1)") (class "Default")
      (node (ref "TP170") (pin "P$1") (pinfunction "1_P$1") (pintype "bidirectional"))
      (node (ref "U7") (pin "D7") (pinfunction "AIN7_D7") (pintype "bidirectional"))
    )
    (net (code "193") (name "Net-(TP171-1)") (class "Default")
      (node (ref "TP171") (pin "P$1") (pinfunction "1_P$1") (pintype "bidirectional"))
      (node (ref "U7") (pin "A9") (pinfunction "AGND_ADC_A9") (pintype "bidirectional"))
      (node (ref "U7") (pin "B7") (pinfunction "VREFP_B7") (pintype "bidirectional"))
      (node (ref "U7") (pin "B9") (pinfunction "VREFN_B9") (pintype "bidirectional"))
    )
    (net (code "194") (name "Net-(TP172-1)") (class "Default")
      (node (ref "TP172") (pin "P$1") (pinfunction "1_P$1") (pintype "bidirectional"))
      (node (ref "U7") (pin "D12") (pinfunction "NC_D12") (pintype "bidirectional"))
    )
    (net (code "195") (name "Net-(TP173-1)") (class "Default")
      (node (ref "TP173") (pin "P$1") (pinfunction "1_P$1") (pintype "bidirectional"))
      (node (ref "U7") (pin "D5") (pinfunction "CAP_VDD_RTC_D5") (pintype "bidirectional"))
    )
    (net (code "196") (name "Net-(TP174-1)") (class "Default")
      (node (ref "TP174") (pin "P$1") (pinfunction "1_P$1") (pintype "bidirectional"))
      (node (ref "U7") (pin "D13") (pinfunction "MDC_D13") (pintype "bidirectional"))
    )
    (net (code "197") (name "Net-(TP175-1)") (class "Default")
      (node (ref "TP175") (pin "P$1") (pinfunction "1_P$1") (pintype "bidirectional"))
      (node (ref "U7") (pin "C6") (pinfunction "AIN3_C6") (pintype "bidirectional"))
    )
    (net (code "198") (name "Net-(TP176-1)") (class "Default")
      (node (ref "TP176") (pin "P$1") (pinfunction "1_P$1") (pintype "bidirectional"))
      (node (ref "U7") (pin "C7") (pinfunction "AIN4_C7") (pintype "bidirectional"))
    )
    (net (code "199") (name "Net-(TP177-1)") (class "Default")
      (node (ref "TP177") (pin "P$1") (pinfunction "1_P$1") (pintype "bidirectional"))
      (node (ref "U7") (pin "C12") (pinfunction "UART0_CTSN_C12") (pintype "bidirectional"))
    )
    (net (code "200") (name "Net-(TP178-1)") (class "Default")
      (node (ref "TP178") (pin "P$1") (pinfunction "1_P$1") (pintype "bidirectional"))
      (node (ref "U7") (pin "C13") (pinfunction "UART0_RTSN_C13") (pintype "bidirectional"))
    )
    (net (code "201") (name "Net-(TP179-1)") (class "Default")
      (node (ref "TP179") (pin "P$1") (pinfunction "1_P$1") (pintype "bidirectional"))
      (node (ref "U7") (pin "C9") (pinfunction "AIN6_C9") (pintype "bidirectional"))
    )
    (net (code "202") (name "Net-(TP180-1)") (class "Default")
      (node (ref "TP180") (pin "P$1") (pinfunction "1_P$1") (pintype "bidirectional"))
      (node (ref "U7") (pin "C5") (pinfunction "ECAP0_IN_PWM0_OUT_C5") (pintype "bidirectional"))
    )
    (net (code "203") (name "Net-(TP181-1)") (class "Default")
      (node (ref "TP181") (pin "P$1") (pinfunction "1_P$1") (pintype "bidirectional"))
      (node (ref "U7") (pin "B6") (pinfunction "AIN2_B6") (pintype "bidirectional"))
    )
    (net (code "204") (name "Net-(TP182-1)") (class "Default")
      (node (ref "TP182") (pin "P$1") (pinfunction "1_P$1") (pintype "bidirectional"))
      (node (ref "U7") (pin "A7") (pinfunction "SYS_ADC_1P8V_A7") (pintype "bidirectional"))
    )
    (net (code "205") (name "Net-(U2-EN)") (class "Default")
      (node (ref "R6") (pin "2") (pinfunction "2_2") (pintype "passive"))
      (node (ref "U2") (pin "4") (pinfunction "EN_4") (pintype "input"))
      (node (ref "U7") (pin "M14") (pinfunction "USB1_DRVVBUS_M14") (pintype "bidirectional"))
    )
    (net (code "206") (name "Net-(U2-~{FLT})") (class "Default")
      (node (ref "R7") (pin "1") (pinfunction "1_1") (pintype "passive"))
      (node (ref "U2") (pin "3") (pinfunction "~{FLT}_3") (pintype "output"))
    )
    (net (code "207") (name "Net-(U3-VDDI)") (class "Default")
      (node (ref "C10") (pin "1") (pinfunction "1_1") (pintype "passive"))
      (node (ref "C12") (pin "1") (pinfunction "1_1") (pintype "passive"))
      (node (ref "U3") (pin "C2") (pinfunction "VDDI_C2") (pintype "power_in"))
    )
    (net (code "208") (name "Net-(U5-DIR)") (class "Default")
      (node (ref "R14") (pin "1") (pinfunction "1_1") (pintype "passive"))
      (node (ref "U5") (pin "2") (pinfunction "DIR_2") (pintype "input"))
    )
    (net (code "209") (name "Net-(U6-1DIR)") (class "Default")
      (node (ref "R16") (pin "1") (pinfunction "1_1") (pintype "passive"))
      (node (ref "U6") (pin "1") (pinfunction "1DIR_1") (pintype "input"))
      (node (ref "U6") (pin "24") (pinfunction "2DIR_24") (pintype "input"))
    )
    (net (code "210") (name "Net-(U7A-RTC_KALDO_ENN)") (class "Default")
      (node (ref "R15") (pin "2") (pinfunction "2_2") (pintype "passive"))
      (node (ref "U7") (pin "M16") (pinfunction "RTC_KALDO_ENN_M16") (pintype "bidirectional"))
    )
    (net (code "211") (name "Net-(U7B-EMU0)") (class "Default")
      (node (ref "R22") (pin "1") (pinfunction "1_1") (pintype "passive"))
      (node (ref "U7") (pin "E2") (pinfunction "EMU0_E2") (pintype "bidirectional"))
    )
    (net (code "212") (name "Net-(U7B-EMU1)") (class "Default")
      (node (ref "R20") (pin "1") (pinfunction "1_1") (pintype "passive"))
      (node (ref "U7") (pin "E3") (pinfunction "EMU1_E3") (pintype "bidirectional"))
    )
    (net (code "213") (name "Net-(U7B-OSC1_GND)") (class "Default")
      (node (ref "C29") (pin "2") (pinfunction "2_2") (pintype "passive"))
      (node (ref "C30") (pin "2") (pinfunction "2_2") (pintype "passive"))
      (node (ref "U7") (pin "B5") (pinfunction "OSC1_GND_B5") (pintype "bidirectional"))
    )
    (net (code "214") (name "Net-(U7B-OSC1_IN)") (class "Default")
      (node (ref "C30") (pin "1") (pinfunction "1_1") (pintype "passive"))
      (node (ref "R27") (pin "2") (pinfunction "2_2") (pintype "passive"))
      (node (ref "U7") (pin "A6") (pinfunction "OSC1_IN_A6") (pintype "bidirectional"))
      (node (ref "Y2") (pin "P$2") (pinfunction "P$2_P$2") (pintype "passive"))
    )
    (net (code "215") (name "Net-(U7B-OSC1_OUT)") (class "Default")
      (node (ref "C29") (pin "1") (pinfunction "1_1") (pintype "passive"))
      (node (ref "R27") (pin "1") (pinfunction "1_1") (pintype "passive"))
      (node (ref "U7") (pin "A5") (pinfunction "OSC1_OUT_A5") (pintype "bidirectional"))
      (node (ref "Y2") (pin "P$1") (pinfunction "P$1_P$1") (pintype "passive"))
    )
    (net (code "216") (name "Net-(U7B-USB1_ID)") (class "Default")
      (node (ref "JP100") (pin "1") (pinfunction "1_1") (pintype "passive"))
      (node (ref "U7") (pin "L14") (pinfunction "USB1_ID_L14") (pintype "bidirectional"))
    )
    (net (code "217") (name "Net-(U7C-GPMC_A5)") (class "Default")
      (node (ref "R2") (pin "1") (pinfunction "1_1") (pintype "passive"))
      (node (ref "U7") (pin "P13") (pinfunction "GPMC_A5_P13") (pintype "bidirectional"))
    )
    (net (code "218") (name "Net-(U7C-GPMC_A6)") (class "Default")
      (node (ref "R3") (pin "1") (pinfunction "1_1") (pintype "passive"))
      (node (ref "U7") (pin "T14") (pinfunction "GPMC_A6_T14") (pintype "bidirectional"))
    )
    (net (code "219") (name "Net-(U7C-GPMC_A7)") (class "Default")
      (node (ref "R4") (pin "1") (pinfunction "1_1") (pintype "passive"))
      (node (ref "U7") (pin "R14") (pinfunction "GPMC_A7_R14") (pintype "bidirectional"))
    )
    (net (code "220") (name "Net-(U7C-GPMC_A8)") (class "Default")
      (node (ref "R5") (pin "1") (pinfunction "1_1") (pintype "passive"))
      (node (ref "U7") (pin "P14") (pinfunction "GPMC_A8_P14") (pintype "bidirectional"))
    )
    (net (code "221") (name "Net-(U7C-MMC0_DAT0)") (class "Default")
      (node (ref "JP111") (pin "2") (pinfunction "2_2") (pintype "passive"))
      (node (ref "U7") (pin "A16") (pinfunction "MMC0_DAT0_A16") (pintype "bidirectional"))
    )
    (net (code "222") (name "Net-(U7C-MMC0_DAT1)") (class "Default")
      (node (ref "JP110") (pin "2") (pinfunction "2_2") (pintype "passive"))
      (node (ref "U7") (pin "A15") (pinfunction "MMC0_DAT1_A15") (pintype "bidirectional"))
    )
    (net (code "223") (name "Net-(U7C-MMC0_DAT2)") (class "Default")
      (node (ref "JP103") (pin "2") (pinfunction "2_2") (pintype "passive"))
      (node (ref "U7") (pin "C16") (pinfunction "MMC0_DAT2_C16") (pintype "bidirectional"))
    )
    (net (code "224") (name "Net-(U7C-MMC0_DAT3)") (class "Default")
      (node (ref "JP102") (pin "2") (pinfunction "2_2") (pintype "passive"))
      (node (ref "U7") (pin "C15") (pinfunction "MMC0_DAT3_C15") (pintype "bidirectional"))
    )
    (net (code "225") (name "Net-(U7D-LCD_DATA0)") (class "Default")
      (node (ref "JP105") (pin "2") (pinfunction "2_2") (pintype "passive"))
      (node (ref "U7") (pin "G3") (pinfunction "LCD_DATA0_G3") (pintype "bidirectional"))
    )
    (net (code "226") (name "Net-(U7D-LCD_DATA1)") (class "Default")
      (node (ref "JP106") (pin "2") (pinfunction "2_2") (pintype "passive"))
      (node (ref "U7") (pin "G2") (pinfunction "LCD_DATA1_G2") (pintype "bidirectional"))
    )
    (net (code "227") (name "Net-(U7D-LCD_DATA2)") (class "Default")
      (node (ref "J3") (pin "2") (pinfunction "2_2") (pintype "passive"))
      (node (ref "JP107") (pin "2") (pinfunction "2_2") (pintype "passive"))
      (node (ref "U7") (pin "G1") (pinfunction "LCD_DATA2_G1") (pintype "bidirectional"))
    )
    (net (code "228") (name "Net-(U7D-LCD_DATA3)") (class "Default")
      (node (ref "JP108") (pin "2") (pinfunction "2_2") (pintype "passive"))
      (node (ref "U7") (pin "H3") (pinfunction "LCD_DATA3_H3") (pintype "bidirectional"))
    )
    (net (code "229") (name "Net-(U7D-LCD_DATA4)") (class "Default")
      (node (ref "JP109") (pin "2") (pinfunction "2_2") (pintype "passive"))
      (node (ref "U7") (pin "H2") (pinfunction "LCD_DATA4_H2") (pintype "bidirectional"))
    )
    (net (code "230") (name "Net-(U9-EN)") (class "Default")
      (node (ref "R21") (pin "1") (pinfunction "1_1") (pintype "passive"))
      (node (ref "U9") (pin "5") (pinfunction "EN_5") (pintype "input"))
    )
    (net (code "231") (name "Net-(U10-ANODE)") (class "Default")
      (node (ref "JP104") (pin "2") (pinfunction "2_2") (pintype "passive"))
      (node (ref "Q1") (pin "C") (pinfunction "C_C") (pintype "passive"))
      (node (ref "R31") (pin "1") (pinfunction "1_1") (pintype "passive"))
      (node (ref "U10") (pin "3") (pinfunction "ANODE_3") (pintype "bidirectional"))
    )
    (net (code "232") (name "Net-(U10-CATHODE)") (class "Default")
      (node (ref "Q1") (pin "B") (pinfunction "B_B") (pintype "passive"))
      (node (ref "R23") (pin "1") (pinfunction "1_1") (pintype "passive"))
      (node (ref "U10") (pin "2") (pinfunction "CATHODE_2") (pintype "bidirectional"))
    )
    (net (code "233") (name "Net-(U10-REF)") (class "Default")
      (node (ref "R28") (pin "1") (pinfunction "1_1") (pintype "passive"))
      (node (ref "R31") (pin "2") (pinfunction "2_2") (pintype "passive"))
      (node (ref "U10") (pin "1") (pinfunction "REF_1") (pintype "bidirectional"))
    )
    (net (code "234") (name "Net-(U11-RXD)") (class "Default")
      (node (ref "U11") (pin "4") (pinfunction "RXD_4") (pintype "output"))
      (node (ref "U7") (pin "B11") (pinfunction "UART1_TXD_B11") (pintype "bidirectional"))
    )
    (net (code "235") (name "Net-(U11-TXD)") (class "Default")
      (node (ref "U11") (pin "1") (pinfunction "TXD_1") (pintype "input"))
      (node (ref "U7") (pin "A11") (pinfunction "UART1_RXD_A11") (pintype "bidirectional"))
    )
    (net (code "236") (name "Net-(U12-INP)") (class "Default")
      (node (ref "C32") (pin "1") (pinfunction "1_1") (pintype "passive"))
      (node (ref "R36") (pin "1") (pinfunction "1_1") (pintype "passive"))
      (node (ref "R37") (pin "1") (pinfunction "1_1") (pintype "passive"))
      (node (ref "U12") (pin "1") (pinfunction "INP_1") (pintype "input"))
    )
    (net (code "237") (name "Net-(U13-INP)") (class "Default")
      (node (ref "C35") (pin "1") (pinfunction "1_1") (pintype "passive"))
      (node (ref "R44") (pin "1") (pinfunction "1_1") (pintype "passive"))
      (node (ref "R45") (pin "1") (pinfunction "1_1") (pintype "passive"))
      (node (ref "U13") (pin "1") (pinfunction "INP_1") (pintype "input"))
    )
    (net (code "238") (name "Net-(U14-CIN1+)") (class "Default")
      (node (ref "R50") (pin "1") (pinfunction "1_1") (pintype "passive"))
      (node (ref "R51") (pin "2") (pinfunction "2_2") (pintype "passive"))
      (node (ref "TP57") (pin "1") (pinfunction "1_1") (pintype "passive"))
      (node (ref "U14") (pin "10") (pinfunction "CIN1+_10") (pintype "input"))
    )
    (net (code "239") (name "Net-(U14-CIN1-)") (class "Default")
      (node (ref "R42") (pin "2") (pinfunction "2_2") (pintype "passive"))
      (node (ref "R47") (pin "1") (pinfunction "1_1") (pintype "passive"))
      (node (ref "TP47") (pin "1") (pinfunction "1_1") (pintype "passive"))
      (node (ref "U14") (pin "11") (pinfunction "CIN1-_11") (pintype "input"))
    )
    (net (code "240") (name "Net-(U14-CIN2+)") (class "Default")
      (node (ref "R47") (pin "2") (pinfunction "2_2") (pintype "passive"))
      (node (ref "U14") (pin "12") (pinfunction "REF_12") (pintype "output"))
      (node (ref "U14") (pin "8") (pinfunction "CIN2+_8") (pintype "input"))
    )
    (net (code "241") (name "Net-(U14-INHIBIT)") (class "Default")
      (node (ref "R38") (pin "1") (pinfunction "1_1") (pintype "passive"))
      (node (ref "U14") (pin "5") (pinfunction "INHIBIT_5") (pintype "input"))
    )
    (net (code "242") (name "Net-(U14-IOUT)") (class "Default")
      (node (ref "R50") (pin "2") (pinfunction "2_2") (pintype "passive"))
      (node (ref "U14") (pin "14") (pinfunction "IOUT_14") (pintype "output"))
    )
    (net (code "243") (name "Net-(U14-RS+)") (class "Default")
      (node (ref "Q6") (pin "1") (pinfunction "D_1") (pintype "passive"))
      (node (ref "Q6") (pin "2") (pinfunction "D_2") (pintype "passive"))
      (node (ref "Q6") (pin "5") (pinfunction "D_5") (pintype "passive"))
      (node (ref "Q6") (pin "6") (pinfunction "D_6") (pintype "passive"))
      (node (ref "R63") (pin "1") (pinfunction "1_1") (pintype "passive"))
      (node (ref "U14") (pin "16") (pinfunction "RS+_16") (pintype "passive"))
    )
    (net (code "244") (name "Net-(U15-PG)") (class "Default")
      (node (ref "TP48") (pin "1") (pinfunction "1_1") (pintype "passive"))
      (node (ref "U15") (pin "13") (pinfunction "PG_13") (pintype "open_collector"))
    )
    (net (code "245") (name "Net-(U15-SYNC)") (class "Default")
      (node (ref "R34") (pin "1") (pinfunction "1_1") (pintype "passive"))
      (node (ref "R40") (pin "2") (pinfunction "2_2") (pintype "passive"))
      (node (ref "TP46") (pin "1") (pinfunction "1_1") (pintype "passive"))
      (node (ref "U15") (pin "5") (pinfunction "SYNC_5") (pintype "input"))
    )
    (net (code "246") (name "Net-(U16-IO6)") (class "Default")
      (node (ref "R59") (pin "1") (pinfunction "1_1") (pintype "passive"))
      (node (ref "R60") (pin "1") (pinfunction "1_1") (pintype "passive"))
      (node (ref "TP53") (pin "1") (pinfunction "1_1") (pintype "passive"))
      (node (ref "U16") (pin "11") (pinfunction "IO6_11") (pintype "bidirectional"))
    )
    (net (code "247") (name "Net-(U16-~{RESET})") (class "Default")
      (node (ref "R72") (pin "1") (pinfunction "1_1") (pintype "passive"))
      (node (ref "U16") (pin "13") (pinfunction "~{RESET}_13") (pintype "input"))
    )
    (net (code "248") (name "ON{slash}~{OFF}") (class "Default")
      (node (ref "Q4") (pin "1") (pinfunction "G_1") (pintype "passive"))
      (node (ref "R46") (pin "2") (pinfunction "2_2") (pintype "passive"))
      (node (ref "R49") (pin "2") (pinfunction "2_2") (pintype "passive"))
      (node (ref "TP50") (pin "1") (pinfunction "1_1") (pintype "passive"))
      (node (ref "U16") (pin "8") (pinfunction "IO3_8") (pintype "bidirectional"))
    )
    (net (code "249") (name "OPD_PWR") (class "Default")
      (node (ref "J4") (pin "15") (pinfunction "15_15") (pintype "passive"))
      (node (ref "J4") (pin "16") (pinfunction "16_16") (pintype "passive"))
      (node (ref "R71") (pin "1") (pinfunction "1_1") (pintype "passive"))
    )
    (net (code "250") (name "OPD_SCL") (class "Default")
      (node (ref "J4") (pin "13") (pinfunction "13_13") (pintype "passive"))
      (node (ref "J4") (pin "14") (pinfunction "14_14") (pintype "passive"))
      (node (ref "R48") (pin "1") (pinfunction "1_1") (pintype "passive"))
    )
    (net (code "251") (name "OPD_SDA") (class "Default")
      (node (ref "J4") (pin "11") (pinfunction "11_11") (pintype "passive"))
      (node (ref "J4") (pin "12") (pinfunction "12_12") (pintype "passive"))
      (node (ref "R41") (pin "1") (pinfunction "1_1") (pintype "passive"))
    )
    (net (code "252") (name "OSC0_GND") (class "Default")
      (node (ref "C19") (pin "1") (pinfunction "1_1") (pintype "passive"))
      (node (ref "C22") (pin "1") (pinfunction "1_1") (pintype "passive"))
      (node (ref "U7") (pin "N15") (pinfunction "OSC0_GND_N15") (pintype "bidirectional"))
    )
    (net (code "253") (name "OSC0_IN") (class "Default")
      (node (ref "C19") (pin "2") (pinfunction "2_2") (pintype "passive"))
      (node (ref "R13") (pin "2") (pinfunction "2_2") (pintype "passive"))
      (node (ref "U7") (pin "P16") (pinfunction "OSC0_IN_P16") (pintype "bidirectional"))
      (node (ref "Y1") (pin "1") (pinfunction "X1_1") (pintype "passive"))
    )
    (net (code "254") (name "OSC0_OUT") (class "Default")
      (node (ref "C22") (pin "2") (pinfunction "2_2") (pintype "passive"))
      (node (ref "R13") (pin "1") (pinfunction "1_1") (pintype "passive"))
      (node (ref "U7") (pin "N16") (pinfunction "OSC0_OUT_N16") (pintype "bidirectional"))
      (node (ref "Y1") (pin "3") (pinfunction "X2_3") (pintype "passive"))
    )
    (net (code "255") (name "PB6{slash}SCL") (class "Default")
      (node (ref "R60") (pin "2") (pinfunction "2_2") (pintype "passive"))
      (node (ref "U16") (pin "4") (pinfunction "IO0_4") (pintype "bidirectional"))
    )
    (net (code "256") (name "PB7{slash}SDA") (class "Default")
      (node (ref "R59") (pin "2") (pinfunction "2_2") (pintype "passive"))
      (node (ref "U16") (pin "5") (pinfunction "IO1_5") (pintype "bidirectional"))
    )
    (net (code "257") (name "PEN-SCL-FILT") (class "Default")
      (node (ref "Q3") (pin "6") (pinfunction "D_6") (pintype "passive"))
      (node (ref "R37") (pin "2") (pinfunction "2_2") (pintype "passive"))
      (node (ref "R65") (pin "1") (pinfunction "1_1") (pintype "passive"))
      (node (ref "R67") (pin "1") (pinfunction "1_1") (pintype "passive"))
      (node (ref "R69") (pin "1") (pinfunction "1_1") (pintype "passive"))
      (node (ref "TP42") (pin "1") (pinfunction "1_1") (pintype "passive"))
      (node (ref "TP66") (pin "1") (pinfunction "1_1") (pintype "passive"))
      (node (ref "U16") (pin "15") (pinfunction "SCL_15") (pintype "input"))
    )
    (net (code "258") (name "PEN-SDA-FILT") (class "Default")
      (node (ref "Q3") (pin "4") (pinfunction "D_4") (pintype "passive"))
      (node (ref "R45") (pin "2") (pinfunction "2_2") (pintype "passive"))
      (node (ref "R66") (pin "2") (pinfunction "2_2") (pintype "passive"))
      (node (ref "R68") (pin "2") (pinfunction "2_2") (pintype "passive"))
      (node (ref "R70") (pin "2") (pinfunction "2_2") (pintype "passive"))
      (node (ref "TP41") (pin "1") (pinfunction "1_1") (pintype "passive"))
      (node (ref "TP65") (pin "1") (pinfunction "1_1") (pintype "passive"))
      (node (ref "U16") (pin "16") (pinfunction "SDA_16") (pintype "bidirectional"))
    )
    (net (code "259") (name "PIXCLK_E") (class "Default")
      (node (ref "J101") (pin "5") (pinfunction "5_5") (pintype "passive"))
      (node (ref "U6") (pin "20") (pinfunction "2B6_20") (pintype "bidirectional"))
    )
    (net (code "260") (name "PIXCLK_I") (class "Default")
      (node (ref "TP28") (pin "P$1") (pinfunction "1_P$1") (pintype "bidirectional"))
      (node (ref "U6") (pin "29") (pinfunction "2A6_29") (pintype "bidirectional"))
      (node (ref "U7") (pin "B4") (pinfunction "XDMA_EVENT_INTR1_B4") (pintype "bidirectional"))
    )
    (net (code "261") (name "PMIC_PGOOD") (class "Default")
      (node (ref "TP110") (pin "P$1") (pinfunction "1_P$1") (pintype "bidirectional"))
      (node (ref "U4") (pin "2") (pinfunction "A_2") (pintype "bidirectional"))
      (node (ref "U7") (pin "N12") (pinfunction "PMIC_PGOOD_N12") (pintype "output"))
      (node (ref "U7") (pin "P11") (pinfunction "PWRONRSTN_P11") (pintype "bidirectional"))
    )
    (net (code "262") (name "POUT") (class "Default")
      (node (ref "TP64") (pin "1") (pinfunction "1_1") (pintype "passive"))
      (node (ref "U14") (pin "13") (pinfunction "POUT_13") (pintype "output"))
    )
    (net (code "263") (name "RESET") (class "Default")
      (node (ref "TP10") (pin "P$1") (pinfunction "1_P$1") (pintype "bidirectional"))
      (node (ref "U5") (pin "19") (pinfunction "B3_19") (pintype "bidirectional"))
      (node (ref "U7") (pin "D16") (pinfunction "MII1_RXD1_D16") (pintype "bidirectional"))
    )
    (net (code "264") (name "RESET#") (class "Default")
      (node (ref "TP109") (pin "P$1") (pinfunction "1_P$1") (pintype "bidirectional"))
      (node (ref "U4") (pin "4") (pinfunction "Y_4") (pintype "bidirectional"))
      (node (ref "U7") (pin "R11") (pinfunction "WARMRSTN_R11") (pintype "bidirectional"))
    )
    (net (code "265") (name "SADDR") (class "Default")
      (node (ref "TP7") (pin "P$1") (pinfunction "1_P$1") (pintype "bidirectional"))
      (node (ref "U5") (pin "16") (pinfunction "B6_16") (pintype "bidirectional"))
      (node (ref "U7") (pin "D15") (pinfunction "MII1_RXD2_D15") (pintype "bidirectional"))
    )
    (net (code "266") (name "SADDR_E") (class "Default")
      (node (ref "J101") (pin "27") (pinfunction "27_27") (pintype "passive"))
      (node (ref "U5") (pin "8") (pinfunction "A6_8") (pintype "bidirectional"))
    )
    (net (code "267") (name "SCL_2") (class "Default")
      (node (ref "R30") (pin "2") (pinfunction "2_2") (pintype "passive"))
      (node (ref "TP37") (pin "P$1") (pinfunction "1_P$1") (pintype "bidirectional"))
      (node (ref "U7") (pin "A10") (pinfunction "UART1_RTSN_A10") (pintype "bidirectional"))
      (node (ref "U9") (pin "2") (pinfunction "SCLA_2") (pintype "bidirectional"))
    )
    (net (code "268") (name "SDA_2") (class "Default")
      (node (ref "R29") (pin "2") (pinfunction "2_2") (pintype "passive"))
      (node (ref "TP36") (pin "P$1") (pinfunction "1_P$1") (pintype "bidirectional"))
      (node (ref "U7") (pin "B10") (pinfunction "UART1_CTSN_B10") (pintype "bidirectional"))
      (node (ref "U9") (pin "3") (pinfunction "SDAA_3") (pintype "bidirectional"))
    )
    (net (code "269") (name "SPARE1") (class "Default")
      (node (ref "J4") (pin "10") (pinfunction "10_10") (pintype "passive"))
      (node (ref "J4") (pin "9") (pinfunction "9_9") (pintype "passive"))
      (node (ref "TP58") (pin "P$1") (pinfunction "1_P$1") (pintype "bidirectional"))
    )
    (net (code "270") (name "SPARE2") (class "Default")
      (node (ref "J4") (pin "7") (pinfunction "7_7") (pintype "passive"))
      (node (ref "J4") (pin "8") (pinfunction "8_8") (pintype "passive"))
      (node (ref "TP59") (pin "P$1") (pinfunction "1_P$1") (pintype "bidirectional"))
    )
    (net (code "271") (name "SPARE3") (class "Default")
      (node (ref "J4") (pin "5") (pinfunction "5_5") (pintype "passive"))
      (node (ref "J4") (pin "6") (pinfunction "6_6") (pintype "passive"))
      (node (ref "TP60") (pin "P$1") (pinfunction "1_P$1") (pintype "bidirectional"))
    )
    (net (code "272") (name "SPARE4") (class "Default")
      (node (ref "J4") (pin "3") (pinfunction "3_3") (pintype "passive"))
      (node (ref "J4") (pin "4") (pinfunction "4_4") (pintype "passive"))
      (node (ref "TP61") (pin "P$1") (pinfunction "1_P$1") (pintype "bidirectional"))
    )
    (net (code "273") (name "STANDBY") (class "Default")
      (node (ref "TP9") (pin "P$1") (pinfunction "1_P$1") (pintype "bidirectional"))
      (node (ref "U5") (pin "18") (pinfunction "B4_18") (pintype "bidirectional"))
      (node (ref "U7") (pin "D14") (pinfunction "MII1_RXD3_D14") (pintype "bidirectional"))
    )
    (net (code "274") (name "STANDBY_E") (class "Default")
      (node (ref "J101") (pin "25") (pinfunction "25_25") (pintype "passive"))
      (node (ref "U5") (pin "6") (pinfunction "A4_6") (pintype "bidirectional"))
    )
    (net (code "275") (name "TRIGGER") (class "Default")
      (node (ref "TP6") (pin "P$1") (pinfunction "1_P$1") (pintype "bidirectional"))
      (node (ref "U5") (pin "15") (pinfunction "B7_15") (pintype "bidirectional"))
      (node (ref "U7") (pin "E15") (pinfunction "MII1_RX_ER_E15") (pintype "bidirectional"))
    )
    (net (code "276") (name "TRIGGER_E") (class "Default")
      (node (ref "J101") (pin "29") (pinfunction "29_29") (pintype "passive"))
      (node (ref "U5") (pin "9") (pinfunction "A7_9") (pintype "bidirectional"))
    )
    (net (code "277") (name "UART0_RX") (class "Default")
      (node (ref "J1") (pin "12") (pinfunction "CARD-RX_12") (pintype "passive"))
      (node (ref "TP146") (pin "P$1") (pinfunction "1_P$1") (pintype "bidirectional"))
      (node (ref "U7") (pin "A12") (pinfunction "UART0_RXD_A12") (pintype "bidirectional"))
    )
    (net (code "278") (name "UART0_TX") (class "Default")
      (node (ref "J1") (pin "13") (pinfunction "CARD-TX_13") (pintype "passive"))
      (node (ref "TP142") (pin "P$1") (pinfunction "1_P$1") (pintype "bidirectional"))
      (node (ref "U7") (pin "B12") (pinfunction "UART0_TXD_B12") (pintype "bidirectional"))
    )
    (net (code "279") (name "USB_CLI_N") (class "Default")
      (node (ref "J1") (pin "5") (pinfunction "DEVICE-D-_5") (pintype "passive"))
      (node (ref "U1") (pin "1") (pinfunction "I1_1") (pintype "bidirectional"))
      (node (ref "U7") (pin "K16") (pinfunction "USB0_DM_K16") (pintype "bidirectional"))
    )
    (net (code "280") (name "USB_CLI_P") (class "Default")
      (node (ref "J1") (pin "4") (pinfunction "DEVICE-D+_4") (pintype "passive"))
      (node (ref "U1") (pin "3") (pinfunction "I2_3") (pintype "bidirectional"))
      (node (ref "U7") (pin "K15") (pinfunction "USB0_DP_K15") (pintype "bidirectional"))
    )
    (net (code "281") (name "USB_CLI_VBUS") (class "Default")
      (node (ref "FB2") (pin "1") (pinfunction "1_1") (pintype "passive"))
      (node (ref "J1") (pin "1") (pinfunction "VBUSP_1") (pintype "passive"))
      (node (ref "J1") (pin "2") (pinfunction "VBUSP_2") (pintype "passive"))
    )
    (net (code "282") (name "USB_HO_N") (class "Default")
      (node (ref "J1") (pin "8") (pinfunction "HOST-D-_8") (pintype "passive"))
      (node (ref "U1") (pin "6") (pinfunction "I4_6") (pintype "bidirectional"))
      (node (ref "U7") (pin "L16") (pinfunction "USB1_DM_L16") (pintype "bidirectional"))
    )
    (net (code "283") (name "USB_HO_PX") (class "Default")
      (node (ref "J1") (pin "7") (pinfunction "HOST-D+_7") (pintype "passive"))
      (node (ref "U1") (pin "4") (pinfunction "I3_4") (pintype "bidirectional"))
      (node (ref "U7") (pin "L15") (pinfunction "USB1_DP_L15") (pintype "bidirectional"))
    )
    (net (code "284") (name "USB_HO_VBUS") (class "Default")
      (node (ref "FB1") (pin "2") (pinfunction "2_2") (pintype "passive"))
      (node (ref "J1") (pin "17") (pinfunction "DEBUG-0_17") (pintype "passive"))
    )
    (net (code "285") (name "VBUS") (class "Default")
      (node (ref "J4") (pin "21") (pinfunction "21_21") (pintype "passive"))
      (node (ref "J4") (pin "22") (pinfunction "22_22") (pintype "passive"))
      (node (ref "J4") (pin "23") (pinfunction "23_23") (pintype "passive"))
      (node (ref "J4") (pin "24") (pinfunction "24_24") (pintype "passive"))
      (node (ref "J4") (pin "25") (pinfunction "25_25") (pintype "passive"))
      (node (ref "J4") (pin "26") (pinfunction "26_26") (pintype "passive"))
      (node (ref "Q6") (pin "4") (pinfunction "S_4") (pintype "passive"))
      (node (ref "R52") (pin "2") (pinfunction "2_2") (pintype "passive"))
    )
    (net (code "286") (name "VBUSP") (class "Default")
      (node (ref "C33") (pin "2") (pinfunction "2_2") (pintype "passive"))
      (node (ref "C37") (pin "1") (pinfunction "1_1") (pintype "passive"))
      (node (ref "C38") (pin "1") (pinfunction "1_1") (pintype "passive"))
      (node (ref "Q5") (pin "1") (pinfunction "D_1") (pintype "passive"))
      (node (ref "Q5") (pin "2") (pinfunction "D_2") (pintype "passive"))
      (node (ref "Q5") (pin "5") (pinfunction "D_5") (pintype "passive"))
      (node (ref "Q5") (pin "6") (pinfunction "D_6") (pintype "passive"))
      (node (ref "R34") (pin "2") (pinfunction "2_2") (pintype "passive"))
      (node (ref "R61") (pin "2") (pinfunction "2_2") (pintype "passive"))
      (node (ref "TP55") (pin "1") (pinfunction "1_1") (pintype "passive"))
      (node (ref "U15") (pin "2") (pinfunction "VIN_2") (pintype "power_in"))
      (node (ref "U15") (pin "3") (pinfunction "VIN_3") (pintype "power_in"))
      (node (ref "U15") (pin "4") (pinfunction "EN_4") (pintype "input"))
      (node (ref "U15") (pin "8") (pinfunction "VIN_8") (pintype "power_in"))
    )
    (net (code "287") (name "VDD") (class "Default")
      (node (ref "C15") (pin "1") (pinfunction "1_1") (pintype "passive"))
      (node (ref "C7") (pin "1") (pinfunction "1_1") (pintype "passive"))
      (node (ref "R7") (pin "2") (pinfunction "2_2") (pintype "passive"))
      (node (ref "TP3") (pin "P$1") (pinfunction "1_P$1") (pintype "bidirectional"))
      (node (ref "U2") (pin "5") (pinfunction "IN_5") (pintype "input"))
      (node (ref "U7") (pin "K6") (pinfunction "SYS_VOUT_K6") (pintype "power_in"))
      (node (ref "U7") (pin "K7") (pinfunction "SYS_VOUT_K7") (pintype "power_in"))
      (node (ref "U7") (pin "L6") (pinfunction "SYS_VOUT_L6") (pintype "power_in"))
      (node (ref "U7") (pin "L7") (pinfunction "SYS_VOUT_L7") (pintype "power_in"))
    )
    (net (code "288") (name "VIN_USB") (class "Default")
      (node (ref "C13") (pin "1") (pinfunction "1_1") (pintype "passive"))
      (node (ref "C4") (pin "1") (pinfunction "1_1") (pintype "passive"))
      (node (ref "FB2") (pin "2") (pinfunction "2_2") (pintype "passive"))
      (node (ref "TP2") (pin "P$1") (pinfunction "1_P$1") (pintype "bidirectional"))
      (node (ref "U1") (pin "5") (pinfunction "VCC_5") (pintype "power_in"))
      (node (ref "U7") (pin "J16") (pinfunction "USB0_VBUS_J16") (pintype "bidirectional"))
      (node (ref "U7") (pin "P9") (pinfunction "VIN_USB_P9") (pintype "power_in"))
      (node (ref "U7") (pin "R9") (pinfunction "VIN_USB_R9") (pintype "power_in"))
      (node (ref "U7") (pin "T9") (pinfunction "VIN_USB_T9") (pintype "power_in"))
    )
    (net (code "289") (name "VOUT_USB") (class "Default")
      (node (ref "C1") (pin "1") (pinfunction "1_1") (pintype "passive"))
      (node (ref "FB1") (pin "1") (pinfunction "1_1") (pintype "passive"))
      (node (ref "TP1") (pin "P$1") (pinfunction "1_P$1") (pintype "bidirectional"))
      (node (ref "U2") (pin "1") (pinfunction "OUT_1") (pintype "output"))
      (node (ref "U7") (pin "M15") (pinfunction "USB1_VBUS_M15") (pintype "bidirectional"))
    )
    (net (code "290") (name "VPD") (class "Default")
      (node (ref "C39") (pin "2") (pinfunction "2_2") (pintype "passive"))
      (node (ref "R32") (pin "2") (pinfunction "2_2") (pintype "passive"))
      (node (ref "R36") (pin "2") (pinfunction "2_2") (pintype "passive"))
      (node (ref "R44") (pin "2") (pinfunction "2_2") (pintype "passive"))
      (node (ref "R53") (pin "2") (pinfunction "2_2") (pintype "passive"))
      (node (ref "R55") (pin "2") (pinfunction "2_2") (pintype "passive"))
      (node (ref "R57") (pin "2") (pinfunction "2_2") (pintype "passive"))
      (node (ref "R71") (pin "2") (pinfunction "2_2") (pintype "passive"))
      (node (ref "R72") (pin "2") (pinfunction "2_2") (pintype "passive"))
      (node (ref "TP63") (pin "1") (pinfunction "1_1") (pintype "passive"))
      (node (ref "U12") (pin "5") (pinfunction "VDD_5") (pintype "power_in"))
      (node (ref "U13") (pin "5") (pinfunction "VDD_5") (pintype "power_in"))
      (node (ref "U16") (pin "14") (pinfunction "V+_14") (pintype "power_in"))
    )
    (net (code "291") (name "VREG_EN") (class "Default")
      (node (ref "TP5") (pin "P$1") (pinfunction "1_P$1") (pintype "bidirectional"))
      (node (ref "U5") (pin "14") (pinfunction "B8_14") (pintype "bidirectional"))
      (node (ref "U7") (pin "F16") (pinfunction "MII1_RX_DV_F16") (pintype "bidirectional"))
    )
    (net (code "292") (name "VREG_EN_E") (class "Default")
      (node (ref "J101") (pin "30") (pinfunction "30_30") (pintype "passive"))
      (node (ref "U5") (pin "10") (pinfunction "A8_10") (pintype "bidirectional"))
    )
    (net (code "293") (name "VSYNC_E") (class "Default")
      (node (ref "J101") (pin "3") (pinfunction "3_3") (pintype "passive"))
      (node (ref "U6") (pin "23") (pinfunction "2B8_23") (pintype "bidirectional"))
    )
    (net (code "294") (name "VSYNC_I") (class "Default")
      (node (ref "TP116") (pin "P$1") (pinfunction "1_P$1") (pintype "bidirectional"))
      (node (ref "U6") (pin "26") (pinfunction "2A8_26") (pintype "bidirectional"))
      (node (ref "U7") (pin "T6") (pinfunction "GPMC_AD14_T6") (pintype "bidirectional"))
    )
    (net (code "295") (name "unconnected-(J1-NRST-Pad10)") (class "Default")
      (node (ref "J1") (pin "10") (pinfunction "NRST_10") (pintype "passive"))
    )
    (net (code "296") (name "unconnected-(J1-SWCLK-Pad15)") (class "Default")
      (node (ref "J1") (pin "15") (pinfunction "SWCLK_15") (pintype "passive"))
    )
    (net (code "297") (name "unconnected-(J1-SWDIO-Pad14)") (class "Default")
      (node (ref "J1") (pin "14") (pinfunction "SWDIO_14") (pintype "passive"))
    )
    (net (code "298") (name "unconnected-(J1-SWO-Pad16)") (class "Default")
      (node (ref "J1") (pin "16") (pinfunction "SWO_16") (pintype "passive"))
    )
    (net (code "299") (name "unconnected-(J1-VTARGET-Pad11)") (class "Default")
      (node (ref "J1") (pin "11") (pinfunction "VTARGET_11") (pintype "passive"))
    )
    (net (code "300") (name "unconnected-(R8-11-Pad1)") (class "Default")
      (node (ref "R8") (pin "1") (pinfunction "11_1") (pintype "passive"))
    )
    (net (code "301") (name "unconnected-(R9-11-Pad1)") (class "Default")
      (node (ref "R9") (pin "1") (pinfunction "11_1") (pintype "passive"))
    )
    (net (code "302") (name "unconnected-(R9-99-Pad9)") (class "Default")
      (node (ref "R9") (pin "9") (pinfunction "99_9") (pintype "passive"))
    )
    (net (code "303") (name "unconnected-(R10-44-Pad4)") (class "Default")
      (node (ref "R10") (pin "4") (pinfunction "44_4") (pintype "passive"))
    )
    (net (code "304") (name "unconnected-(R10-66-Pad6)") (class "Default")
      (node (ref "R10") (pin "6") (pinfunction "66_6") (pintype "passive"))
    )
    (net (code "305") (name "unconnected-(R10-77-Pad7)") (class "Default")
      (node (ref "R10") (pin "7") (pinfunction "77_7") (pintype "passive"))
    )
    (net (code "306") (name "unconnected-(R24-11-Pad1)") (class "Default")
      (node (ref "R24") (pin "1") (pinfunction "11_1") (pintype "passive"))
    )
    (net (code "307") (name "unconnected-(R24-77-Pad7)") (class "Default")
      (node (ref "R24") (pin "7") (pinfunction "77_7") (pintype "passive"))
    )
    (net (code "308") (name "unconnected-(R25-88-Pad8)") (class "Default")
      (node (ref "R25") (pin "8") (pinfunction "88_8") (pintype "passive"))
    )
    (net (code "309") (name "unconnected-(U5-A1-Pad3)") (class "Default")
      (node (ref "U5") (pin "3") (pinfunction "A1_3") (pintype "bidirectional"))
    )
    (net (code "310") (name "unconnected-(U5-B1-Pad21)") (class "Default")
      (node (ref "U5") (pin "21") (pinfunction "B1_21") (pintype "bidirectional"))
    )
    (net (code "311") (name "~{FAULT}") (class "Default")
      (node (ref "Q2") (pin "3") (pinfunction "D_3") (pintype "passive"))
      (node (ref "R32") (pin "1") (pinfunction "1_1") (pintype "passive"))
      (node (ref "TP45") (pin "1") (pinfunction "1_1") (pintype "passive"))
      (node (ref "U16") (pin "7") (pinfunction "IO2_7") (pintype "bidirectional"))
    )
    (net (code "312") (name "~{OE_E}") (class "Default")
      (node (ref "J101") (pin "26") (pinfunction "26_26") (pintype "passive"))
      (node (ref "U5") (pin "7") (pinfunction "A5_7") (pintype "bidirectional"))
    )
    (net (code "313") (name "~{RESET_E}") (class "Default")
      (node (ref "J101") (pin "24") (pinfunction "24_24") (pintype "passive"))
      (node (ref "U5") (pin "5") (pinfunction "A3_5") (pintype "bidirectional"))
    )
    (net (code "314") (name "~{SD}") (class "Default")
      (node (ref "J4") (pin "39") (pinfunction "39_39") (pintype "passive"))
      (node (ref "J4") (pin "40") (pinfunction "40_40") (pintype "passive"))
    )
  )
)
